# PixHawk_Fire_v1_5.net
KiCad netlist of a schematic drawn in EAGLE
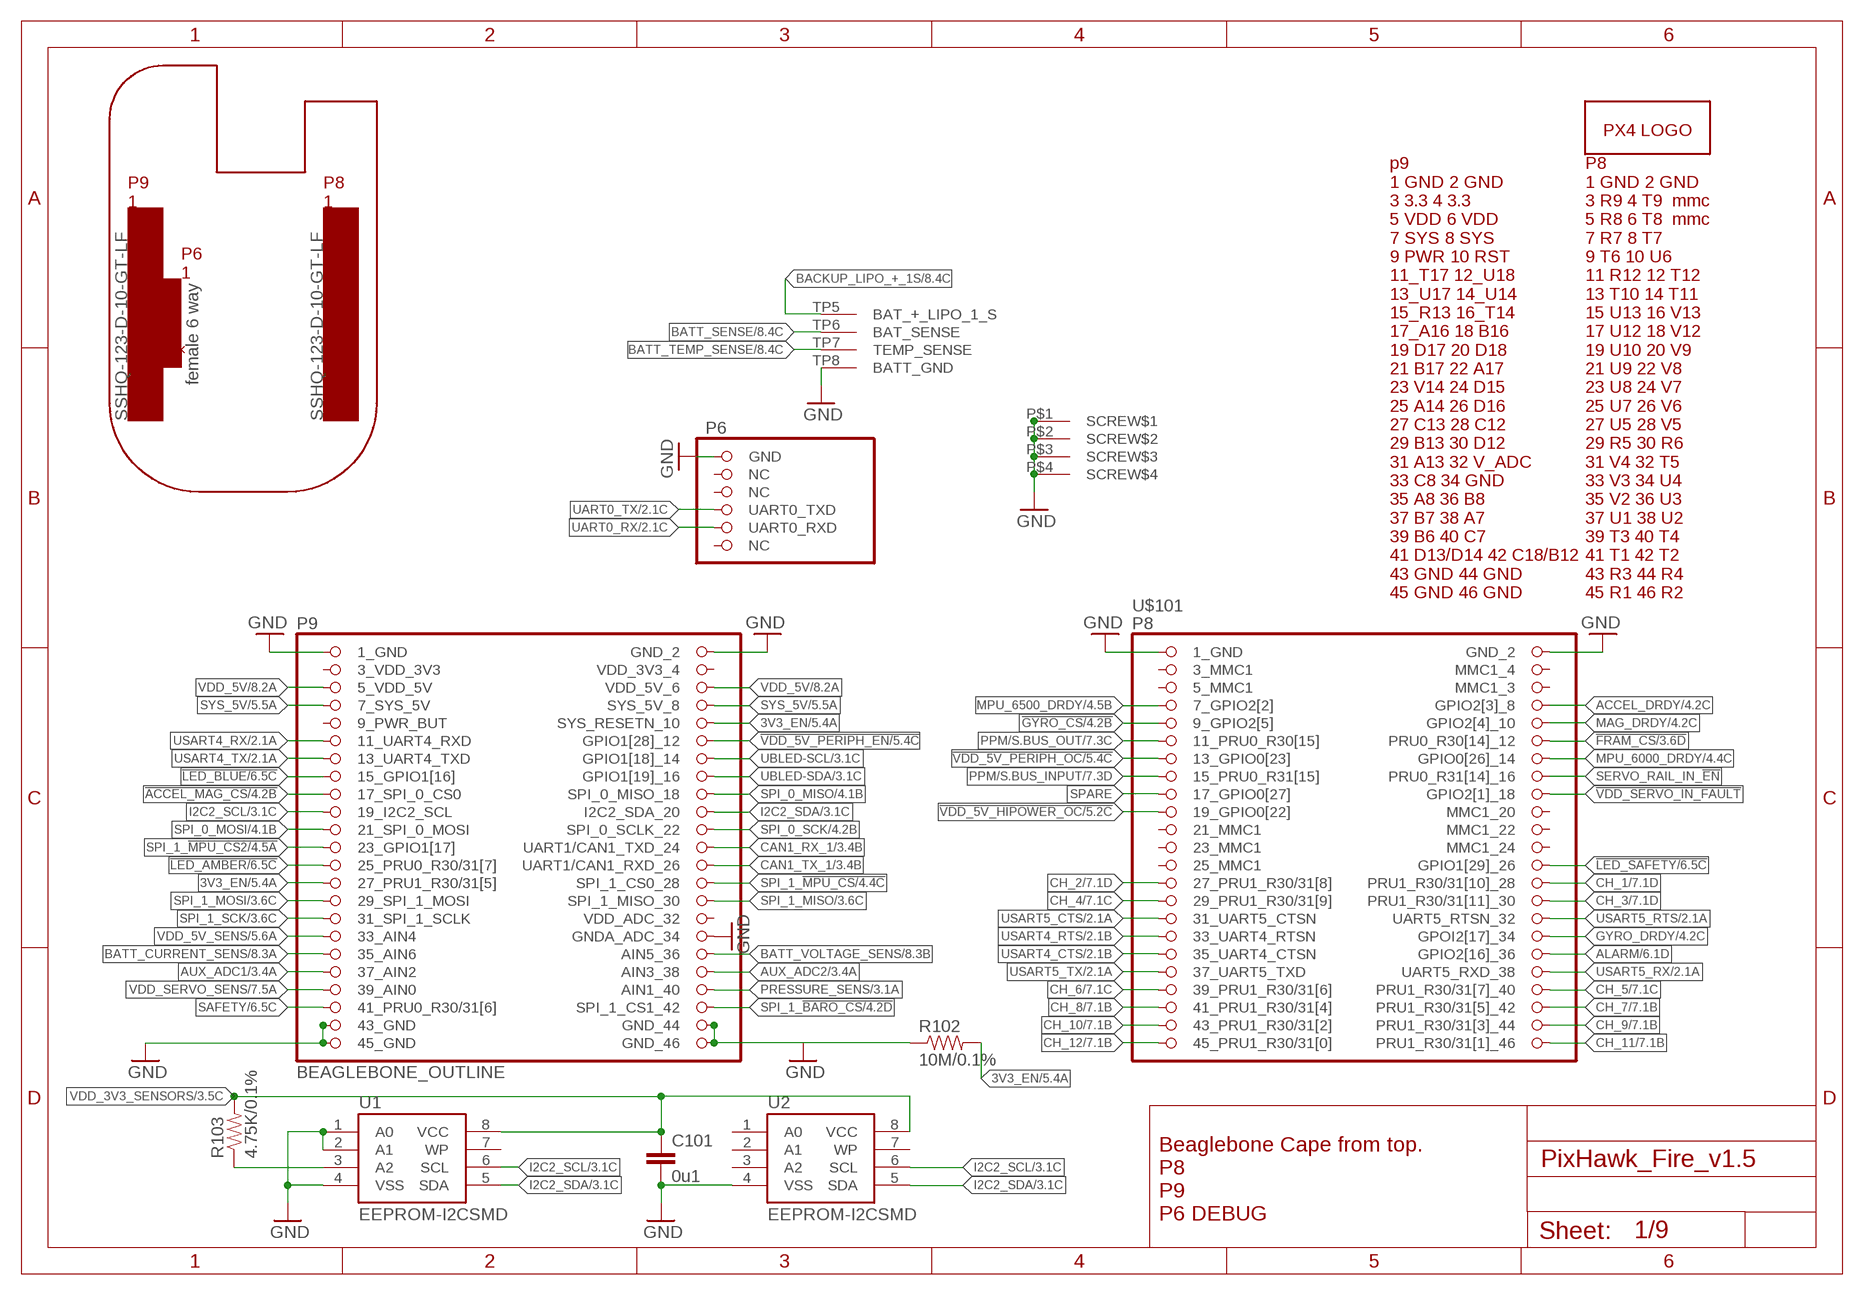
[diagram p0: schematic, sheet 1]
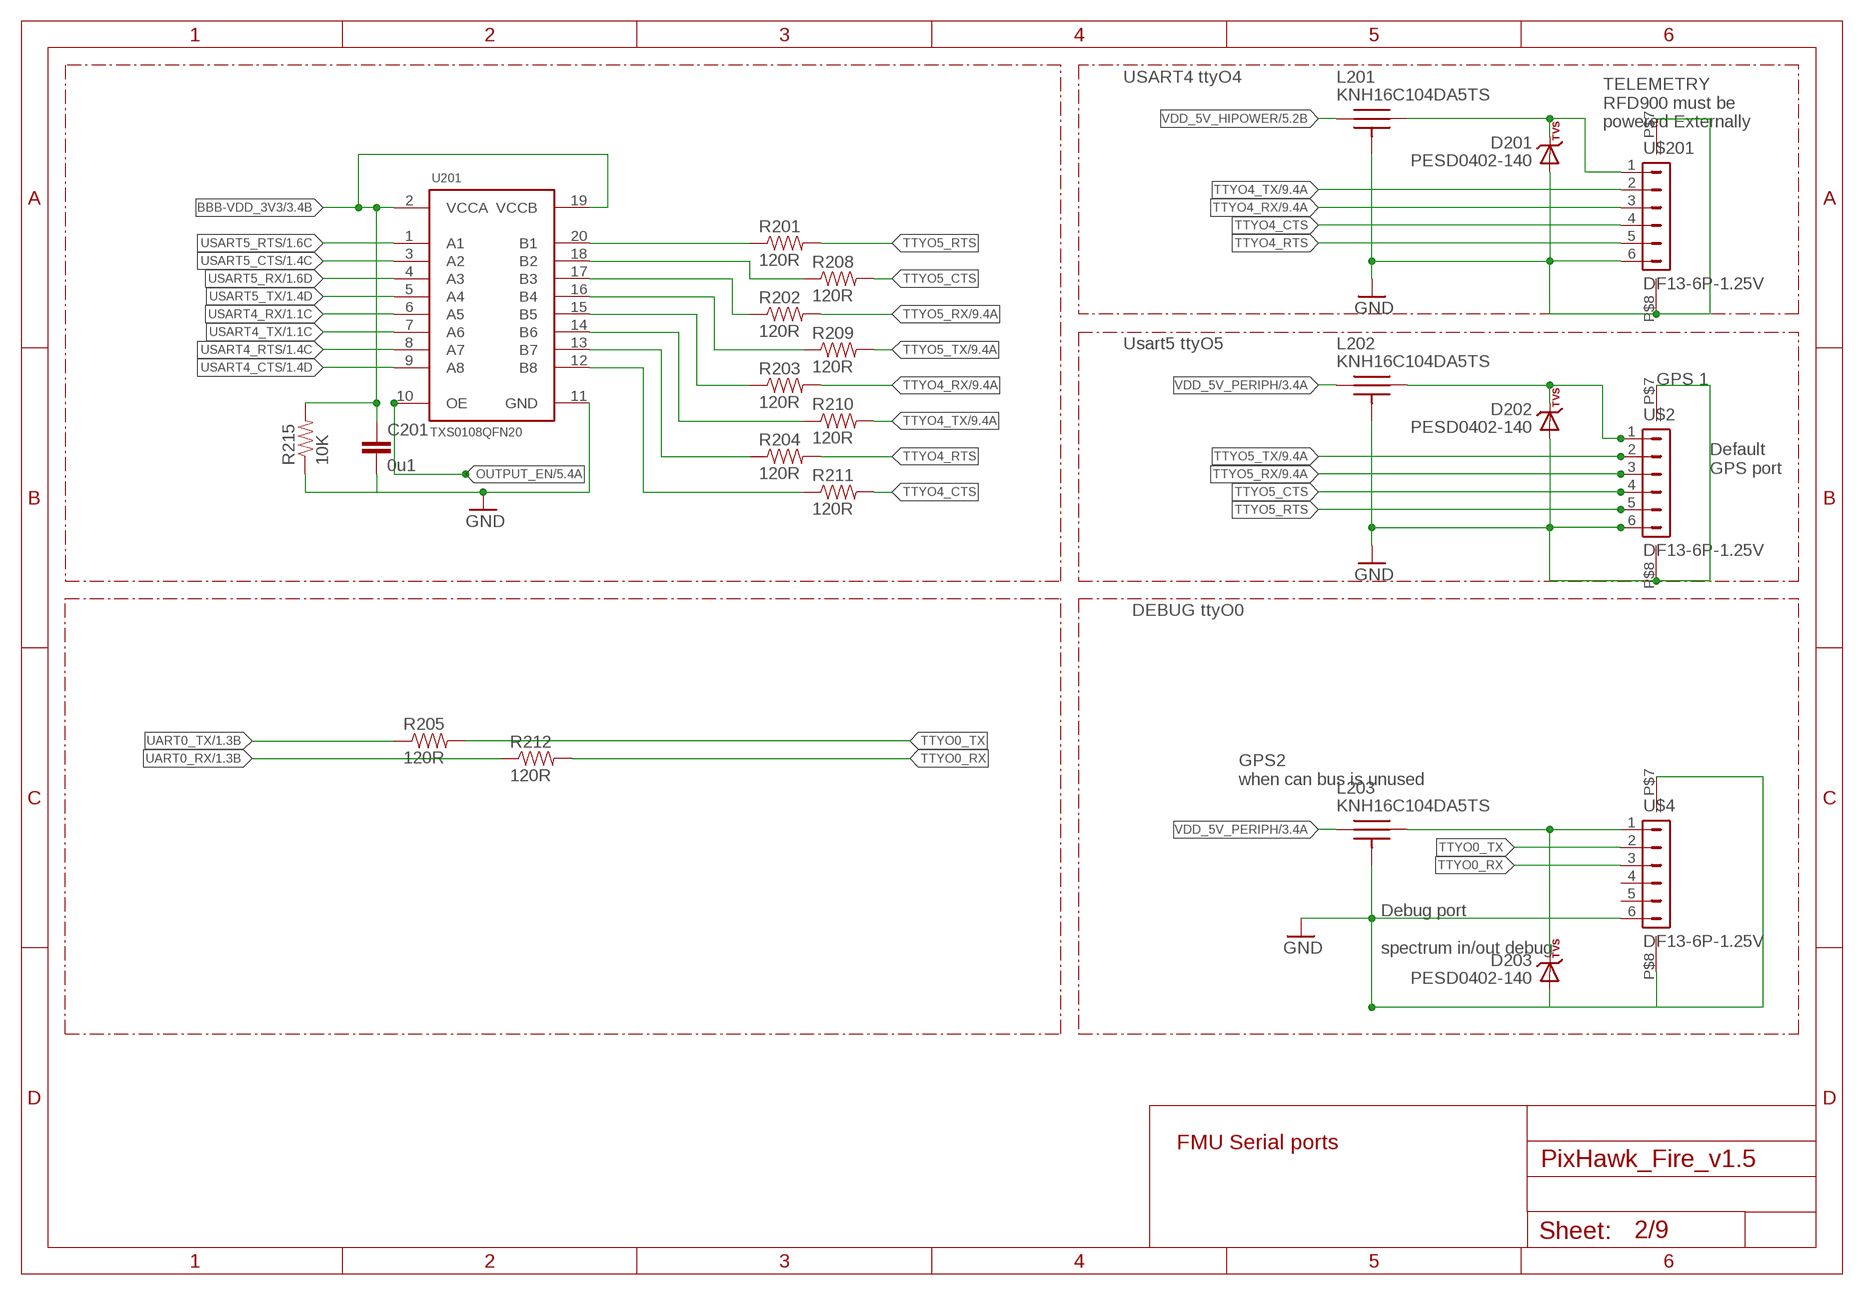
[diagram p1: schematic, sheet 2]
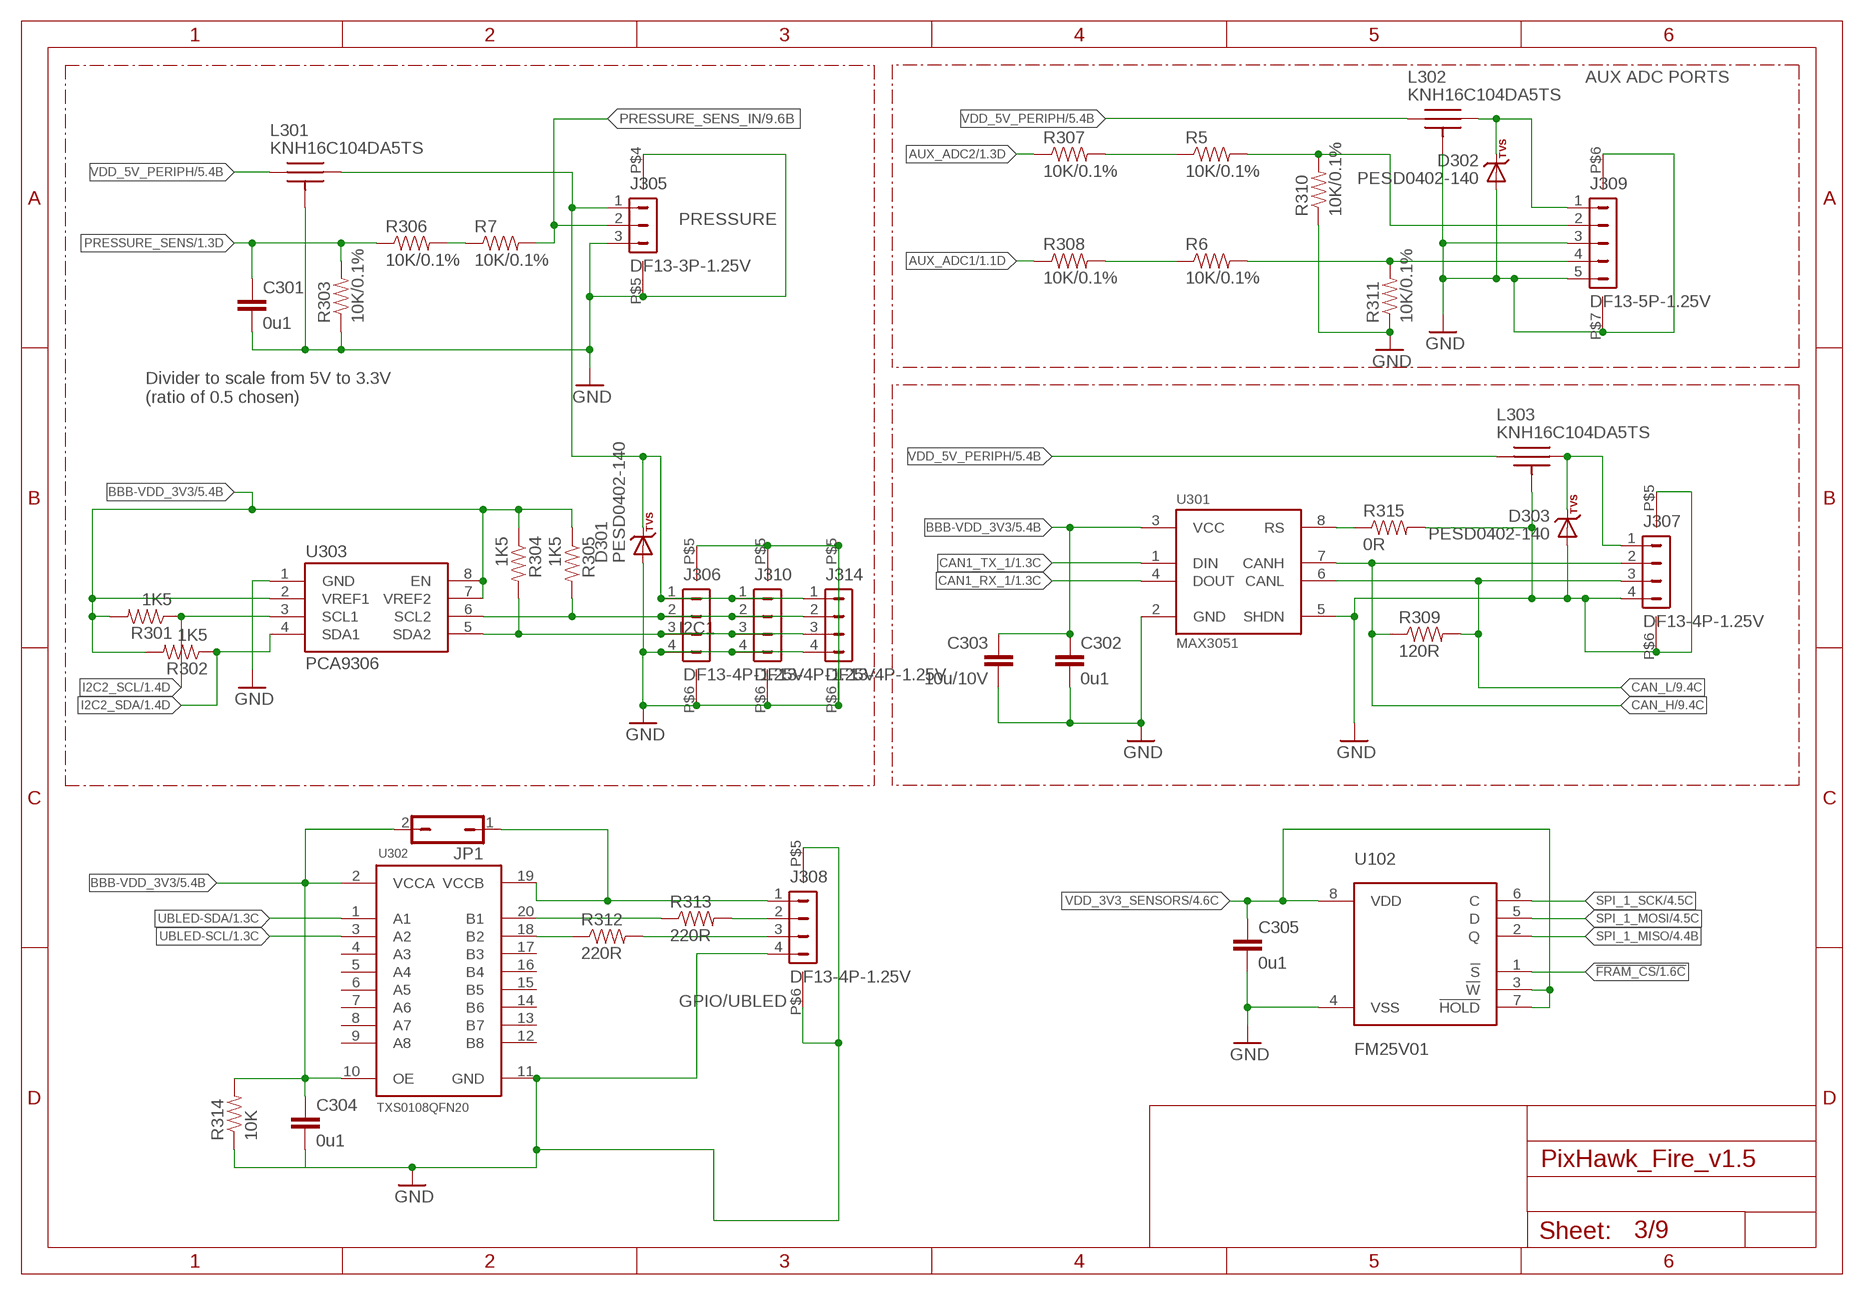
[diagram p2: schematic, sheet 3]
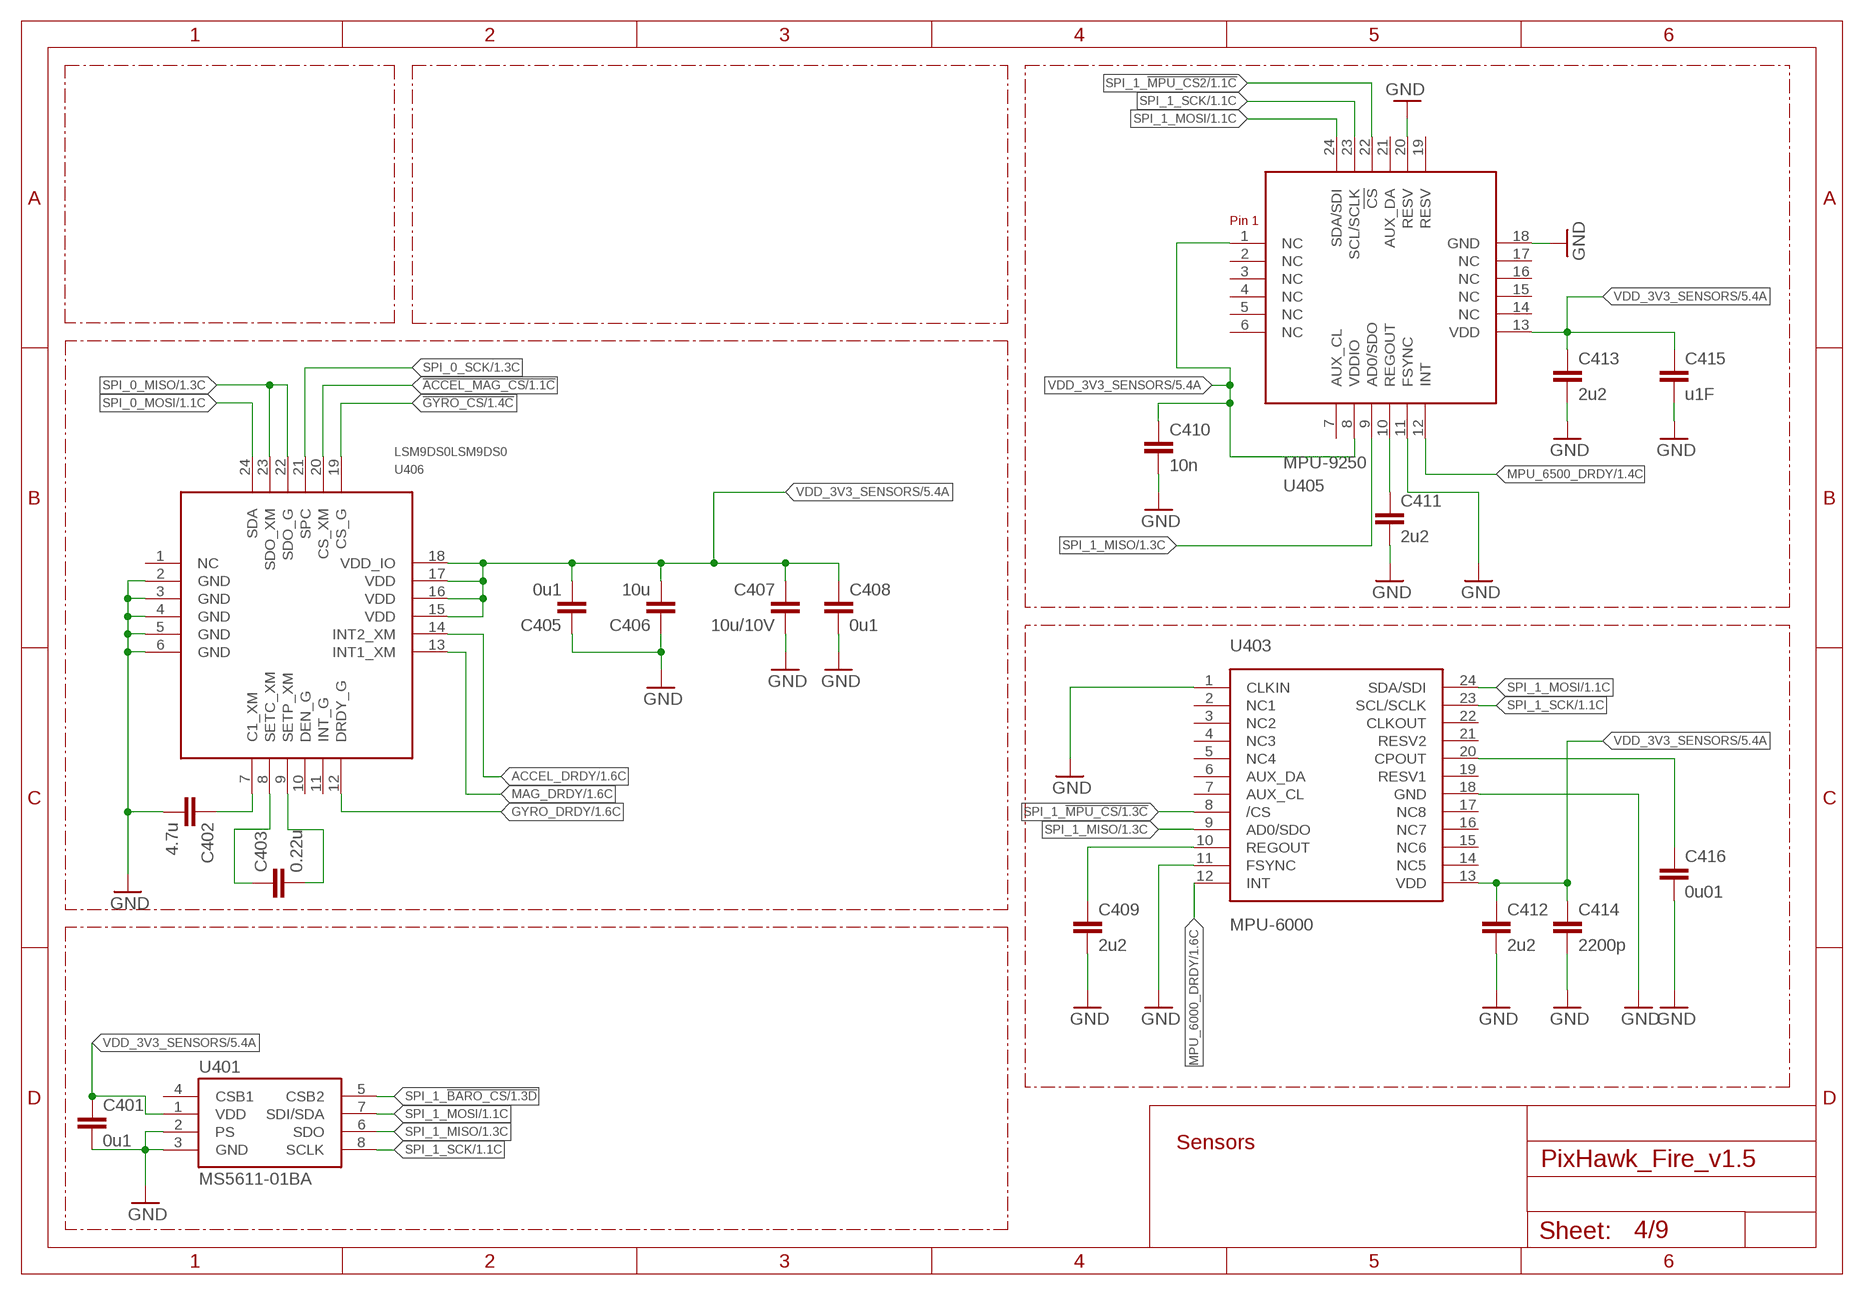
[diagram p3: schematic, sheet 4]
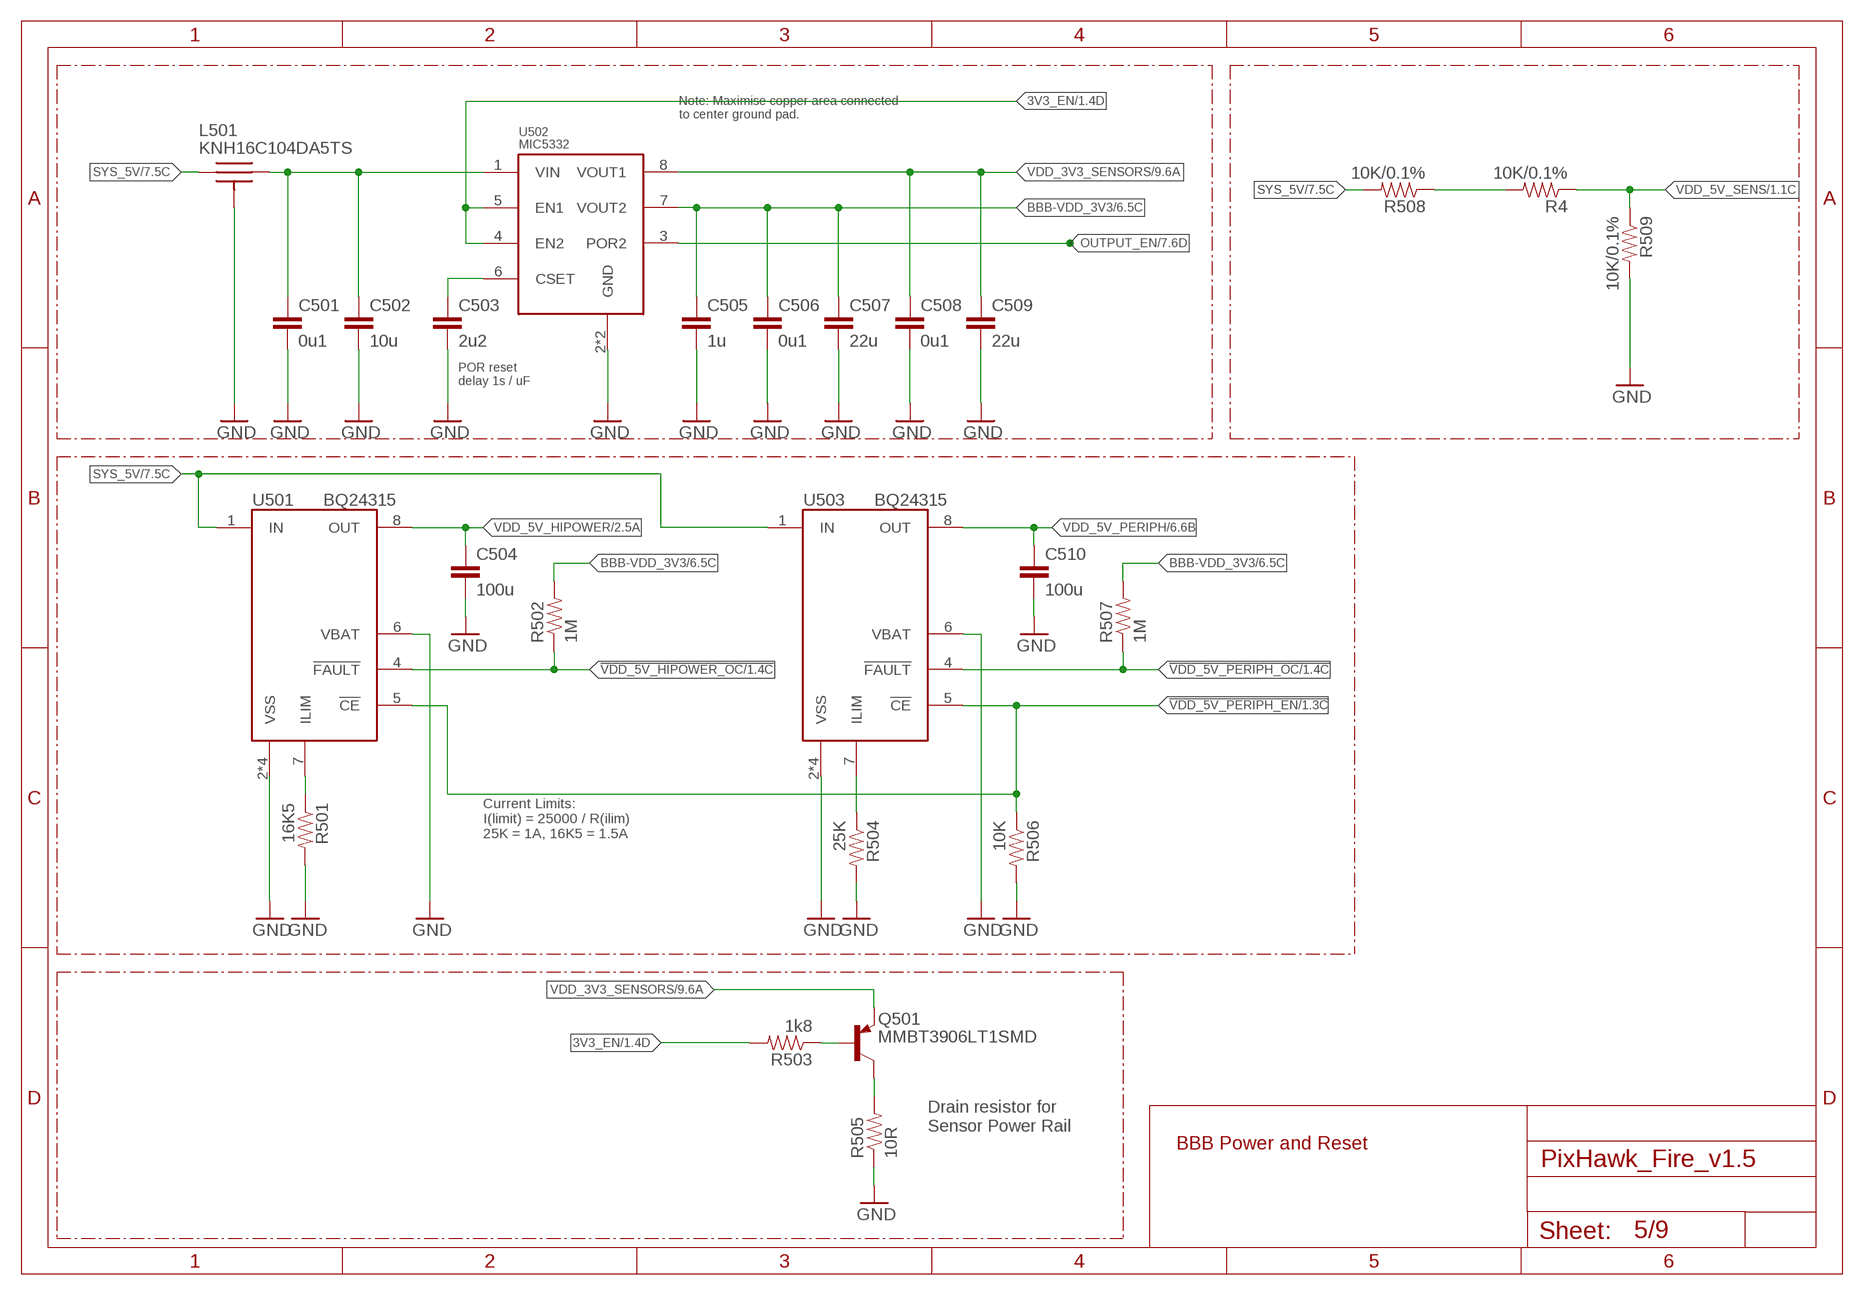
[diagram p4: schematic, sheet 5]
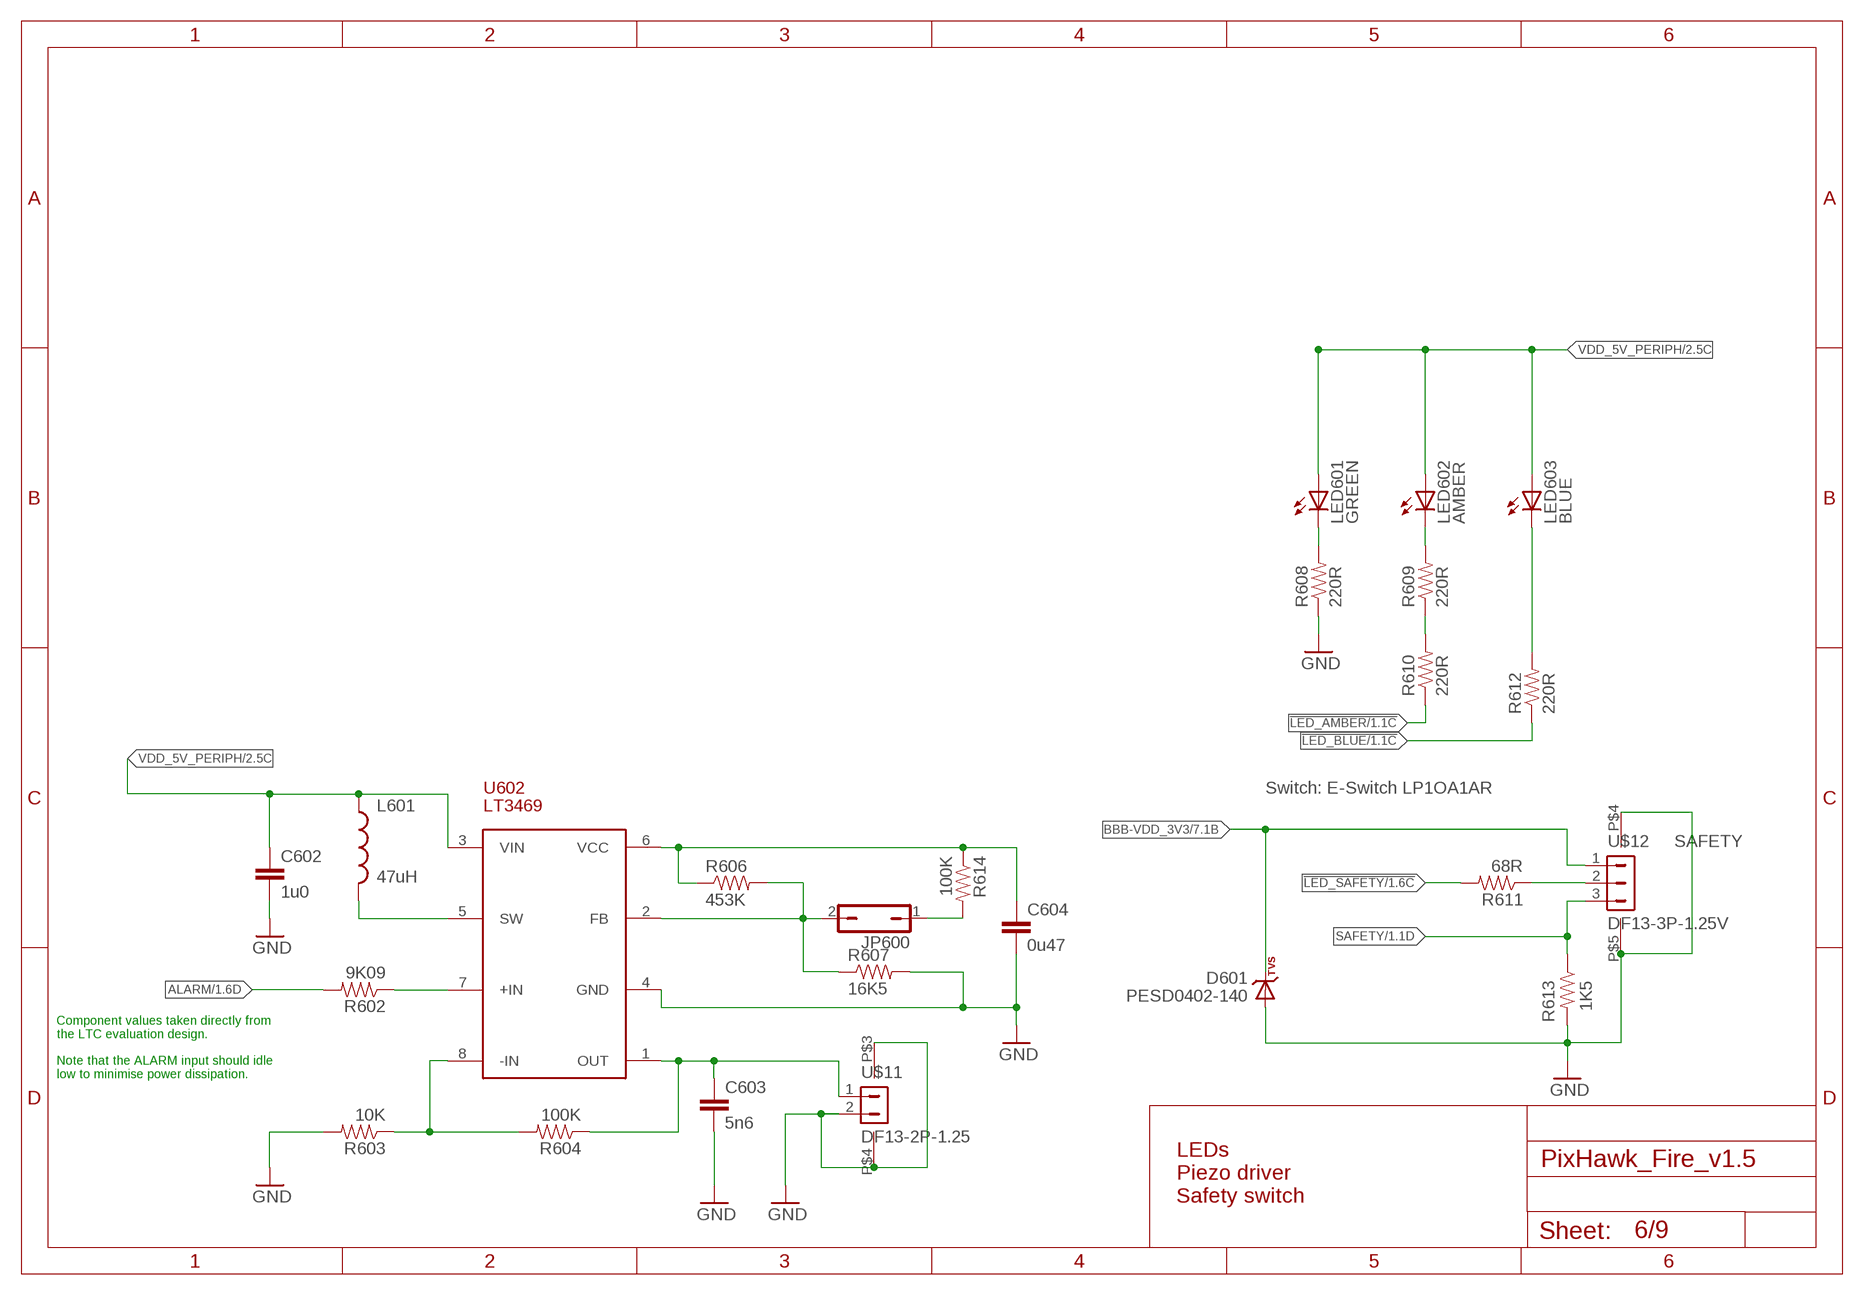
[diagram p5: schematic, sheet 6]
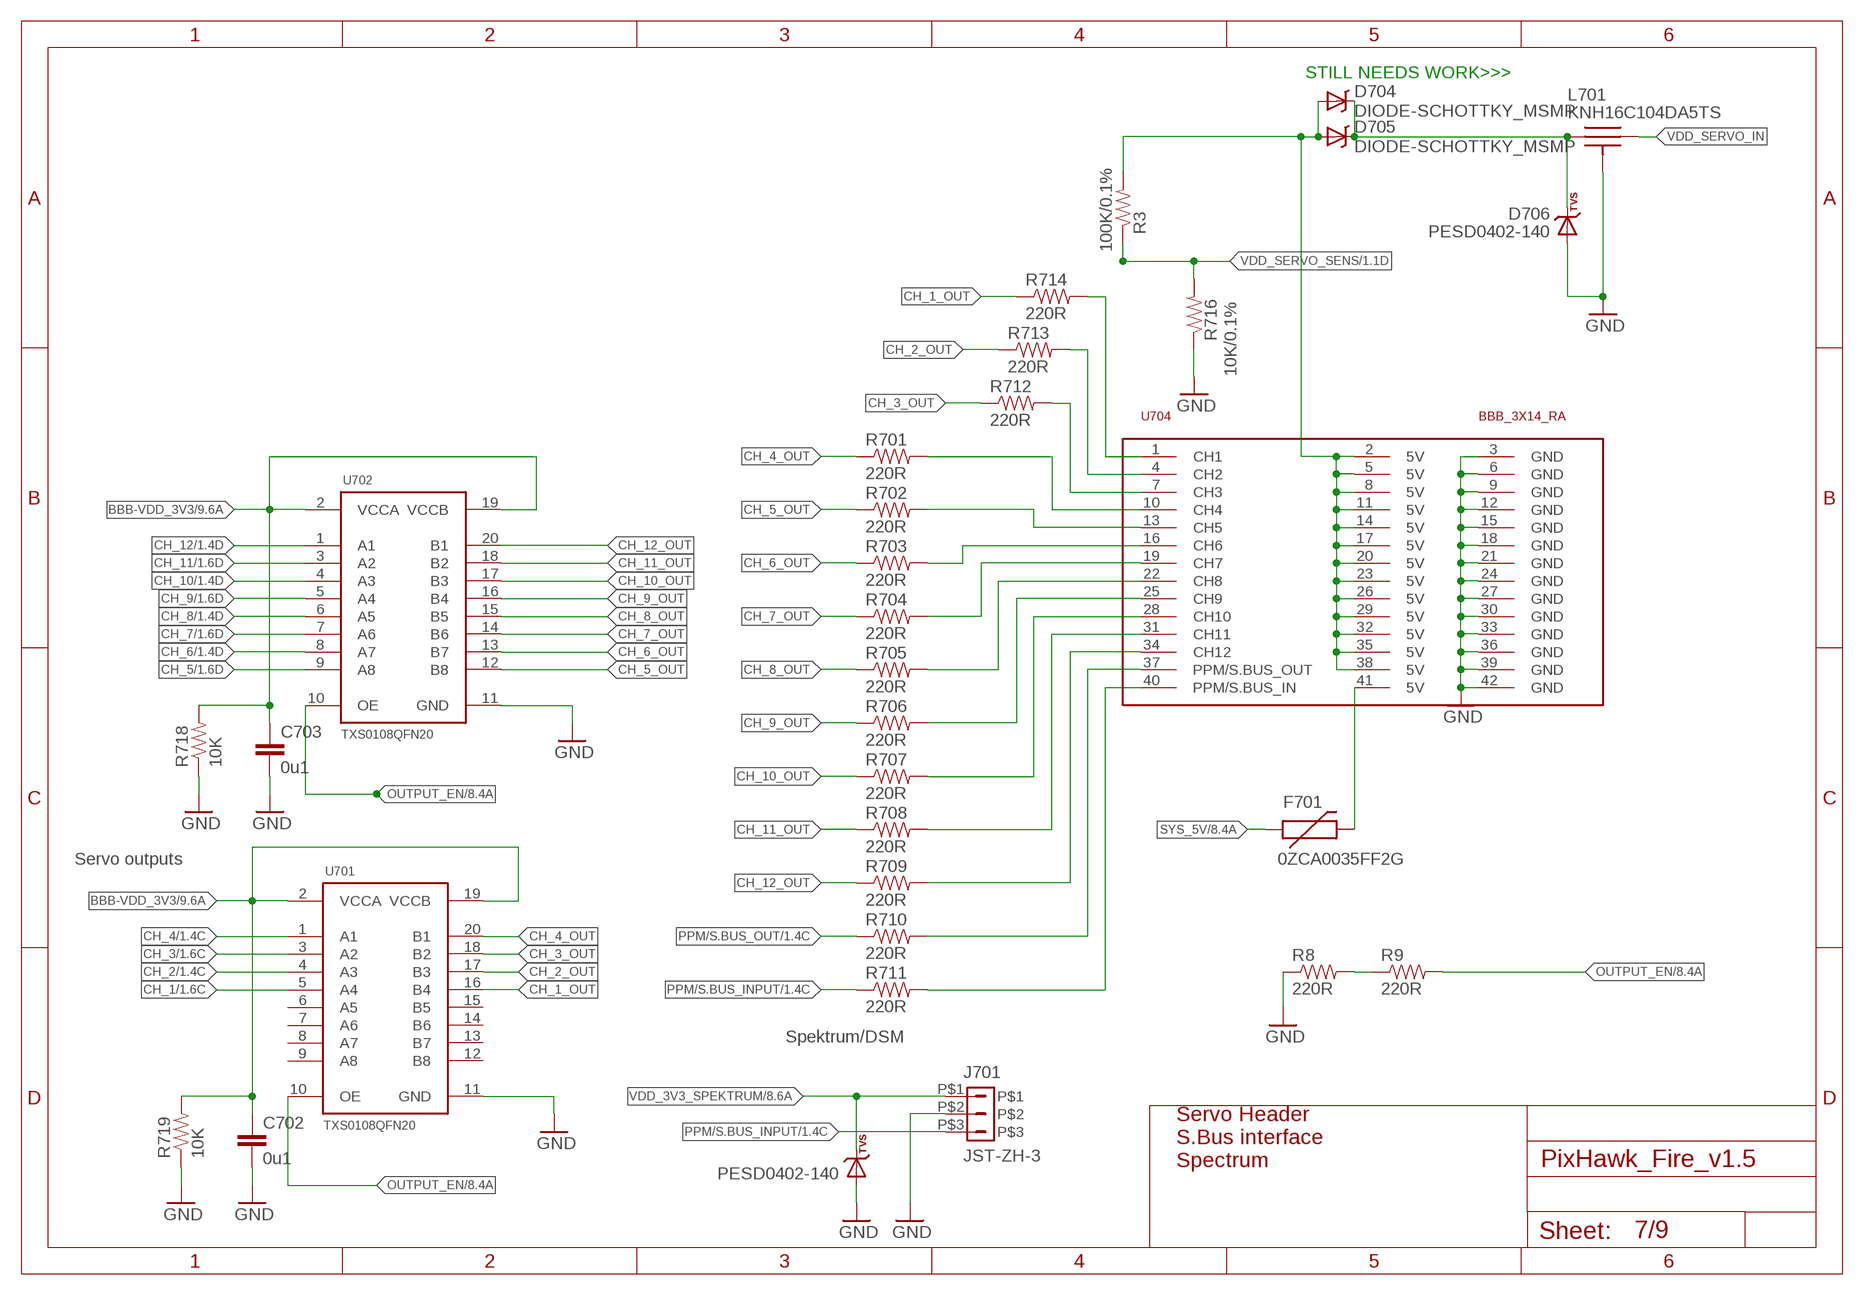
[diagram p6: schematic, sheet 7]
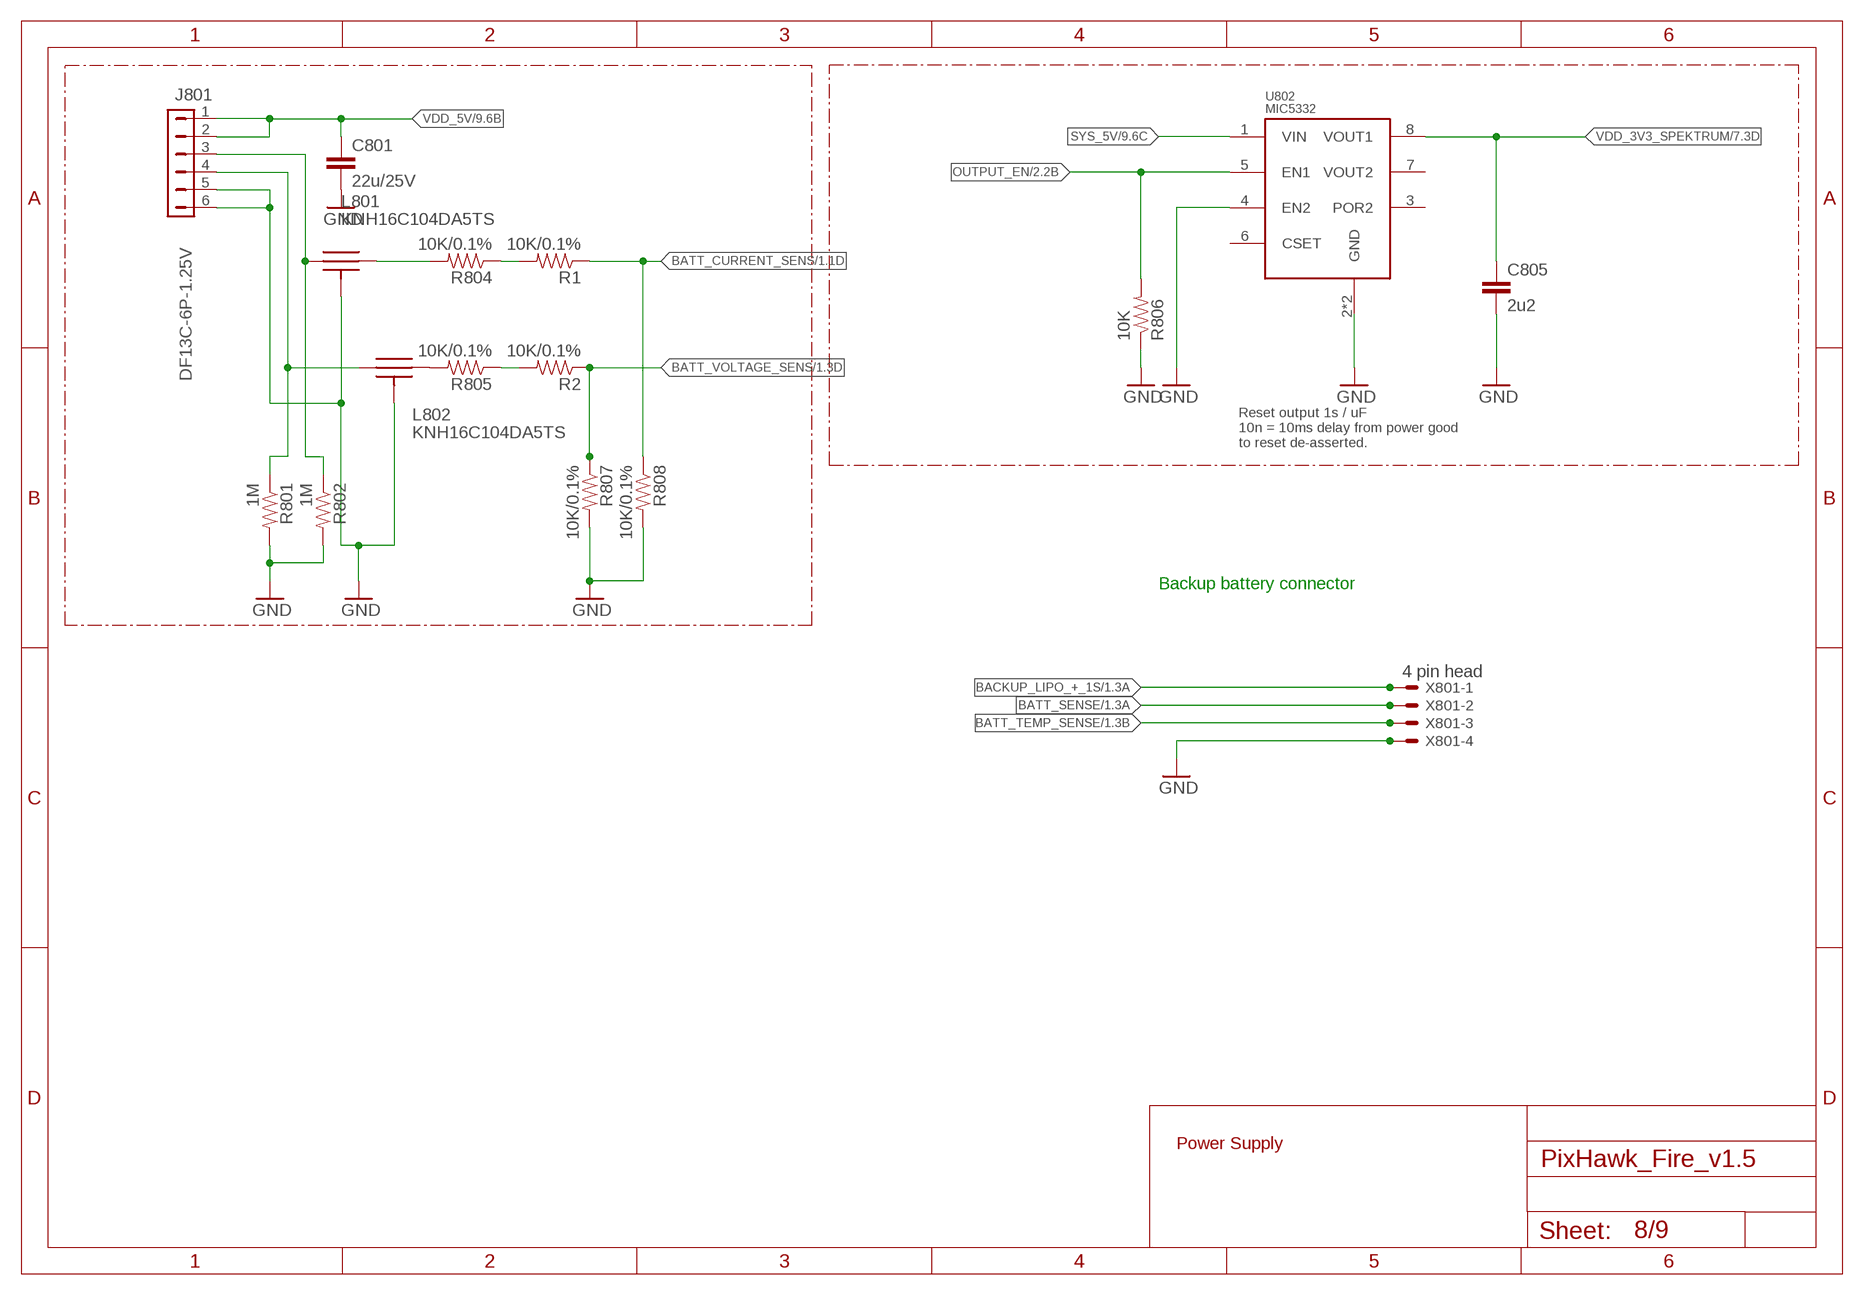
[diagram p7: schematic, sheet 8]
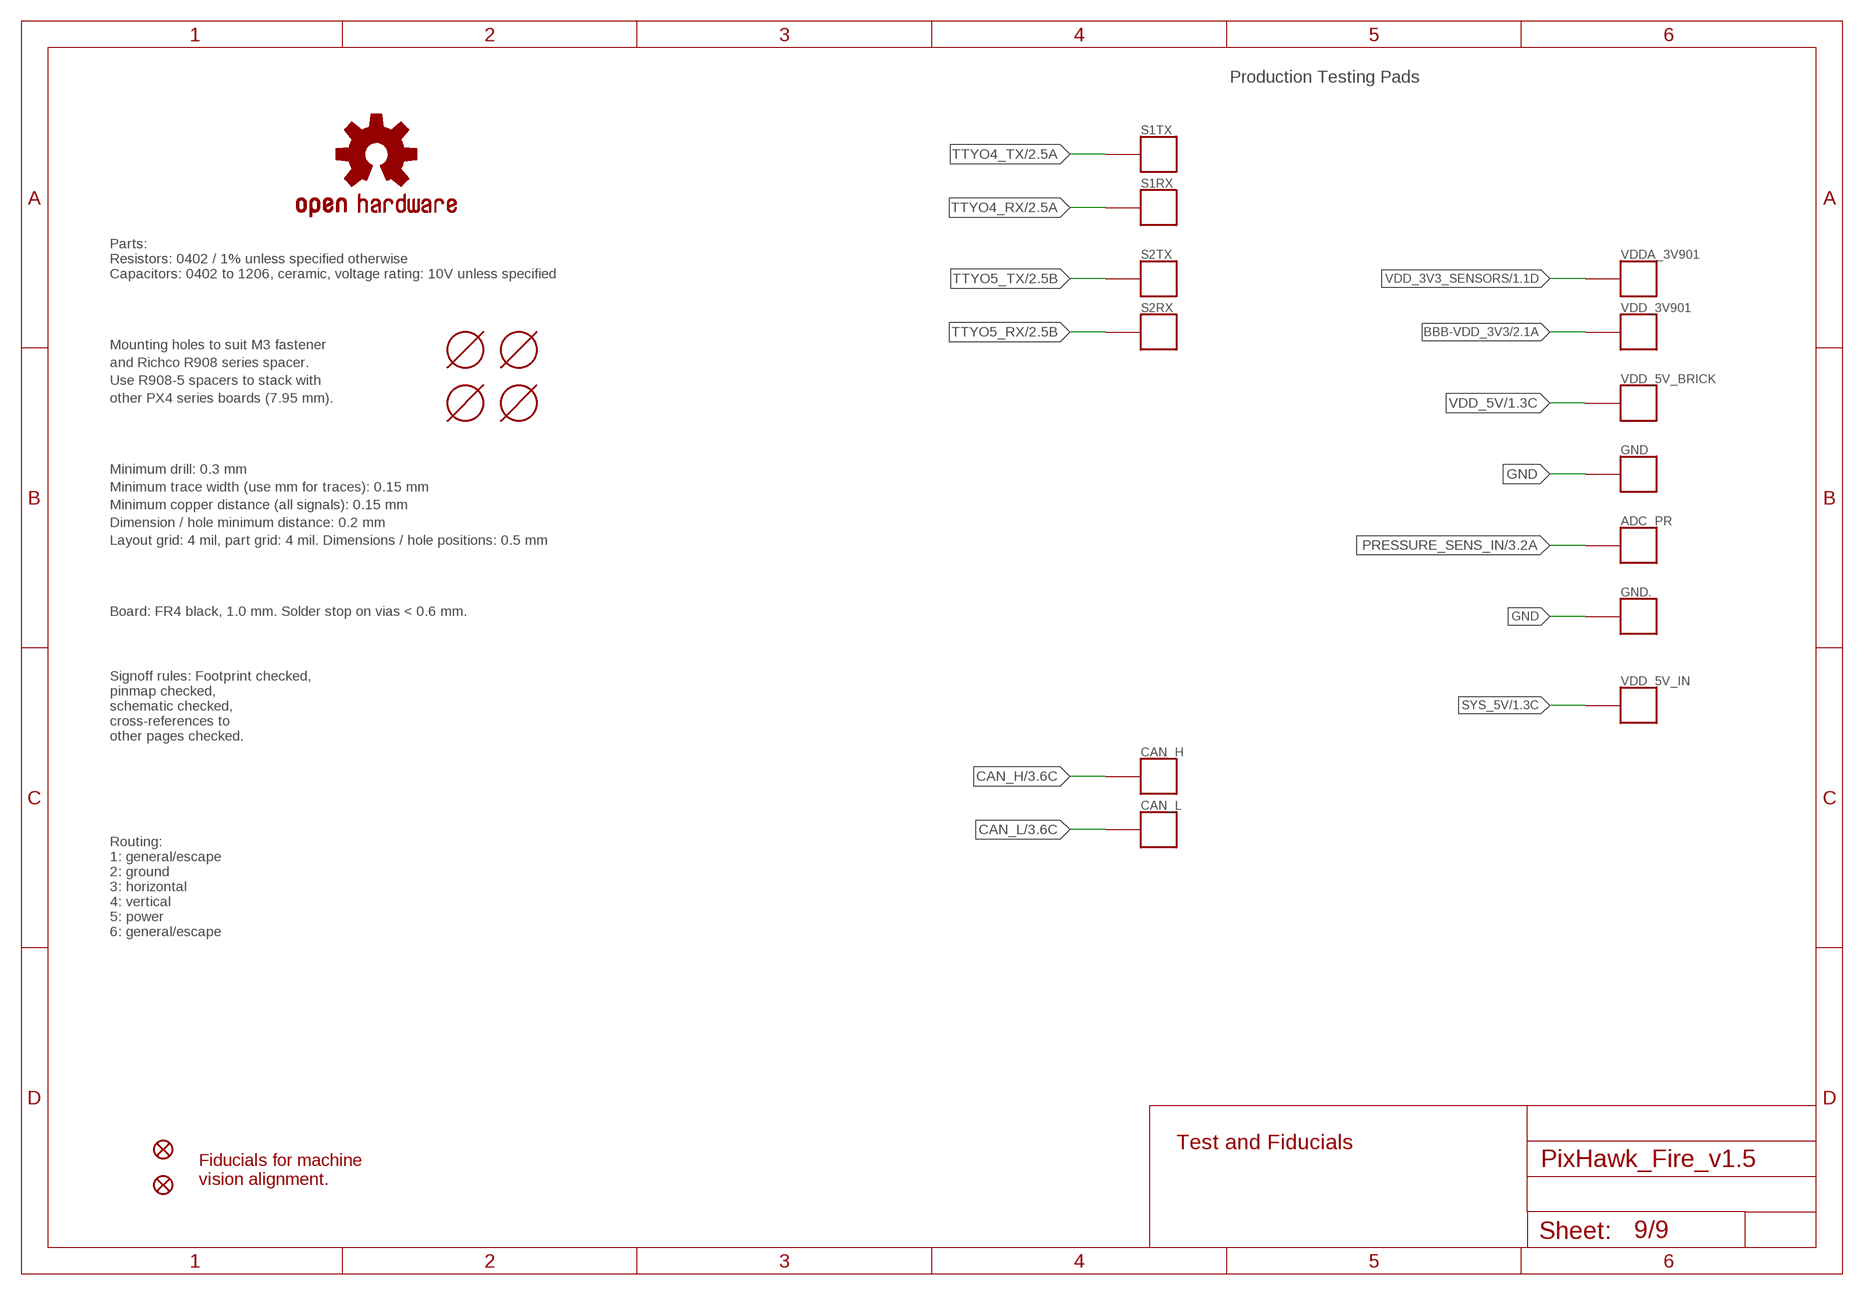
[diagram p8: schematic, sheet 9]

(export (version "E")
  (design (tool "Eeschema 10.0.6"))
  (components
    (comp (ref "ADC_PR")
      (value "PAD.04")
      (footprint "eagle-import:PAD.04X.04")
      (libsource (lib "eagle-import") (part "PAD.04"))
    )
    (comp (ref "CAN_H")
      (value "PAD.04")
      (footprint "eagle-import:PAD.04X.04")
      (libsource (lib "eagle-import") (part "PAD.04"))
    )
    (comp (ref "CAN_L")
      (value "PAD.04")
      (footprint "eagle-import:PAD.04X.04")
      (libsource (lib "eagle-import") (part "PAD.04"))
    )
    (comp (ref "GND")
      (value "PAD.04")
      (footprint "eagle-import:PAD.04X.04")
      (libsource (lib "eagle-import") (part "PAD.04"))
    )
    (comp (ref "GND.")
      (value "PAD.04")
      (footprint "eagle-import:PAD.04X.04")
      (libsource (lib "eagle-import") (part "PAD.04"))
    )
    (comp (ref "JP901")
      (value "FIDUCIAL1.5X3")
      (footprint "eagle-import:FIDUCIAL-1.5X3")
      (libsource (lib "eagle-import") (part "FIDUCIAL1.5X3"))
    )
    (comp (ref "JP902")
      (value "FIDUCIAL1.5X3")
      (footprint "eagle-import:FIDUCIAL-1.5X3")
      (libsource (lib "eagle-import") (part "FIDUCIAL1.5X3"))
    )
    (comp (ref "M3_MOUNT901")
      (value "MOUNT-HOLE3.1MM")
      (footprint "eagle-import:MOUNT-HOLE3.1")
      (libsource (lib "eagle-import") (part "MOUNT-HOLE3.1MM"))
    )
    (comp (ref "M3_MOUNT902")
      (value "MOUNT-HOLE3.1MM")
      (footprint "eagle-import:MOUNT-HOLE3.1")
      (libsource (lib "eagle-import") (part "MOUNT-HOLE3.1MM"))
    )
    (comp (ref "M3_MOUNT903")
      (value "MOUNT-HOLE3.1MM")
      (footprint "eagle-import:MOUNT-HOLE3.1")
      (libsource (lib "eagle-import") (part "MOUNT-HOLE3.1MM"))
    )
    (comp (ref "M3_MOUNT904")
      (value "MOUNT-HOLE3.1MM")
      (footprint "eagle-import:MOUNT-HOLE3.1")
      (libsource (lib "eagle-import") (part "MOUNT-HOLE3.1MM"))
    )
    (comp (ref "OSHW_LOGO")
      (value "OSHW-LOGOS")
      (footprint "eagle-import:OSHW-LOGO-S")
      (libsource (lib "eagle-import") (part "OSHW-LOGOS"))
    )
    (comp (ref "S1RX")
      (value "PAD.04")
      (footprint "eagle-import:PAD.04X.04")
      (libsource (lib "eagle-import") (part "PAD.04"))
    )
    (comp (ref "S1TX")
      (value "PAD.04")
      (footprint "eagle-import:PAD.04X.04")
      (libsource (lib "eagle-import") (part "PAD.04"))
    )
    (comp (ref "S2RX")
      (value "PAD.04")
      (footprint "eagle-import:PAD.04X.04")
      (libsource (lib "eagle-import") (part "PAD.04"))
    )
    (comp (ref "S2TX")
      (value "PAD.04")
      (footprint "eagle-import:PAD.04X.04")
      (libsource (lib "eagle-import") (part "PAD.04"))
    )
    (comp (ref "VDDA_3V901")
      (value "PAD.04")
      (footprint "eagle-import:PAD.04X.04")
      (libsource (lib "eagle-import") (part "PAD.04"))
    )
    (comp (ref "VDD_3V901")
      (value "PAD.04")
      (footprint "eagle-import:PAD.04X.04")
      (libsource (lib "eagle-import") (part "PAD.04"))
    )
    (comp (ref "VDD_5V_BRICK")
      (value "PAD.04")
      (footprint "eagle-import:PAD.04X.04")
      (libsource (lib "eagle-import") (part "PAD.04"))
    )
    (comp (ref "VDD_5V_IN")
      (value "PAD.04")
      (footprint "eagle-import:PAD.04X.04")
      (libsource (lib "eagle-import") (part "PAD.04"))
    )
    (comp (ref "C101")
      (value "0u1")
      (footprint "eagle-import:0402-CAP")
      (fields (field (name "PARTNO") "CC0402ZRY5V7BB104"))
      (libsource (lib "eagle-import") (part "CAP0402"))
    )
    (comp (ref "R102")
      (value "10M/0.1%")
      (footprint "eagle-import:0402-RES")
      (fields (field (name "PARTNO") "RC0402FR-0710ML"))
      (libsource (lib "eagle-import") (part "RESISTOR0402-RES"))
    )
    (comp (ref "R103")
      (value "4.75K/0.1%")
      (footprint "eagle-import:0402-RES")
      (fields (field (name "PARTNO") "RC0402FR-074K75L"))
      (libsource (lib "eagle-import") (part "RESISTOR0402-RES"))
    )
    (comp (ref "U$1")
      (value "PX4-LOGO")
      (footprint "eagle-import:PIXHAWK-FIRE-LOGO-30")
      (libsource (lib "eagle-import") (part "PX4-LOGO"))
    )
    (comp (ref "U$101")
      (value "BEAGLEBONE_OUTLINE")
      (footprint "eagle-import:BEAGLEBONE_SHIELD")
      (libsource (lib "eagle-import") (part "BEAGLEBONE_OUTLINE"))
    )
    (comp (ref "U1")
      (value "EEPROM-I2CSMD")
      (footprint "eagle-import:SO08")
      (fields (field (name "PARTNO") "AT24CS32-SSHM"))
      (libsource (lib "eagle-import") (part "EEPROM-I2CSMD"))
    )
    (comp (ref "U2")
      (value "EEPROM-I2CSMD")
      (footprint "eagle-import:SO08")
      (fields (field (name "PARTNO") "ATSHA204-SH-DA-TTR-ND"))
      (libsource (lib "eagle-import") (part "EEPROM-I2CSMD"))
    )
    (comp (ref "C501")
      (value "0u1")
      (footprint "eagle-import:0402-CAP")
      (fields (field (name "PARTNO") "CC0402ZRY5V7BB104"))
      (libsource (lib "eagle-import") (part "CAP0402"))
    )
    (comp (ref "C502")
      (value "10u")
      (footprint "eagle-import:0805-CAP")
      (fields (field (name "PARTNO") "C1608X7S0J106M080AC"))
      (libsource (lib "eagle-import") (part "CAP0805"))
    )
    (comp (ref "C503")
      (value "2u2")
      (footprint "eagle-import:0603-CAP")
      (fields (field (name "PARTNO") "C1608X6S1C225K080AC"))
      (libsource (lib "eagle-import") (part "CAP0603"))
    )
    (comp (ref "C504")
      (value "100u")
      (footprint "eagle-import:1206-CAP")
      (fields (field (name "PARTNO") "C3216X5R1A107M160AC"))
      (libsource (lib "eagle-import") (part "CAP1206"))
    )
    (comp (ref "C505")
      (value "1u")
      (footprint "eagle-import:0603-CAP")
      (fields (field (name "PARTNO") "CC0603ZRY5V7BB105"))
      (libsource (lib "eagle-import") (part "CAP0603"))
    )
    (comp (ref "C506")
      (value "0u1")
      (footprint "eagle-import:0402-CAP")
      (fields (field (name "PARTNO") "CC0402ZRY5V7BB104"))
      (libsource (lib "eagle-import") (part "CAP0402"))
    )
    (comp (ref "C507")
      (value "22u")
      (footprint "eagle-import:0805-CAP")
      (fields (field (name "PARTNO") "CC0805MKX5R5BB226"))
      (libsource (lib "eagle-import") (part "CAP0805"))
    )
    (comp (ref "C508")
      (value "0u1")
      (footprint "eagle-import:0402-CAP")
      (fields (field (name "PARTNO") "CC0402ZRY5V7BB104"))
      (libsource (lib "eagle-import") (part "CAP0402"))
    )
    (comp (ref "C509")
      (value "22u")
      (footprint "eagle-import:0805-CAP")
      (fields (field (name "PARTNO") "CC0805MKX5R5BB226"))
      (libsource (lib "eagle-import") (part "CAP0805"))
    )
    (comp (ref "C510")
      (value "100u")
      (footprint "eagle-import:1206-CAP")
      (fields (field (name "PARTNO") "C3216X5R1A107M160AC"))
      (libsource (lib "eagle-import") (part "CAP1206"))
    )
    (comp (ref "L501")
      (value "KNH16C104DA5TS")
      (footprint "eagle-import:KYOCERA-KNH16-DA")
      (libsource (lib "eagle-import") (part "KNH16C104DA5TS"))
    )
    (comp (ref "Q501")
      (value "MMBT3906LT1SMD")
      (footprint "eagle-import:SOT23-BEC")
      (fields (field (name "PARTNO") "MMBT3906LT1G"))
      (libsource (lib "eagle-import") (part "MMBT3906SMDLT1"))
    )
    (comp (ref "R4")
      (value "10K/0.1%")
      (footprint "eagle-import:0402-RES")
      (fields (field (name "PARTNO") "ERA-2AEB103X"))
      (libsource (lib "eagle-import") (part "RESISTOR0402-RES"))
    )
    (comp (ref "R501")
      (value "16K5")
      (footprint "eagle-import:0402-RES")
      (fields (field (name "PARTNO") "RMCF0402FT16K5"))
      (libsource (lib "eagle-import") (part "RESISTOR0402-RES"))
    )
    (comp (ref "R502")
      (value "1M")
      (footprint "eagle-import:0402-RES")
      (fields (field (name "PARTNO") "MCR01MRTF1004"))
      (libsource (lib "eagle-import") (part "RESISTOR0402-RES"))
    )
    (comp (ref "R503")
      (value "1k8")
      (footprint "eagle-import:0402-RES")
      (fields (field (name "PARTNO") "RC0402FR-071K8L"))
      (libsource (lib "eagle-import") (part "RESISTOR0402-RES"))
    )
    (comp (ref "R504")
      (value "25K")
      (footprint "eagle-import:0402-RES")
      (fields (field (name "PARTNO") "RMCF0402FT25K5"))
      (libsource (lib "eagle-import") (part "RESISTOR0402-RES"))
    )
    (comp (ref "R505")
      (value "10R")
      (footprint "eagle-import:0603-RES")
      (fields (field (name "PARTNO") "RC0402FR-0710RL"))
      (libsource (lib "eagle-import") (part "RESISTOR0603-RES"))
    )
    (comp (ref "R506")
      (value "10K")
      (footprint "eagle-import:0402-RES")
      (fields (field (name "PARTNO") "ERA-2AEB103X"))
      (libsource (lib "eagle-import") (part "RESISTOR0402-RES"))
    )
    (comp (ref "R507")
      (value "1M")
      (footprint "eagle-import:0402-RES")
      (fields (field (name "PARTNO") "MCR01MRTF1004"))
      (libsource (lib "eagle-import") (part "RESISTOR0402-RES"))
    )
    (comp (ref "R508")
      (value "10K/0.1%")
      (footprint "eagle-import:0402-RES")
      (fields (field (name "PARTNO") "ERA-2AEB103X"))
      (libsource (lib "eagle-import") (part "RESISTOR0402-RES"))
    )
    (comp (ref "R509")
      (value "10K/0.1%")
      (footprint "eagle-import:0402-RES")
      (fields (field (name "PARTNO") "ERA-2AEB103X"))
      (libsource (lib "eagle-import") (part "RESISTOR0402-RES"))
    )
    (comp (ref "U501")
      (value "BQ24315")
      (footprint "eagle-import:QFN8-DSG")
      (fields (field (name "PARTNO") "BQ24315DSGR"))
      (libsource (lib "eagle-import") (part "BQ24315"))
    )
    (comp (ref "U502")
      (value "MIC5332")
      (footprint "eagle-import:MLF-8-EPAD")
      (fields (field (name "PARTNO") "MIC5332-SSYMT"))
      (libsource (lib "eagle-import") (part "MIC5332"))
    )
    (comp (ref "U503")
      (value "BQ24315")
      (footprint "eagle-import:QFN8-DSG")
      (fields (field (name "PARTNO") "BQ24315DSGR"))
      (libsource (lib "eagle-import") (part "BQ24315"))
    )
    (comp (ref "C801")
      (value "22u/25V")
      (footprint "eagle-import:0805-CAP")
      (fields (field (name "PARTNO") "CL21A226MAQNNNE"))
      (libsource (lib "eagle-import") (part "CAP0805"))
    )
    (comp (ref "C805")
      (value "2u2")
      (footprint "eagle-import:0402-CAP")
      (fields (field (name "PARTNO") "CC0603ZRY5V6BB225"))
      (libsource (lib "eagle-import") (part "CAP0402"))
    )
    (comp (ref "J801")
      (value "DF13C-6P-1.25V")
      (footprint "eagle-import:DF13C-6P-1.25V")
      (fields (field (name "PARTNO") "DF13C-6P-1.25V(20)"))
      (libsource (lib "eagle-import") (part "DF13-6P-1.25V"))
    )
    (comp (ref "L801")
      (value "KNH16C104DA5TS")
      (footprint "eagle-import:KYOCERA-KNH16-DA")
      (libsource (lib "eagle-import") (part "KNH16C104DA5TS"))
    )
    (comp (ref "L802")
      (value "KNH16C104DA5TS")
      (footprint "eagle-import:KYOCERA-KNH16-DA")
      (libsource (lib "eagle-import") (part "KNH16C104DA5TS"))
    )
    (comp (ref "R1")
      (value "10K/0.1%")
      (footprint "eagle-import:0402-RES")
      (fields (field (name "PARTNO") "ERA-2AEB103X"))
      (libsource (lib "eagle-import") (part "RESISTOR0402-RES"))
    )
    (comp (ref "R2")
      (value "10K/0.1%")
      (footprint "eagle-import:0402-RES")
      (fields (field (name "PARTNO") "ERA-2AEB103X"))
      (libsource (lib "eagle-import") (part "RESISTOR0402-RES"))
    )
    (comp (ref "R801")
      (value "1M")
      (footprint "eagle-import:0402-RES")
      (fields (field (name "PARTNO") "RC0402FR-071ML"))
      (libsource (lib "eagle-import") (part "RESISTOR0402-RES"))
    )
    (comp (ref "R802")
      (value "1M")
      (footprint "eagle-import:0402-RES")
      (fields (field (name "PARTNO") "RC0402FR-071ML"))
      (libsource (lib "eagle-import") (part "RESISTOR0402-RES"))
    )
    (comp (ref "R804")
      (value "10K/0.1%")
      (footprint "eagle-import:0402-RES")
      (fields (field (name "PARTNO") "ERA-2AEB103X"))
      (libsource (lib "eagle-import") (part "RESISTOR0402-RES"))
    )
    (comp (ref "R805")
      (value "10K/0.1%")
      (footprint "eagle-import:0402-RES")
      (fields (field (name "PARTNO") "ERA-2AEB103X"))
      (libsource (lib "eagle-import") (part "RESISTOR0402-RES"))
    )
    (comp (ref "R806")
      (value "10K")
      (footprint "eagle-import:0402-RES")
      (fields (field (name "PARTNO") "ERA-2AEB103X"))
      (libsource (lib "eagle-import") (part "RESISTOR0402-RES"))
    )
    (comp (ref "R807")
      (value "10K/0.1%")
      (footprint "eagle-import:0402-RES")
      (fields (field (name "PARTNO") "ERA-2AEB103X"))
      (libsource (lib "eagle-import") (part "RESISTOR0402-RES"))
    )
    (comp (ref "R808")
      (value "10K/0.1%")
      (footprint "eagle-import:0402-RES")
      (fields (field (name "PARTNO") "ERA-2AEB103X"))
      (libsource (lib "eagle-import") (part "RESISTOR0402-RES"))
    )
    (comp (ref "U802")
      (value "MIC5332")
      (footprint "eagle-import:MLF-8-EPAD")
      (fields (field (name "PARTNO") "MIC5332-SSYMT"))
      (libsource (lib "eagle-import") (part "MIC5332"))
    )
    (comp (ref "X801")
      (value "4 pin head")
      (footprint "eagle-import:53047-04")
      (fields (field (name "PARTNO") "53047-04"))
      (libsource (lib "eagle-import") (part "53?-04047"))
    )
    (comp (ref "C301")
      (value "0u1")
      (footprint "eagle-import:0402-CAP")
      (fields (field (name "PARTNO") "CC0402ZRY5V7BB104"))
      (libsource (lib "eagle-import") (part "CAP0402"))
    )
    (comp (ref "C302")
      (value "0u1")
      (footprint "eagle-import:0402-CAP")
      (fields (field (name "PARTNO") "CC0402ZRY5V7BB104"))
      (libsource (lib "eagle-import") (part "CAP0402"))
    )
    (comp (ref "C303")
      (value "10u/10V")
      (footprint "eagle-import:0805-CAP")
      (fields (field (name "PARTNO") "CC0805ZKY5V6BB106"))
      (libsource (lib "eagle-import") (part "CAP0805"))
    )
    (comp (ref "C304")
      (value "0u1")
      (footprint "eagle-import:0402-CAP")
      (fields (field (name "PARTNO") "CC0402ZRY5V7BB104"))
      (libsource (lib "eagle-import") (part "CAP0402"))
    )
    (comp (ref "C305")
      (value "0u1")
      (footprint "eagle-import:0402-CAP")
      (fields (field (name "PARTNO") "CC0402ZRY5V7BB104"))
      (libsource (lib "eagle-import") (part "CAP0402"))
    )
    (comp (ref "D301")
      (value "PESD0402-140")
      (footprint "eagle-import:0402-TVS")
      (libsource (lib "eagle-import") (part "DIODE-TVS"))
    )
    (comp (ref "D302")
      (value "PESD0402-140")
      (footprint "eagle-import:0402-TVS")
      (libsource (lib "eagle-import") (part "DIODE-TVS"))
    )
    (comp (ref "D303")
      (value "PESD0402-140")
      (footprint "eagle-import:0402-TVS")
      (libsource (lib "eagle-import") (part "DIODE-TVS"))
    )
    (comp (ref "J305")
      (value "DF13-3P-1.25V")
      (footprint "eagle-import:DF13C-3P-1.25V")
      (fields (field (name "PARTNO") "DF13C-3P-1.25V(20)"))
      (libsource (lib "eagle-import") (part "DF13-3P-1.25V"))
    )
    (comp (ref "J306")
      (value "DF13-4P-1.25V")
      (footprint "eagle-import:DF13C-4P-1.25V")
      (fields (field (name "PARTNO") "DF13C-4P-1.25V(20)"))
      (libsource (lib "eagle-import") (part "DF13-4P-1.25V"))
    )
    (comp (ref "J307")
      (value "DF13-4P-1.25V")
      (footprint "eagle-import:DF13C-4P-1.25V")
      (fields (field (name "PARTNO") "DF13C-4P-1.25V(20)"))
      (libsource (lib "eagle-import") (part "DF13-4P-1.25V"))
    )
    (comp (ref "J308")
      (value "DF13-4P-1.25V")
      (footprint "eagle-import:DF13C-4P-1.25V")
      (fields (field (name "PARTNO") "DF13C-4P-1.25V(20)"))
      (libsource (lib "eagle-import") (part "DF13-4P-1.25V"))
    )
    (comp (ref "J309")
      (value "DF13-5P-1.25V")
      (footprint "eagle-import:DF13C-5P-1.25V")
      (fields (field (name "PARTNO") "DF13C-5P-1.25V(20)"))
      (libsource (lib "eagle-import") (part "DF13-5P-1.25V"))
    )
    (comp (ref "J310")
      (value "DF13-4P-1.25V")
      (footprint "eagle-import:DF13C-4P-1.25V")
      (fields (field (name "PARTNO") "DF13C-4P-1.25V(20)"))
      (libsource (lib "eagle-import") (part "DF13-4P-1.25V"))
    )
    (comp (ref "J314")
      (value "DF13-4P-1.25V")
      (footprint "eagle-import:DF13C-4P-1.25V")
      (fields (field (name "PARTNO") "DF13C-4P-1.25V(20)"))
      (libsource (lib "eagle-import") (part "DF13-4P-1.25V"))
    )
    (comp (ref "JP1")
      (value "JP1Q")
      (footprint "eagle-import:JP1")
      (fields (field (name "PARTNO") "1-87215-0"))
      (libsource (lib "eagle-import") (part "JP1Q"))
    )
    (comp (ref "L301")
      (value "KNH16C104DA5TS")
      (footprint "eagle-import:KYOCERA-KNH16-DA")
      (libsource (lib "eagle-import") (part "KNH16C104DA5TS"))
    )
    (comp (ref "L302")
      (value "KNH16C104DA5TS")
      (footprint "eagle-import:KYOCERA-KNH16-DA")
      (libsource (lib "eagle-import") (part "KNH16C104DA5TS"))
    )
    (comp (ref "L303")
      (value "KNH16C104DA5TS")
      (footprint "eagle-import:KYOCERA-KNH16-DA")
      (libsource (lib "eagle-import") (part "KNH16C104DA5TS"))
    )
    (comp (ref "R5")
      (value "10K/0.1%")
      (footprint "eagle-import:0402-RES")
      (fields (field (name "PARTNO") "ERA-2AEB103X"))
      (libsource (lib "eagle-import") (part "RESISTOR0402-RES"))
    )
    (comp (ref "R6")
      (value "10K/0.1%")
      (footprint "eagle-import:0402-RES")
      (fields (field (name "PARTNO") "ERA-2AEB103X"))
      (libsource (lib "eagle-import") (part "RESISTOR0402-RES"))
    )
    (comp (ref "R7")
      (value "10K/0.1%")
      (footprint "eagle-import:0402-RES")
      (fields (field (name "PARTNO") "ERA-2AEB103X"))
      (libsource (lib "eagle-import") (part "RESISTOR0402-RES"))
    )
    (comp (ref "R301")
      (value "1K5")
      (footprint "eagle-import:0402-RES")
      (fields (field (name "PARTNO") "RC0402FR-071K5L"))
      (libsource (lib "eagle-import") (part "RESISTOR0402-RES"))
    )
    (comp (ref "R302")
      (value "1K5")
      (footprint "eagle-import:0402-RES")
      (fields (field (name "PARTNO") "RC0402FR-071K5L"))
      (libsource (lib "eagle-import") (part "RESISTOR0402-RES"))
    )
    (comp (ref "R303")
      (value "10K/0.1%")
      (footprint "eagle-import:0402-RES")
      (fields (field (name "PARTNO") "ERA-2AEB103X"))
      (libsource (lib "eagle-import") (part "RESISTOR0402-RES"))
    )
    (comp (ref "R304")
      (value "1K5")
      (footprint "eagle-import:0402-RES")
      (fields (field (name "PARTNO") "RC0402FR-071K5L"))
      (libsource (lib "eagle-import") (part "RESISTOR0402-RES"))
    )
    (comp (ref "R305")
      (value "1K5")
      (footprint "eagle-import:0402-RES")
      (fields (field (name "PARTNO") "RC0402FR-071K5L"))
      (libsource (lib "eagle-import") (part "RESISTOR0402-RES"))
    )
    (comp (ref "R306")
      (value "10K/0.1%")
      (footprint "eagle-import:0402-RES")
      (fields (field (name "PARTNO") "ERA-2AEB103X"))
      (libsource (lib "eagle-import") (part "RESISTOR0402-RES"))
    )
    (comp (ref "R307")
      (value "10K/0.1%")
      (footprint "eagle-import:0402-RES")
      (fields (field (name "PARTNO") "ERA-2AEB103X"))
      (libsource (lib "eagle-import") (part "RESISTOR0402-RES"))
    )
    (comp (ref "R308")
      (value "10K/0.1%")
      (footprint "eagle-import:0402-RES")
      (fields (field (name "PARTNO") "ERA-2AEB103X"))
      (libsource (lib "eagle-import") (part "RESISTOR0402-RES"))
    )
    (comp (ref "R309")
      (value "120R")
      (footprint "eagle-import:0402-RES")
      (fields (field (name "PARTNO") "RC0402FR-07120RL"))
      (libsource (lib "eagle-import") (part "RESISTOR0402-RES"))
    )
    (comp (ref "R310")
      (value "10K/0.1%")
      (footprint "eagle-import:0402-RES")
      (fields (field (name "PARTNO") "ERA-2AEB103X"))
      (libsource (lib "eagle-import") (part "RESISTOR0402-RES"))
    )
    (comp (ref "R311")
      (value "10K/0.1%")
      (footprint "eagle-import:0402-RES")
      (fields (field (name "PARTNO") "ERA-2AEB103X"))
      (libsource (lib "eagle-import") (part "RESISTOR0402-RES"))
    )
    (comp (ref "R312")
      (value "220R")
      (footprint "eagle-import:0402-RES")
      (fields (field (name "PARTNO") "RC0402FR-07220RL"))
      (libsource (lib "eagle-import") (part "RESISTOR0402-RES"))
    )
    (comp (ref "R313")
      (value "220R")
      (footprint "eagle-import:0402-RES")
      (fields (field (name "PARTNO") "RC0402FR-07220RL"))
      (libsource (lib "eagle-import") (part "RESISTOR0402-RES"))
    )
    (comp (ref "R314")
      (value "10K")
      (footprint "eagle-import:0402-RES")
      (fields (field (name "PARTNO") "ERA-2AEB103X"))
      (libsource (lib "eagle-import") (part "RESISTOR0402-RES"))
    )
    (comp (ref "R315")
      (value "0R")
      (footprint "eagle-import:0402-RES")
      (fields (field (name "PARTNO") "RC0402FR-070RL"))
      (libsource (lib "eagle-import") (part "RESISTOR0402-RES"))
    )
    (comp (ref "U102")
      (value "FM25V01")
      (footprint "eagle-import:SO08")
      (fields (field (name "PARTNO") "FM25V01-G"))
      (libsource (lib "eagle-import") (part "FM25V01"))
    )
    (comp (ref "U301")
      (value "MAX3051")
      (footprint "eagle-import:SOT23-8")
      (fields (field (name "PARTNO") "MAX3051EKA"))
      (libsource (lib "eagle-import") (part "MAX3051MAX3051EKA"))
    )
    (comp (ref "U302")
      (value "TXS0108QFN20")
      (footprint "eagle-import:QFN20-RGY")
      (fields (field (name "PARTNO") "TXS0108ERGYR"))
      (libsource (lib "eagle-import") (part "TXS0108QFN20"))
    )
    (comp (ref "U303")
      (value "PCA9306")
      (footprint "eagle-import:PCA9306")
      (fields (field (name "PARTNO") "PCA9306DQER"))
      (libsource (lib "eagle-import") (part "PCA9306"))
    )
    (comp (ref "C401")
      (value "0u1")
      (footprint "eagle-import:0402-CAP")
      (fields (field (name "PARTNO") "CC0402ZRY5V7BB104"))
      (libsource (lib "eagle-import") (part "CAP0402"))
    )
    (comp (ref "C402")
      (value "4.7u")
      (footprint "eagle-import:0603-CAP")
      (fields (field (name "PARTNO") "C1608X7S1A475K080AC"))
      (libsource (lib "eagle-import") (part "CAP0603"))
    )
    (comp (ref "C403")
      (value "0.22u")
      (footprint "eagle-import:0603-CAP")
      (fields (field (name "PARTNO") "CL10B224JP8NNNC"))
      (libsource (lib "eagle-import") (part "CAP0603"))
    )
    (comp (ref "C405")
      (value "0u1")
      (footprint "eagle-import:0603-CAP")
      (fields (field (name "PARTNO") "CL10B104JO8NNNC"))
      (libsource (lib "eagle-import") (part "CAP0603"))
    )
    (comp (ref "C406")
      (value "10u")
      (footprint "eagle-import:0603-CAP")
      (fields (field (name "PARTNO") "C1608X7S0J106M080AC"))
      (libsource (lib "eagle-import") (part "CAP0603"))
    )
    (comp (ref "C407")
      (value "10u/10V")
      (footprint "eagle-import:0805-CAP")
      (fields (field (name "PARTNO") "CC0805ZKY5V6BB106"))
      (libsource (lib "eagle-import") (part "CAP0805"))
    )
    (comp (ref "C408")
      (value "0u1")
      (footprint "eagle-import:0402-CAP")
      (fields (field (name "PARTNO") "CC0402ZRY5V7BB104"))
      (libsource (lib "eagle-import") (part "CAP0402"))
    )
    (comp (ref "C409")
      (value "2u2")
      (footprint "eagle-import:0603-CAP")
      (fields (field (name "PARTNO") "C1608X6S1C225K080AC"))
      (libsource (lib "eagle-import") (part "CAP0603"))
    )
    (comp (ref "C410")
      (value "10n")
      (footprint "eagle-import:0603-CAP")
      (fields (field (name "PARTNO") "C0603C103J5RAC7411"))
      (libsource (lib "eagle-import") (part "CAP0603"))
    )
    (comp (ref "C411")
      (value "2u2")
      (footprint "eagle-import:0603-CAP")
      (fields (field (name "PARTNO") "C1608X6S1C225K080AC"))
      (libsource (lib "eagle-import") (part "CAP0603"))
    )
    (comp (ref "C412")
      (value "2u2")
      (footprint "eagle-import:0603-CAP")
      (fields (field (name "PARTNO") "CGA3E1X7R0J225K080AC"))
      (libsource (lib "eagle-import") (part "CAP0603"))
    )
    (comp (ref "C413")
      (value "2u2")
      (footprint "eagle-import:0603-CAP")
      (libsource (lib "eagle-import") (part "CAP0603"))
    )
    (comp (ref "C414")
      (value "2200p")
      (footprint "eagle-import:0402-CAP")
      (fields (field (name "PARTNO") "C0603C222J5RACTU"))
      (libsource (lib "eagle-import") (part "CAP0402"))
    )
    (comp (ref "C415")
      (value "u1F")
      (footprint "eagle-import:0402-CAP")
      (fields (field (name "PARTNO") "CC0402ZRY5V7BB104"))
      (libsource (lib "eagle-import") (part "CAP0402"))
    )
    (comp (ref "C416")
      (value "0u01")
      (footprint "eagle-import:0603-CAP")
      (fields (field (name "PARTNO") "06033C103JAT2A"))
      (libsource (lib "eagle-import") (part "CAP0603"))
    )
    (comp (ref "U401")
      (value "MS5611-01BA")
      (footprint "eagle-import:MS5611-01BA")
      (libsource (lib "eagle-import") (part "MS5611-01BA"))
    )
    (comp (ref "U403")
      (value "MPU-6000")
      (footprint "eagle-import:QFN-24")
      (libsource (lib "eagle-import") (part "MPU-6000"))
    )
    (comp (ref "U405")
      (value "MPU-9250")
      (footprint "eagle-import:MPU-6500")
      (libsource (lib "eagle-import") (part "MPU-6500"))
    )
    (comp (ref "U406")
      (value "LSM9DS0LSM9DS0")
      (footprint "eagle-import:LSM9DS0")
      (fields (field (name "PARTNO") "LSM9DS0TR"))
      (libsource (lib "eagle-import") (part "LSM9DS0LSM9DS0"))
    )
    (comp (ref "C602")
      (value "1u0")
      (footprint "eagle-import:0603-CAP")
      (fields (field (name "PARTNO") "CC0603ZRY5V7BB105"))
      (libsource (lib "eagle-import") (part "CAP0603"))
    )
    (comp (ref "C603")
      (value "5n6")
      (footprint "eagle-import:0402-CAP")
      (fields (field (name "PARTNO") "CC0402KRX7R7BB562"))
      (libsource (lib "eagle-import") (part "CAP0402"))
    )
    (comp (ref "C604")
      (value "0u47")
      (footprint "eagle-import:0402-CAP")
      (fields (field (name "PARTNO") "C1005X5R1C474K050BC"))
      (libsource (lib "eagle-import") (part "CAP0402"))
    )
    (comp (ref "D601")
      (value "PESD0402-140")
      (footprint "eagle-import:0402-TVS")
      (libsource (lib "eagle-import") (part "DIODE-TVS"))
    )
    (comp (ref "JP600")
      (value "JP1Q")
      (footprint "eagle-import:JP1")
      (fields (field (name "PARTNO") "1-87215-0"))
      (libsource (lib "eagle-import") (part "JP1Q"))
    )
    (comp (ref "L601")
      (value "47uH")
      (footprint "eagle-import:0805-IND")
      (fields (field (name "PARTNO") "MLZ2012M470W"))
      (libsource (lib "eagle-import") (part "INDUCTOR0805"))
    )
    (comp (ref "LED601")
      (value "GREEN")
      (footprint "eagle-import:0603-LED")
      (fields (field (name "PARTNO") "APTD1608CGCK"))
      (libsource (lib "eagle-import") (part "LED0603"))
    )
    (comp (ref "LED602")
      (value "AMBER")
      (footprint "eagle-import:0603-LED")
      (fields (field (name "PARTNO") "APTD1608SECK"))
      (libsource (lib "eagle-import") (part "LED0603"))
    )
    (comp (ref "LED603")
      (value "BLUE")
      (footprint "eagle-import:0603-LED")
      (fields (field (name "PARTNO") "APTD1608QBC/D"))
      (libsource (lib "eagle-import") (part "LED0603"))
    )
    (comp (ref "R602")
      (value "9K09")
      (footprint "eagle-import:0402-RES")
      (fields (field (name "PARTNO") "RMCF0402FT9K09"))
      (libsource (lib "eagle-import") (part "RESISTOR0402-RES"))
    )
    (comp (ref "R603")
      (value "10K")
      (footprint "eagle-import:0402-RES")
      (fields (field (name "PARTNO") "ERA-2AEB103X"))
      (libsource (lib "eagle-import") (part "RESISTOR0402-RES"))
    )
    (comp (ref "R604")
      (value "100K")
      (footprint "eagle-import:0402-RES")
      (fields (field (name "PARTNO") "RC0402FR-07100KL"))
      (libsource (lib "eagle-import") (part "RESISTOR0402-RES"))
    )
    (comp (ref "R606")
      (value "453K")
      (footprint "eagle-import:0402-RES")
      (fields (field (name "PARTNO") "RMCF0402FT453K"))
      (libsource (lib "eagle-import") (part "RESISTOR0402-RES"))
    )
    (comp (ref "R607")
      (value "16K5")
      (footprint "eagle-import:0402-RES")
      (fields (field (name "PARTNO") "RMCF0402FT16K5"))
      (libsource (lib "eagle-import") (part "RESISTOR0402-RES"))
    )
    (comp (ref "R608")
      (value "220R")
      (footprint "eagle-import:0402-RES")
      (fields (field (name "PARTNO") "RC0402FR-07220RL"))
      (libsource (lib "eagle-import") (part "RESISTOR0402-RES"))
    )
    (comp (ref "R609")
      (value "220R")
      (footprint "eagle-import:0402-RES")
      (fields (field (name "PARTNO") "RC0402FR-07220RL"))
      (libsource (lib "eagle-import") (part "RESISTOR0402-RES"))
    )
    (comp (ref "R610")
      (value "220R")
      (footprint "eagle-import:0402-RES")
      (fields (field (name "PARTNO") "RC0402FR-07220RL"))
      (libsource (lib "eagle-import") (part "RESISTOR0402-RES"))
    )
    (comp (ref "R611")
      (value "68R")
      (footprint "eagle-import:0402-RES")
      (fields (field (name "PARTNO") "RC0402FR-0768RL"))
      (libsource (lib "eagle-import") (part "RESISTOR0402-RES"))
    )
    (comp (ref "R612")
      (value "220R")
      (footprint "eagle-import:0402-RES")
      (fields (field (name "PARTNO") "RC0402FR-07220RL"))
      (libsource (lib "eagle-import") (part "RESISTOR0402-RES"))
    )
    (comp (ref "R613")
      (value "1K5")
      (footprint "eagle-import:0402-RES")
      (fields (field (name "PARTNO") "RC0402FR-071K5L"))
      (libsource (lib "eagle-import") (part "RESISTOR0402-RES"))
    )
    (comp (ref "R614")
      (value "100K")
      (footprint "eagle-import:0402-RES")
      (fields (field (name "PARTNO") "RC0402FR-07100KL"))
      (libsource (lib "eagle-import") (part "RESISTOR0402-RES"))
    )
    (comp (ref "U$11")
      (value "DF13-2P-1.25")
      (footprint "eagle-import:DF13C-2P-1.25V")
      (fields (field (name "PARTNO") "DF13C-2P-1.25V(20)"))
      (libsource (lib "eagle-import") (part "DF13-2P-1.25"))
    )
    (comp (ref "U$12")
      (value "DF13-3P-1.25V")
      (footprint "eagle-import:DF13C-3P-1.25V")
      (fields (field (name "PARTNO") "DF13C-3P-1.25V(20)"))
      (libsource (lib "eagle-import") (part "DF13-3P-1.25V"))
    )
    (comp (ref "U602")
      (value "LT3469")
      (footprint "eagle-import:SOT23-8")
      (fields (field (name "PARTNO") "LT3469ETS8"))
      (libsource (lib "eagle-import") (part "LT3469"))
    )
    (comp (ref "C702")
      (value "0u1")
      (footprint "eagle-import:0402-CAP")
      (fields (field (name "PARTNO") "CC0402ZRY5V7BB104"))
      (libsource (lib "eagle-import") (part "CAP0402"))
    )
    (comp (ref "C703")
      (value "0u1")
      (footprint "eagle-import:0402-CAP")
      (fields (field (name "PARTNO") "CC0402ZRY5V7BB104"))
      (libsource (lib "eagle-import") (part "CAP0402"))
    )
    (comp (ref "D703")
      (value "PESD0402-140")
      (footprint "eagle-import:0402-TVS")
      (libsource (lib "eagle-import") (part "DIODE-TVS"))
    )
    (comp (ref "D704")
      (value "DIODE-SCHOTTKY_MSMP")
      (footprint "eagle-import:MICROSMP")
      (fields (field (name "PARTNO") "SS14"))
      (libsource (lib "eagle-import") (part "DIODE-SCHOTTKY_MSMP"))
    )
    (comp (ref "D705")
      (value "DIODE-SCHOTTKY_MSMP")
      (footprint "eagle-import:MICROSMP")
      (fields (field (name "PARTNO") "SS14"))
      (libsource (lib "eagle-import") (part "DIODE-SCHOTTKY_MSMP"))
    )
    (comp (ref "D706")
      (value "PESD0402-140")
      (footprint "eagle-import:0402-TVS")
      (libsource (lib "eagle-import") (part "DIODE-TVS"))
    )
    (comp (ref "F701")
      (value "0ZCA0035FF2G")
      (footprint "eagle-import:PTC-1206")
      (libsource (lib "eagle-import") (part "PTCSMD"))
    )
    (comp (ref "J701")
      (value "JST-ZH-3")
      (footprint "eagle-import:JST-ZH-SMT-VERTICAL")
      (fields (field (name "PARTNO") "B3B-ZR-SM4-TF (LF)(SN)(P)"))
      (libsource (lib "eagle-import") (part "JST-ZH-3"))
    )
    (comp (ref "L701")
      (value "KNH16C104DA5TS")
      (footprint "eagle-import:KYOCERA-KNH16-DA")
      (libsource (lib "eagle-import") (part "KNH16C104DA5TS"))
    )
    (comp (ref "R3")
      (value "100K/0.1%")
      (footprint "eagle-import:0402-RES")
      (fields (field (name "PARTNO") "ERA-2AEB104X"))
      (libsource (lib "eagle-import") (part "RESISTOR0402-RES"))
    )
    (comp (ref "R8")
      (value "220R")
      (footprint "eagle-import:0402-RES")
      (fields (field (name "PARTNO") "RC0402FR-07220RL"))
      (libsource (lib "eagle-import") (part "RESISTOR0402-RES"))
    )
    (comp (ref "R9")
      (value "220R")
      (footprint "eagle-import:0402-RES")
      (fields (field (name "PARTNO") "RC0402FR-07220RL"))
      (libsource (lib "eagle-import") (part "RESISTOR0402-RES"))
    )
    (comp (ref "R701")
      (value "220R")
      (footprint "eagle-import:0402-RES")
      (fields (field (name "PARTNO") "RC0402FR-07120RL"))
      (libsource (lib "eagle-import") (part "RESISTOR0402-RES"))
    )
    (comp (ref "R702")
      (value "220R")
      (footprint "eagle-import:0402-RES")
      (fields (field (name "PARTNO") "RC0402FR-07120RL"))
      (libsource (lib "eagle-import") (part "RESISTOR0402-RES"))
    )
    (comp (ref "R703")
      (value "220R")
      (footprint "eagle-import:0402-RES")
      (fields (field (name "PARTNO") "RC0402FR-07120RL"))
      (libsource (lib "eagle-import") (part "RESISTOR0402-RES"))
    )
    (comp (ref "R704")
      (value "220R")
      (footprint "eagle-import:0402-RES")
      (fields (field (name "PARTNO") "RC0402FR-07120RL"))
      (libsource (lib "eagle-import") (part "RESISTOR0402-RES"))
    )
    (comp (ref "R705")
      (value "220R")
      (footprint "eagle-import:0402-RES")
      (fields (field (name "PARTNO") "RC0402FR-07120RL"))
      (libsource (lib "eagle-import") (part "RESISTOR0402-RES"))
    )
    (comp (ref "R706")
      (value "220R")
      (footprint "eagle-import:0402-RES")
      (fields (field (name "PARTNO") "RC0402FR-07120RL"))
      (libsource (lib "eagle-import") (part "RESISTOR0402-RES"))
    )
    (comp (ref "R707")
      (value "220R")
      (footprint "eagle-import:0402-RES")
      (fields (field (name "PARTNO") "RC0402FR-07120RL"))
      (libsource (lib "eagle-import") (part "RESISTOR0402-RES"))
    )
    (comp (ref "R708")
      (value "220R")
      (footprint "eagle-import:0402-RES")
      (fields (field (name "PARTNO") "RC0402FR-07120RL"))
      (libsource (lib "eagle-import") (part "RESISTOR0402-RES"))
    )
    (comp (ref "R709")
      (value "220R")
      (footprint "eagle-import:0402-RES")
      (fields (field (name "PARTNO") "RC0402FR-07120RL"))
      (libsource (lib "eagle-import") (part "RESISTOR0402-RES"))
    )
    (comp (ref "R710")
      (value "220R")
      (footprint "eagle-import:0402-RES")
      (fields (field (name "PARTNO") "RC0402FR-07120RL"))
      (libsource (lib "eagle-import") (part "RESISTOR0402-RES"))
    )
    (comp (ref "R711")
      (value "220R")
      (footprint "eagle-import:0402-RES")
      (fields (field (name "PARTNO") "RC0402FR-07120RL"))
      (libsource (lib "eagle-import") (part "RESISTOR0402-RES"))
    )
    (comp (ref "R712")
      (value "220R")
      (footprint "eagle-import:0402-RES")
      (fields (field (name "PARTNO") "RC0402FR-07120RL"))
      (libsource (lib "eagle-import") (part "RESISTOR0402-RES"))
    )
    (comp (ref "R713")
      (value "220R")
      (footprint "eagle-import:0402-RES")
      (fields (field (name "PARTNO") "RC0402FR-07120RL"))
      (libsource (lib "eagle-import") (part "RESISTOR0402-RES"))
    )
    (comp (ref "R714")
      (value "220R")
      (footprint "eagle-import:0402-RES")
      (fields (field (name "PARTNO") "RC0402FR-07120RL"))
      (libsource (lib "eagle-import") (part "RESISTOR0402-RES"))
    )
    (comp (ref "R716")
      (value "10K/0.1%")
      (footprint "eagle-import:0402-RES")
      (fields (field (name "PARTNO") "ERA-2AEB103X"))
      (libsource (lib "eagle-import") (part "RESISTOR0402-RES"))
    )
    (comp (ref "R718")
      (value "10K")
      (footprint "eagle-import:0402-RES")
      (fields (field (name "PARTNO") "ERA-2AEB103X"))
      (libsource (lib "eagle-import") (part "RESISTOR0402-RES"))
    )
    (comp (ref "R719")
      (value "10K")
      (footprint "eagle-import:0402-RES")
      (fields (field (name "PARTNO") "ERA-2AEB103X"))
      (libsource (lib "eagle-import") (part "RESISTOR0402-RES"))
    )
    (comp (ref "U701")
      (value "TXS0108QFN20")
      (footprint "eagle-import:QFN20-RGY")
      (fields (field (name "PARTNO") "TXS0108ERGYR"))
      (libsource (lib "eagle-import") (part "TXS0108QFN20"))
    )
    (comp (ref "U702")
      (value "TXS0108QFN20")
      (footprint "eagle-import:QFN20-RGY")
      (fields (field (name "PARTNO") "TXS0108ERGYR"))
      (libsource (lib "eagle-import") (part "TXS0108QFN20"))
    )
    (comp (ref "U704")
      (value "BBB_3X14_RA")
      (footprint "eagle-import:3X14RA")
      (fields (field (name "PARTNO") "07579"))
      (libsource (lib "eagle-import") (part "BBB_3X14_RA"))
    )
    (comp (ref "C201")
      (value "0u1")
      (footprint "eagle-import:0402-CAP")
      (fields (field (name "PARTNO") "CC0402ZRY5V7BB104"))
      (libsource (lib "eagle-import") (part "CAP0402"))
    )
    (comp (ref "D201")
      (value "PESD0402-140")
      (footprint "eagle-import:0402-TVS")
      (libsource (lib "eagle-import") (part "DIODE-TVS"))
    )
    (comp (ref "D202")
      (value "PESD0402-140")
      (footprint "eagle-import:0402-TVS")
      (libsource (lib "eagle-import") (part "DIODE-TVS"))
    )
    (comp (ref "D203")
      (value "PESD0402-140")
      (footprint "eagle-import:0402-TVS")
      (libsource (lib "eagle-import") (part "DIODE-TVS"))
    )
    (comp (ref "L201")
      (value "KNH16C104DA5TS")
      (footprint "eagle-import:KYOCERA-KNH16-DA")
      (libsource (lib "eagle-import") (part "KNH16C104DA5TS"))
    )
    (comp (ref "L202")
      (value "KNH16C104DA5TS")
      (footprint "eagle-import:KYOCERA-KNH16-DA")
      (libsource (lib "eagle-import") (part "KNH16C104DA5TS"))
    )
    (comp (ref "L203")
      (value "KNH16C104DA5TS")
      (footprint "eagle-import:KYOCERA-KNH16-DA")
      (libsource (lib "eagle-import") (part "KNH16C104DA5TS"))
    )
    (comp (ref "R201")
      (value "120R")
      (footprint "eagle-import:0402-RES")
      (fields (field (name "PARTNO") "RC0402FR-07120RL"))
      (libsource (lib "eagle-import") (part "RESISTOR0402-RES"))
    )
    (comp (ref "R202")
      (value "120R")
      (footprint "eagle-import:0402-RES")
      (fields (field (name "PARTNO") "RC0402FR-07120RL"))
      (libsource (lib "eagle-import") (part "RESISTOR0402-RES"))
    )
    (comp (ref "R203")
      (value "120R")
      (footprint "eagle-import:0402-RES")
      (fields (field (name "PARTNO") "RC0402FR-07120RL"))
      (libsource (lib "eagle-import") (part "RESISTOR0402-RES"))
    )
    (comp (ref "R204")
      (value "120R")
      (footprint "eagle-import:0402-RES")
      (fields (field (name "PARTNO") "RC0402FR-07120RL"))
      (libsource (lib "eagle-import") (part "RESISTOR0402-RES"))
    )
    (comp (ref "R205")
      (value "120R")
      (footprint "eagle-import:0402-RES")
      (fields (field (name "PARTNO") "RC0402FR-07120RL"))
      (libsource (lib "eagle-import") (part "RESISTOR0402-RES"))
    )
    (comp (ref "R208")
      (value "120R")
      (footprint "eagle-import:0402-RES")
      (fields (field (name "PARTNO") "RC0402FR-07120RL"))
      (libsource (lib "eagle-import") (part "RESISTOR0402-RES"))
    )
    (comp (ref "R209")
      (value "120R")
      (footprint "eagle-import:0402-RES")
      (fields (field (name "PARTNO") "RC0402FR-07120RL"))
      (libsource (lib "eagle-import") (part "RESISTOR0402-RES"))
    )
    (comp (ref "R210")
      (value "120R")
      (footprint "eagle-import:0402-RES")
      (fields (field (name "PARTNO") "RC0402FR-07120RL"))
      (libsource (lib "eagle-import") (part "RESISTOR0402-RES"))
    )
    (comp (ref "R211")
      (value "120R")
      (footprint "eagle-import:0402-RES")
      (fields (field (name "PARTNO") "RC0402FR-07120RL"))
      (libsource (lib "eagle-import") (part "RESISTOR0402-RES"))
    )
    (comp (ref "R212")
      (value "120R")
      (footprint "eagle-import:0402-RES")
      (fields (field (name "PARTNO") "RC0402FR-07120RL"))
      (libsource (lib "eagle-import") (part "RESISTOR0402-RES"))
    )
    (comp (ref "R215")
      (value "10K")
      (footprint "eagle-import:0402-RES")
      (fields (field (name "PARTNO") "ERA-2AEB103X"))
      (libsource (lib "eagle-import") (part "RESISTOR0402-RES"))
    )
    (comp (ref "U$2")
      (value "DF13-6P-1.25V")
      (footprint "eagle-import:DF13C-6P-1.25V")
      (fields (field (name "PARTNO") "DF13C-6P-1.25V(20)"))
      (libsource (lib "eagle-import") (part "pxf_DF13-6P-1.25V"))
    )
    (comp (ref "U$4")
      (value "DF13-6P-1.25V")
      (footprint "eagle-import:DF13C-6P-1.25V")
      (fields (field (name "PARTNO") "DF13C-6P-1.25V(20)"))
      (libsource (lib "eagle-import") (part "pxf_DF13-6P-1.25V"))
    )
    (comp (ref "U$201")
      (value "DF13-6P-1.25V")
      (footprint "eagle-import:DF13C-6P-1.25V")
      (fields (field (name "PARTNO") "DF13C-6P-1.25V(20)"))
      (libsource (lib "eagle-import") (part "pxf_DF13-6P-1.25V"))
    )
    (comp (ref "U201")
      (value "TXS0108QFN20")
      (footprint "eagle-import:QFN20-RGY")
      (fields (field (name "PARTNO") "TXS0108ERGYR"))
      (libsource (lib "eagle-import") (part "TXS0108QFN20"))
    )
  )
  (nets
    (net (code "1") (name "3V3_EN") (class "Default")
      (node (ref "R102") (pin "P$2") (pinfunction "2_P$2") (pintype "passive"))
      (node (ref "R503") (pin "P$2") (pinfunction "2_P$2") (pintype "passive"))
      (node (ref "U$101") (pin "56") (pinfunction "SYS_RESETN_10_56") (pintype "passive"))
      (node (ref "U$101") (pin "73") (pinfunction "27_PRU1_R30/31[5]_73") (pintype "passive"))
      (node (ref "U502") (pin "4") (pinfunction "EN2_4") (pintype "bidirectional"))
      (node (ref "U502") (pin "5") (pinfunction "EN1_5") (pintype "bidirectional"))
    )
    (net (code "2") (name "3_VDD_3V3") (class "Default")
      (node (ref "U$101") (pin "49") (pinfunction "3_VDD_3V3_49") (pintype "power_in"))
    )
    (net (code "3") (name "ACCEL_DRDY") (class "Default")
      (node (ref "U$101") (pin "8") (pinfunction "GPIO2[3]_8_8") (pintype "passive"))
      (node (ref "U406") (pin "14") (pinfunction "INT2_XM_14") (pintype "bidirectional"))
    )
    (net (code "4") (name "ALARM") (class "Default")
      (node (ref "R602") (pin "P$2") (pinfunction "2_P$2") (pintype "passive"))
      (node (ref "U$101") (pin "36") (pinfunction "GPIO2[16]_36_36") (pintype "passive"))
    )
    (net (code "5") (name "AUX_ADC1") (class "Default")
      (node (ref "R308") (pin "P$1") (pinfunction "1_P$1") (pintype "passive"))
      (node (ref "U$101") (pin "83") (pinfunction "37_AIN2_83") (pintype "passive"))
    )
    (net (code "6") (name "AUX_ADC2") (class "Default")
      (node (ref "R307") (pin "P$1") (pinfunction "1_P$1") (pintype "passive"))
      (node (ref "U$101") (pin "84") (pinfunction "AIN3_38_84") (pintype "passive"))
    )
    (net (code "7") (name "BACKUP_LIPO_+_1S") (class "Default")
      (node (ref "U$101") (pin "TP5") (pinfunction "BAT_+_LIPO_1_S_TP5") (pintype "bidirectional"))
      (node (ref "X801") (pin "1") (pinfunction "S_1") (pintype "passive"))
    )
    (net (code "8") (name "BATT_CURRENT_SENS") (class "Default")
      (node (ref "R1") (pin "P$1") (pinfunction "1_P$1") (pintype "passive"))
      (node (ref "R808") (pin "P$1") (pinfunction "1_P$1") (pintype "passive"))
      (node (ref "U$101") (pin "81") (pinfunction "35_AIN6_81") (pintype "passive"))
    )
    (net (code "9") (name "BATT_SENSE") (class "Default")
      (node (ref "U$101") (pin "TP6") (pinfunction "BAT_SENSE_TP6") (pintype "bidirectional"))
      (node (ref "X801") (pin "2") (pinfunction "S_2") (pintype "passive"))
    )
    (net (code "10") (name "BATT_TEMP_SENSE") (class "Default")
      (node (ref "U$101") (pin "TP7") (pinfunction "TEMP_SENSE_TP7") (pintype "bidirectional"))
      (node (ref "X801") (pin "3") (pinfunction "S_3") (pintype "passive"))
    )
    (net (code "11") (name "BATT_VOLTAGE_SENS") (class "Default")
      (node (ref "R2") (pin "P$1") (pinfunction "1_P$1") (pintype "passive"))
      (node (ref "R807") (pin "P$1") (pinfunction "1_P$1") (pintype "passive"))
      (node (ref "U$101") (pin "82") (pinfunction "AIN5_36_82") (pintype "passive"))
    )
    (net (code "12") (name "BBB-VDD_3V3") (class "Default")
      (node (ref "C201") (pin "P$1") (pinfunction "1_P$1") (pintype "passive"))
      (node (ref "C302") (pin "P$1") (pinfunction "1_P$1") (pintype "passive"))
      (node (ref "C303") (pin "P$1") (pinfunction "1_P$1") (pintype "passive"))
      (node (ref "C304") (pin "P$1") (pinfunction "1_P$1") (pintype "passive"))
      (node (ref "C505") (pin "P$1") (pinfunction "1_P$1") (pintype "passive"))
      (node (ref "C506") (pin "P$1") (pinfunction "1_P$1") (pintype "passive"))
      (node (ref "C507") (pin "P$1") (pinfunction "1_P$1") (pintype "passive"))
      (node (ref "C702") (pin "P$1") (pinfunction "1_P$1") (pintype "passive"))
      (node (ref "C703") (pin "P$1") (pinfunction "1_P$1") (pintype "passive"))
      (node (ref "D601") (pin "C") (pinfunction "C_C") (pintype "passive"))
      (node (ref "JP1") (pin "2") (pinfunction "2_2") (pintype "passive"))
      (node (ref "R215") (pin "P$2") (pinfunction "2_P$2") (pintype "passive"))
      (node (ref "R301") (pin "P$2") (pinfunction "2_P$2") (pintype "passive"))
      (node (ref "R302") (pin "P$2") (pinfunction "2_P$2") (pintype "passive"))
      (node (ref "R304") (pin "P$1") (pinfunction "1_P$1") (pintype "passive"))
      (node (ref "R305") (pin "P$1") (pinfunction "1_P$1") (pintype "passive"))
      (node (ref "R314") (pin "P$2") (pinfunction "2_P$2") (pintype "passive"))
      (node (ref "R502") (pin "P$2") (pinfunction "2_P$2") (pintype "passive"))
      (node (ref "R507") (pin "P$2") (pinfunction "2_P$2") (pintype "passive"))
      (node (ref "R718") (pin "P$2") (pinfunction "2_P$2") (pintype "passive"))
      (node (ref "R719") (pin "P$2") (pinfunction "2_P$2") (pintype "passive"))
      (node (ref "U$12") (pin "1") (pinfunction "1_1") (pintype "passive"))
      (node (ref "U201") (pin "19") (pinfunction "VCCB_19") (pintype "input"))
      (node (ref "U201") (pin "2") (pinfunction "VCCA_2") (pintype "input"))
      (node (ref "U301") (pin "3") (pinfunction "VCC_3") (pintype "input"))
      (node (ref "U302") (pin "10") (pinfunction "OE_10") (pintype "input"))
      (node (ref "U302") (pin "2") (pinfunction "VCCA_2") (pintype "input"))
      (node (ref "U303") (pin "2") (pinfunction "VREF1_2") (pintype "bidirectional"))
      (node (ref "U303") (pin "7") (pinfunction "VREF2_7") (pintype "bidirectional"))
      (node (ref "U303") (pin "8") (pinfunction "EN_8") (pintype "bidirectional"))
      (node (ref "U502") (pin "7") (pinfunction "VOUT2_7") (pintype "bidirectional"))
      (node (ref "U701") (pin "19") (pinfunction "VCCB_19") (pintype "input"))
      (node (ref "U701") (pin "2") (pinfunction "VCCA_2") (pintype "input"))
      (node (ref "U702") (pin "19") (pinfunction "VCCB_19") (pintype "input"))
      (node (ref "U702") (pin "2") (pinfunction "VCCA_2") (pintype "input"))
      (node (ref "VDD_3V901") (pin "P$1") (pinfunction "P$1_P$1") (pintype "passive"))
    )
    (net (code "13") (name "CAN1_RX_1") (class "Default")
      (node (ref "U$101") (pin "70") (pinfunction "UART1/CAN1_TXD_24_70") (pintype "passive"))
      (node (ref "U301") (pin "4") (pinfunction "DOUT_4") (pintype "output"))
    )
    (net (code "14") (name "CAN1_TX_1") (class "Default")
      (node (ref "U$101") (pin "72") (pinfunction "UART1/CAN1_RXD_26_72") (pintype "passive"))
      (node (ref "U301") (pin "1") (pinfunction "DIN_1") (pintype "input"))
    )
    (net (code "15") (name "CAN_H") (class "Default")
      (node (ref "CAN_H") (pin "P$1") (pinfunction "P$1_P$1") (pintype "passive"))
      (node (ref "J307") (pin "2") (pinfunction "2_2") (pintype "passive"))
      (node (ref "R309") (pin "P$1") (pinfunction "1_P$1") (pintype "passive"))
      (node (ref "U301") (pin "7") (pinfunction "CANH_7") (pintype "bidirectional"))
    )
    (net (code "16") (name "CAN_L") (class "Default")
      (node (ref "CAN_L") (pin "P$1") (pinfunction "P$1_P$1") (pintype "passive"))
      (node (ref "J307") (pin "3") (pinfunction "3_3") (pintype "passive"))
      (node (ref "R309") (pin "P$2") (pinfunction "2_P$2") (pintype "passive"))
      (node (ref "U301") (pin "6") (pinfunction "CANL_6") (pintype "bidirectional"))
    )
    (net (code "17") (name "CH_1") (class "Default")
      (node (ref "U$101") (pin "28") (pinfunction "PRU1_R30/31[10]_28_28") (pintype "passive"))
      (node (ref "U701") (pin "5") (pinfunction "A4_5") (pintype "bidirectional"))
    )
    (net (code "18") (name "CH_1_OUT") (class "Default")
      (node (ref "R714") (pin "P$1") (pinfunction "1_P$1") (pintype "passive"))
      (node (ref "U701") (pin "16") (pinfunction "B4_16") (pintype "bidirectional"))
    )
    (net (code "19") (name "CH_2") (class "Default")
      (node (ref "U$101") (pin "27") (pinfunction "27_PRU1_R30/31[8]_27") (pintype "passive"))
      (node (ref "U701") (pin "4") (pinfunction "A3_4") (pintype "bidirectional"))
    )
    (net (code "20") (name "CH_2_OUT") (class "Default")
      (node (ref "R713") (pin "P$1") (pinfunction "1_P$1") (pintype "passive"))
      (node (ref "U701") (pin "17") (pinfunction "B3_17") (pintype "bidirectional"))
    )
    (net (code "21") (name "CH_3") (class "Default")
      (node (ref "U$101") (pin "30") (pinfunction "PRU1_R30/31[11]_30_30") (pintype "passive"))
      (node (ref "U701") (pin "3") (pinfunction "A2_3") (pintype "bidirectional"))
    )
    (net (code "22") (name "CH_3_OUT") (class "Default")
      (node (ref "R712") (pin "P$1") (pinfunction "1_P$1") (pintype "passive"))
      (node (ref "U701") (pin "18") (pinfunction "B2_18") (pintype "bidirectional"))
    )
    (net (code "23") (name "CH_4") (class "Default")
      (node (ref "U$101") (pin "29") (pinfunction "29_PRU1_R30/31[9]_29") (pintype "passive"))
      (node (ref "U701") (pin "1") (pinfunction "A1_1") (pintype "bidirectional"))
    )
    (net (code "24") (name "CH_4_OUT") (class "Default")
      (node (ref "R701") (pin "P$1") (pinfunction "1_P$1") (pintype "passive"))
      (node (ref "U701") (pin "20") (pinfunction "B1_20") (pintype "bidirectional"))
    )
    (net (code "25") (name "CH_5") (class "Default")
      (node (ref "U$101") (pin "40") (pinfunction "PRU1_R30/31[7]_40_40") (pintype "passive"))
      (node (ref "U702") (pin "9") (pinfunction "A8_9") (pintype "bidirectional"))
    )
    (net (code "26") (name "CH_5_OUT") (class "Default")
      (node (ref "R702") (pin "P$1") (pinfunction "1_P$1") (pintype "passive"))
      (node (ref "U702") (pin "12") (pinfunction "B8_12") (pintype "bidirectional"))
    )
    (net (code "27") (name "CH_6") (class "Default")
      (node (ref "U$101") (pin "39") (pinfunction "39_PRU1_R30/31[6]_39") (pintype "passive"))
      (node (ref "U702") (pin "8") (pinfunction "A7_8") (pintype "bidirectional"))
    )
    (net (code "28") (name "CH_6_OUT") (class "Default")
      (node (ref "R703") (pin "P$1") (pinfunction "1_P$1") (pintype "passive"))
      (node (ref "U702") (pin "13") (pinfunction "B7_13") (pintype "bidirectional"))
    )
    (net (code "29") (name "CH_7") (class "Default")
      (node (ref "U$101") (pin "42") (pinfunction "PRU1_R30/31[5]_42_42") (pintype "passive"))
      (node (ref "U702") (pin "7") (pinfunction "A6_7") (pintype "bidirectional"))
    )
    (net (code "30") (name "CH_7_OUT") (class "Default")
      (node (ref "R704") (pin "P$1") (pinfunction "1_P$1") (pintype "passive"))
      (node (ref "U702") (pin "14") (pinfunction "B6_14") (pintype "bidirectional"))
    )
    (net (code "31") (name "CH_8") (class "Default")
      (node (ref "U$101") (pin "41") (pinfunction "41_PRU1_R30/31[4]_41") (pintype "passive"))
      (node (ref "U702") (pin "6") (pinfunction "A5_6") (pintype "bidirectional"))
    )
    (net (code "32") (name "CH_8_OUT") (class "Default")
      (node (ref "R705") (pin "P$1") (pinfunction "1_P$1") (pintype "passive"))
      (node (ref "U702") (pin "15") (pinfunction "B5_15") (pintype "bidirectional"))
    )
    (net (code "33") (name "CH_9") (class "Default")
      (node (ref "U$101") (pin "44") (pinfunction "PRU1_R30/31[3]_44_44") (pintype "passive"))
      (node (ref "U702") (pin "5") (pinfunction "A4_5") (pintype "bidirectional"))
    )
    (net (code "34") (name "CH_9_OUT") (class "Default")
      (node (ref "R706") (pin "P$1") (pinfunction "1_P$1") (pintype "passive"))
      (node (ref "U702") (pin "16") (pinfunction "B4_16") (pintype "bidirectional"))
    )
    (net (code "35") (name "CH_10") (class "Default")
      (node (ref "U$101") (pin "43") (pinfunction "43_PRU1_R30/31[2]_43") (pintype "passive"))
      (node (ref "U702") (pin "4") (pinfunction "A3_4") (pintype "bidirectional"))
    )
    (net (code "36") (name "CH_10_OUT") (class "Default")
      (node (ref "R707") (pin "P$1") (pinfunction "1_P$1") (pintype "passive"))
      (node (ref "U702") (pin "17") (pinfunction "B3_17") (pintype "bidirectional"))
    )
    (net (code "37") (name "CH_11") (class "Default")
      (node (ref "U$101") (pin "46") (pinfunction "PRU1_R30/31[1]_46_46") (pintype "passive"))
      (node (ref "U702") (pin "3") (pinfunction "A2_3") (pintype "bidirectional"))
    )
    (net (code "38") (name "CH_11_OUT") (class "Default")
      (node (ref "R708") (pin "P$1") (pinfunction "1_P$1") (pintype "passive"))
      (node (ref "U702") (pin "18") (pinfunction "B2_18") (pintype "bidirectional"))
    )
    (net (code "39") (name "CH_12") (class "Default")
      (node (ref "U$101") (pin "45") (pinfunction "45_PRU1_R30/31[0]_45") (pintype "passive"))
      (node (ref "U702") (pin "1") (pinfunction "A1_1") (pintype "bidirectional"))
    )
    (net (code "40") (name "CH_12_OUT") (class "Default")
      (node (ref "R709") (pin "P$1") (pinfunction "1_P$1") (pintype "passive"))
      (node (ref "U702") (pin "20") (pinfunction "B1_20") (pintype "bidirectional"))
    )
    (net (code "41") (name "GND") (class "Default")
      (node (ref "C101") (pin "P$2") (pinfunction "2_P$2") (pintype "passive"))
      (node (ref "C201") (pin "P$2") (pinfunction "2_P$2") (pintype "passive"))
      (node (ref "C301") (pin "P$2") (pinfunction "2_P$2") (pintype "passive"))
      (node (ref "C302") (pin "P$2") (pinfunction "2_P$2") (pintype "passive"))
      (node (ref "C303") (pin "P$2") (pinfunction "2_P$2") (pintype "passive"))
      (node (ref "C304") (pin "P$2") (pinfunction "2_P$2") (pintype "passive"))
      (node (ref "C305") (pin "P$2") (pinfunction "2_P$2") (pintype "passive"))
      (node (ref "C401") (pin "P$2") (pinfunction "2_P$2") (pintype "passive"))
      (node (ref "C402") (pin "P$2") (pinfunction "2_P$2") (pintype "passive"))
      (node (ref "C405") (pin "P$1") (pinfunction "1_P$1") (pintype "passive"))
      (node (ref "C406") (pin "P$1") (pinfunction "1_P$1") (pintype "passive"))
      (node (ref "C407") (pin "P$2") (pinfunction "2_P$2") (pintype "passive"))
      (node (ref "C408") (pin "P$2") (pinfunction "2_P$2") (pintype "passive"))
      (node (ref "C409") (pin "P$2") (pinfunction "2_P$2") (pintype "passive"))
      (node (ref "C410") (pin "P$2") (pinfunction "2_P$2") (pintype "passive"))
      (node (ref "C411") (pin "P$2") (pinfunction "2_P$2") (pintype "passive"))
      (node (ref "C412") (pin "P$2") (pinfunction "2_P$2") (pintype "passive"))
      (node (ref "C413") (pin "P$2") (pinfunction "2_P$2") (pintype "passive"))
      (node (ref "C414") (pin "P$2") (pinfunction "2_P$2") (pintype "passive"))
      (node (ref "C415") (pin "P$2") (pinfunction "2_P$2") (pintype "passive"))
      (node (ref "C416") (pin "P$2") (pinfunction "2_P$2") (pintype "passive"))
      (node (ref "C501") (pin "P$2") (pinfunction "2_P$2") (pintype "passive"))
      (node (ref "C502") (pin "P$2") (pinfunction "2_P$2") (pintype "passive"))
      (node (ref "C503") (pin "P$2") (pinfunction "2_P$2") (pintype "passive"))
      (node (ref "C504") (pin "P$2") (pinfunction "2_P$2") (pintype "passive"))
      (node (ref "C505") (pin "P$2") (pinfunction "2_P$2") (pintype "passive"))
      (node (ref "C506") (pin "P$2") (pinfunction "2_P$2") (pintype "passive"))
      (node (ref "C507") (pin "P$2") (pinfunction "2_P$2") (pintype "passive"))
      (node (ref "C508") (pin "P$2") (pinfunction "2_P$2") (pintype "passive"))
      (node (ref "C509") (pin "P$2") (pinfunction "2_P$2") (pintype "passive"))
      (node (ref "C510") (pin "P$2") (pinfunction "2_P$2") (pintype "passive"))
      (node (ref "C602") (pin "P$2") (pinfunction "2_P$2") (pintype "passive"))
      (node (ref "C603") (pin "P$2") (pinfunction "2_P$2") (pintype "passive"))
      (node (ref "C604") (pin "P$2") (pinfunction "2_P$2") (pintype "passive"))
      (node (ref "C702") (pin "P$2") (pinfunction "2_P$2") (pintype "passive"))
      (node (ref "C703") (pin "P$2") (pinfunction "2_P$2") (pintype "passive"))
      (node (ref "C801") (pin "P$2") (pinfunction "2_P$2") (pintype "passive"))
      (node (ref "C805") (pin "P$2") (pinfunction "2_P$2") (pintype "passive"))
      (node (ref "D201") (pin "A") (pinfunction "A_A") (pintype "passive"))
      (node (ref "D202") (pin "A") (pinfunction "A_A") (pintype "passive"))
      (node (ref "D203") (pin "A") (pinfunction "A_A") (pintype "passive"))
      (node (ref "D301") (pin "A") (pinfunction "A_A") (pintype "passive"))
      (node (ref "D302") (pin "A") (pinfunction "A_A") (pintype "passive"))
      (node (ref "D303") (pin "A") (pinfunction "A_A") (pintype "passive"))
      (node (ref "D601") (pin "A") (pinfunction "A_A") (pintype "passive"))
      (node (ref "D703") (pin "A") (pinfunction "A_A") (pintype "passive"))
      (node (ref "D706") (pin "A") (pinfunction "A_A") (pintype "passive"))
      (node (ref "GND") (pin "P$1") (pinfunction "P$1_P$1") (pintype "passive"))
      (node (ref "GND.") (pin "P$1") (pinfunction "P$1_P$1") (pintype "passive"))
      (node (ref "J305") (pin "3") (pinfunction "3_3") (pintype "passive"))
      (node (ref "J305") (pin "P$4") (pinfunction "P$1_P$4") (pintype "bidirectional"))
      (node (ref "J305") (pin "P$5") (pinfunction "P$2_P$5") (pintype "bidirectional"))
      (node (ref "J306") (pin "4") (pinfunction "4_4") (pintype "passive"))
      (node (ref "J306") (pin "P$5") (pinfunction "P$1_P$5") (pintype "bidirectional"))
      (node (ref "J306") (pin "P$6") (pinfunction "P$2_P$6") (pintype "bidirectional"))
      (node (ref "J307") (pin "4") (pinfunction "4_4") (pintype "passive"))
      (node (ref "J307") (pin "P$5") (pinfunction "P$1_P$5") (pintype "bidirectional"))
      (node (ref "J307") (pin "P$6") (pinfunction "P$2_P$6") (pintype "bidirectional"))
      (node (ref "J308") (pin "4") (pinfunction "4_4") (pintype "passive"))
      (node (ref "J308") (pin "P$5") (pinfunction "P$1_P$5") (pintype "bidirectional"))
      (node (ref "J308") (pin "P$6") (pinfunction "P$2_P$6") (pintype "bidirectional"))
      (node (ref "J309") (pin "3") (pinfunction "3_3") (pintype "passive"))
      (node (ref "J309") (pin "5") (pinfunction "5_5") (pintype "passive"))
      (node (ref "J309") (pin "P$6") (pinfunction "P$1_P$6") (pintype "bidirectional"))
      (node (ref "J309") (pin "P$7") (pinfunction "P$2_P$7") (pintype "bidirectional"))
      (node (ref "J310") (pin "4") (pinfunction "4_4") (pintype "passive"))
      (node (ref "J310") (pin "P$5") (pinfunction "P$1_P$5") (pintype "bidirectional"))
      (node (ref "J310") (pin "P$6") (pinfunction "P$2_P$6") (pintype "bidirectional"))
      (node (ref "J314") (pin "4") (pinfunction "4_4") (pintype "passive"))
      (node (ref "J314") (pin "P$5") (pinfunction "P$1_P$5") (pintype "bidirectional"))
      (node (ref "J314") (pin "P$6") (pinfunction "P$2_P$6") (pintype "bidirectional"))
      (node (ref "J701") (pin "P$2") (pinfunction "P$2_P$2") (pintype "bidirectional"))
      (node (ref "J801") (pin "5") (pinfunction "5_5") (pintype "passive"))
      (node (ref "J801") (pin "6") (pinfunction "6_6") (pintype "passive"))
      (node (ref "L201") (pin "P$3") (pinfunction "P$3_P$3") (pintype "bidirectional"))
      (node (ref "L201") (pin "P$4") (pinfunction "P$3_P$4") (pintype "bidirectional"))
      (node (ref "L201") (pin "P$5") (pinfunction "P$3_P$5") (pintype "bidirectional"))
      (node (ref "L202") (pin "P$3") (pinfunction "P$3_P$3") (pintype "bidirectional"))
      (node (ref "L202") (pin "P$4") (pinfunction "P$3_P$4") (pintype "bidirectional"))
      (node (ref "L202") (pin "P$5") (pinfunction "P$3_P$5") (pintype "bidirectional"))
      (node (ref "L203") (pin "P$3") (pinfunction "P$3_P$3") (pintype "bidirectional"))
      (node (ref "L203") (pin "P$4") (pinfunction "P$3_P$4") (pintype "bidirectional"))
      (node (ref "L203") (pin "P$5") (pinfunction "P$3_P$5") (pintype "bidirectional"))
      (node (ref "L301") (pin "P$3") (pinfunction "P$3_P$3") (pintype "bidirectional"))
      (node (ref "L301") (pin "P$4") (pinfunction "P$3_P$4") (pintype "bidirectional"))
      (node (ref "L301") (pin "P$5") (pinfunction "P$3_P$5") (pintype "bidirectional"))
      (node (ref "L302") (pin "P$3") (pinfunction "P$3_P$3") (pintype "bidirectional"))
      (node (ref "L302") (pin "P$4") (pinfunction "P$3_P$4") (pintype "bidirectional"))
      (node (ref "L302") (pin "P$5") (pinfunction "P$3_P$5") (pintype "bidirectional"))
      (node (ref "L303") (pin "P$3") (pinfunction "P$3_P$3") (pintype "bidirectional"))
      (node (ref "L303") (pin "P$4") (pinfunction "P$3_P$4") (pintype "bidirectional"))
      (node (ref "L303") (pin "P$5") (pinfunction "P$3_P$5") (pintype "bidirectional"))
      (node (ref "L501") (pin "P$3") (pinfunction "P$3_P$3") (pintype "bidirectional"))
      (node (ref "L501") (pin "P$4") (pinfunction "P$3_P$4") (pintype "bidirectional"))
      (node (ref "L501") (pin "P$5") (pinfunction "P$3_P$5") (pintype "bidirectional"))
      (node (ref "L701") (pin "P$3") (pinfunction "P$3_P$3") (pintype "bidirectional"))
      (node (ref "L701") (pin "P$4") (pinfunction "P$3_P$4") (pintype "bidirectional"))
      (node (ref "L701") (pin "P$5") (pinfunction "P$3_P$5") (pintype "bidirectional"))
      (node (ref "L801") (pin "P$3") (pinfunction "P$3_P$3") (pintype "bidirectional"))
      (node (ref "L801") (pin "P$4") (pinfunction "P$3_P$4") (pintype "bidirectional"))
      (node (ref "L801") (pin "P$5") (pinfunction "P$3_P$5") (pintype "bidirectional"))
      (node (ref "L802") (pin "P$3") (pinfunction "P$3_P$3") (pintype "bidirectional"))
      (node (ref "L802") (pin "P$4") (pinfunction "P$3_P$4") (pintype "bidirectional"))
      (node (ref "L802") (pin "P$5") (pinfunction "P$3_P$5") (pintype "bidirectional"))
      (node (ref "R102") (pin "P$1") (pinfunction "1_P$1") (pintype "passive"))
      (node (ref "R215") (pin "P$1") (pinfunction "1_P$1") (pintype "passive"))
      (node (ref "R303") (pin "P$1") (pinfunction "1_P$1") (pintype "passive"))
      (node (ref "R310") (pin "P$1") (pinfunction "1_P$1") (pintype "passive"))
      (node (ref "R311") (pin "P$1") (pinfunction "1_P$1") (pintype "passive"))
      (node (ref "R314") (pin "P$1") (pinfunction "1_P$1") (pintype "passive"))
      (node (ref "R315") (pin "P$2") (pinfunction "2_P$2") (pintype "passive"))
      (node (ref "R501") (pin "P$2") (pinfunction "2_P$2") (pintype "passive"))
      (node (ref "R504") (pin "P$2") (pinfunction "2_P$2") (pintype "passive"))
      (node (ref "R505") (pin "1") (pinfunction "1_1") (pintype "passive"))
      (node (ref "R506") (pin "P$2") (pinfunction "2_P$2") (pintype "passive"))
      (node (ref "R509") (pin "P$2") (pinfunction "2_P$2") (pintype "passive"))
      (node (ref "R603") (pin "P$2") (pinfunction "2_P$2") (pintype "passive"))
      (node (ref "R607") (pin "P$2") (pinfunction "2_P$2") (pintype "passive"))
      (node (ref "R608") (pin "P$1") (pinfunction "1_P$1") (pintype "passive"))
      (node (ref "R613") (pin "P$2") (pinfunction "2_P$2") (pintype "passive"))
      (node (ref "R716") (pin "P$1") (pinfunction "1_P$1") (pintype "passive"))
      (node (ref "R718") (pin "P$1") (pinfunction "1_P$1") (pintype "passive"))
      (node (ref "R719") (pin "P$1") (pinfunction "1_P$1") (pintype "passive"))
      (node (ref "R8") (pin "P$1") (pinfunction "1_P$1") (pintype "passive"))
      (node (ref "R801") (pin "P$2") (pinfunction "2_P$2") (pintype "passive"))
      (node (ref "R802") (pin "P$2") (pinfunction "2_P$2") (pintype "passive"))
      (node (ref "R806") (pin "P$1") (pinfunction "1_P$1") (pintype "passive"))
      (node (ref "R807") (pin "P$2") (pinfunction "2_P$2") (pintype "passive"))
      (node (ref "R808") (pin "P$2") (pinfunction "2_P$2") (pintype "passive"))
      (node (ref "U$101") (pin "1") (pinfunction "1_GND_1") (pintype "power_in"))
      (node (ref "U$101") (pin "2") (pinfunction "GND_2_2") (pintype "power_in"))
      (node (ref "U$101") (pin "47") (pinfunction "1_GND_47") (pintype "power_in"))
      (node (ref "U$101") (pin "48") (pinfunction "GND_2_48") (pintype "power_in"))
      (node (ref "U$101") (pin "80") (pinfunction "GNDA_ADC_34_80") (pintype "passive"))
      (node (ref "U$101") (pin "89") (pinfunction "43_GND_89") (pintype "power_in"))
      (node (ref "U$101") (pin "90") (pinfunction "GND_44_90") (pintype "power_in"))
      (node (ref "U$101") (pin "91") (pinfunction "45_GND_91") (pintype "power_in"))
      (node (ref "U$101") (pin "92") (pinfunction "GND_46_92") (pintype "power_in"))
      (node (ref "U$101") (pin "93") (pinfunction "GND_93") (pintype "bidirectional"))
      (node (ref "U$101") (pin "P$1") (pinfunction "SCREW$1_P$1") (pintype "bidirectional"))
      (node (ref "U$101") (pin "P$2") (pinfunction "SCREW$2_P$2") (pintype "bidirectional"))
      (node (ref "U$101") (pin "P$3") (pinfunction "SCREW$3_P$3") (pintype "bidirectional"))
      (node (ref "U$101") (pin "P$4") (pinfunction "SCREW$4_P$4") (pintype "bidirectional"))
      (node (ref "U$101") (pin "TP8") (pinfunction "BATT_GND_TP8") (pintype "bidirectional"))
      (node (ref "U$11") (pin "2") (pinfunction "2_2") (pintype "passive"))
      (node (ref "U$11") (pin "P$3") (pinfunction "P$1_P$3") (pintype "bidirectional"))
      (node (ref "U$11") (pin "P$4") (pinfunction "P$2_P$4") (pintype "bidirectional"))
      (node (ref "U$12") (pin "P$4") (pinfunction "P$1_P$4") (pintype "bidirectional"))
      (node (ref "U$12") (pin "P$5") (pinfunction "P$2_P$5") (pintype "bidirectional"))
      (node (ref "U$2") (pin "6") (pinfunction "6_6") (pintype "passive"))
      (node (ref "U$2") (pin "P$7") (pinfunction "P$1_P$7") (pintype "bidirectional"))
      (node (ref "U$2") (pin "P$8") (pinfunction "P$2_P$8") (pintype "bidirectional"))
      (node (ref "U$201") (pin "6") (pinfunction "6_6") (pintype "passive"))
      (node (ref "U$201") (pin "P$7") (pinfunction "P$1_P$7") (pintype "bidirectional"))
      (node (ref "U$201") (pin "P$8") (pinfunction "P$2_P$8") (pintype "bidirectional"))
      (node (ref "U$4") (pin "6") (pinfunction "6_6") (pintype "passive"))
      (node (ref "U$4") (pin "P$7") (pinfunction "P$1_P$7") (pintype "bidirectional"))
      (node (ref "U$4") (pin "P$8") (pinfunction "P$2_P$8") (pintype "bidirectional"))
      (node (ref "U1") (pin "1") (pinfunction "A0_1") (pintype "bidirectional"))
      (node (ref "U1") (pin "2") (pinfunction "A1_2") (pintype "bidirectional"))
      (node (ref "U1") (pin "4") (pinfunction "VSS_4") (pintype "power_in"))
      (node (ref "U102") (pin "4") (pinfunction "VSS_4") (pintype "bidirectional"))
      (node (ref "U2") (pin "4") (pinfunction "VSS_4") (pintype "power_in"))
      (node (ref "U201") (pin "11") (pinfunction "GND_11") (pintype "power_in"))
      (node (ref "U301") (pin "2") (pinfunction "GND_2") (pintype "power_in"))
      (node (ref "U301") (pin "5") (pinfunction "SHDN_5") (pintype "input"))
      (node (ref "U302") (pin "11") (pinfunction "GND_11") (pintype "power_in"))
      (node (ref "U303") (pin "1") (pinfunction "GND_1") (pintype "bidirectional"))
      (node (ref "U401") (pin "2") (pinfunction "PS_2") (pintype "bidirectional"))
      (node (ref "U401") (pin "3") (pinfunction "GND_3") (pintype "bidirectional"))
      (node (ref "U403") (pin "1") (pinfunction "CLKIN_1") (pintype "bidirectional"))
      (node (ref "U403") (pin "11") (pinfunction "FSYNC_11") (pintype "bidirectional"))
      (node (ref "U403") (pin "18") (pinfunction "GND_18") (pintype "bidirectional"))
      (node (ref "U405") (pin "11") (pinfunction "FSYNC_11") (pintype "bidirectional"))
      (node (ref "U405") (pin "18") (pinfunction "GND_18") (pintype "bidirectional"))
      (node (ref "U405") (pin "20") (pinfunction "RESV_20") (pintype "bidirectional"))
      (node (ref "U406") (pin "2") (pinfunction "GND_2") (pintype "bidirectional"))
      (node (ref "U406") (pin "3") (pinfunction "GND_3") (pintype "bidirectional"))
      (node (ref "U406") (pin "4") (pinfunction "GND_4") (pintype "bidirectional"))
      (node (ref "U406") (pin "5") (pinfunction "GND_5") (pintype "bidirectional"))
      (node (ref "U406") (pin "6") (pinfunction "GND_6") (pintype "bidirectional"))
      (node (ref "U501") (pin "2") (pinfunction "VSS_2") (pintype "bidirectional"))
      (node (ref "U501") (pin "6") (pinfunction "VBAT_6") (pintype "bidirectional"))
      (node (ref "U501") (pin "GND") (pinfunction "VSS_GND") (pintype "bidirectional"))
      (node (ref "U501") (pin "P$2") (pinfunction "VSS_P$2") (pintype "bidirectional"))
      (node (ref "U501") (pin "P$3") (pinfunction "VSS_P$3") (pintype "bidirectional"))
      (node (ref "U502") (pin "2") (pinfunction "GND_2") (pintype "bidirectional"))
      (node (ref "U502") (pin "GND") (pinfunction "GND_GND") (pintype "bidirectional"))
      (node (ref "U503") (pin "2") (pinfunction "VSS_2") (pintype "bidirectional"))
      (node (ref "U503") (pin "6") (pinfunction "VBAT_6") (pintype "bidirectional"))
      (node (ref "U503") (pin "GND") (pinfunction "VSS_GND") (pintype "bidirectional"))
      (node (ref "U503") (pin "P$2") (pinfunction "VSS_P$2") (pintype "bidirectional"))
      (node (ref "U503") (pin "P$3") (pinfunction "VSS_P$3") (pintype "bidirectional"))
      (node (ref "U602") (pin "4") (pinfunction "GND_4") (pintype "power_in"))
      (node (ref "U701") (pin "11") (pinfunction "GND_11") (pintype "power_in"))
      (node (ref "U702") (pin "11") (pinfunction "GND_11") (pintype "power_in"))
      (node (ref "U704") (pin "12") (pinfunction "GND_12") (pintype "bidirectional"))
      (node (ref "U704") (pin "15") (pinfunction "GND_15") (pintype "bidirectional"))
      (node (ref "U704") (pin "18") (pinfunction "GND_18") (pintype "bidirectional"))
      (node (ref "U704") (pin "21") (pinfunction "GND_21") (pintype "bidirectional"))
      (node (ref "U704") (pin "24") (pinfunction "GND_24") (pintype "bidirectional"))
      (node (ref "U704") (pin "27") (pinfunction "GND_27") (pintype "bidirectional"))
      (node (ref "U704") (pin "3") (pinfunction "GND_3") (pintype "bidirectional"))
      (node (ref "U704") (pin "30") (pinfunction "GND_30") (pintype "bidirectional"))
      (node (ref "U704") (pin "33") (pinfunction "GND_33") (pintype "bidirectional"))
      (node (ref "U704") (pin "36") (pinfunction "GND_36") (pintype "bidirectional"))
      (node (ref "U704") (pin "39") (pinfunction "GND_39") (pintype "bidirectional"))
      (node (ref "U704") (pin "42") (pinfunction "GND_42") (pintype "bidirectional"))
      (node (ref "U704") (pin "6") (pinfunction "GND_6") (pintype "bidirectional"))
      (node (ref "U704") (pin "9") (pinfunction "GND_9") (pintype "bidirectional"))
      (node (ref "U802") (pin "2") (pinfunction "GND_2") (pintype "bidirectional"))
      (node (ref "U802") (pin "4") (pinfunction "EN2_4") (pintype "bidirectional"))
      (node (ref "U802") (pin "GND") (pinfunction "GND_GND") (pintype "bidirectional"))
      (node (ref "X801") (pin "4") (pinfunction "S_4") (pintype "passive"))
    )
    (net (code "42") (name "GYRO_DRDY") (class "Default")
      (node (ref "U$101") (pin "34") (pinfunction "GPOI2[17]_34_34") (pintype "passive"))
      (node (ref "U406") (pin "12") (pinfunction "DRDY_G_12") (pintype "bidirectional"))
    )
    (net (code "43") (name "I2C2_SCL") (class "Default")
      (node (ref "R301") (pin "P$1") (pinfunction "1_P$1") (pintype "passive"))
      (node (ref "U$101") (pin "65") (pinfunction "19_I2C2_SCL_65") (pintype "passive"))
      (node (ref "U1") (pin "6") (pinfunction "SCL_6") (pintype "bidirectional"))
      (node (ref "U2") (pin "6") (pinfunction "SCL_6") (pintype "bidirectional"))
      (node (ref "U303") (pin "3") (pinfunction "SCL1_3") (pintype "bidirectional"))
    )
    (net (code "44") (name "I2C2_SDA") (class "Default")
      (node (ref "R302") (pin "P$1") (pinfunction "1_P$1") (pintype "passive"))
      (node (ref "U$101") (pin "66") (pinfunction "I2C2_SDA_20_66") (pintype "passive"))
      (node (ref "U1") (pin "5") (pinfunction "SDA_5") (pintype "bidirectional"))
      (node (ref "U2") (pin "5") (pinfunction "SDA_5") (pintype "bidirectional"))
      (node (ref "U303") (pin "4") (pinfunction "SDA1_4") (pintype "bidirectional"))
    )
    (net (code "45") (name "MAG_DRDY") (class "Default")
      (node (ref "U$101") (pin "10") (pinfunction "GPIO2[4]_10_10") (pintype "passive"))
      (node (ref "U406") (pin "13") (pinfunction "INT1_XM_13") (pintype "bidirectional"))
    )
    (net (code "46") (name "MPU_6000_DRDY") (class "Default")
      (node (ref "U$101") (pin "14") (pinfunction "GPIO0[26]_14_14") (pintype "passive"))
      (node (ref "U403") (pin "12") (pinfunction "INT_12") (pintype "bidirectional"))
    )
    (net (code "47") (name "MPU_6500_DRDY") (class "Default")
      (node (ref "U$101") (pin "7") (pinfunction "7_GPIO2[2]_7") (pintype "passive"))
      (node (ref "U405") (pin "12") (pinfunction "INT_12") (pintype "bidirectional"))
    )
    (net (code "48") (name "Net-(C402-1)") (class "Default")
      (node (ref "C402") (pin "P$1") (pinfunction "1_P$1") (pintype "passive"))
      (node (ref "U406") (pin "7") (pinfunction "C1_XM_7") (pintype "bidirectional"))
    )
    (net (code "49") (name "Net-(C403-1)") (class "Default")
      (node (ref "C403") (pin "P$1") (pinfunction "1_P$1") (pintype "passive"))
      (node (ref "U406") (pin "8") (pinfunction "SETC_XM_8") (pintype "bidirectional"))
    )
    (net (code "50") (name "Net-(C403-2)") (class "Default")
      (node (ref "C403") (pin "P$2") (pinfunction "2_P$2") (pintype "passive"))
      (node (ref "U406") (pin "9") (pinfunction "SETP_XM_9") (pintype "bidirectional"))
    )
    (net (code "51") (name "Net-(C409-1)") (class "Default")
      (node (ref "C409") (pin "P$1") (pinfunction "1_P$1") (pintype "passive"))
      (node (ref "U403") (pin "10") (pinfunction "REGOUT_10") (pintype "bidirectional"))
    )
    (net (code "52") (name "Net-(C411-1)") (class "Default")
      (node (ref "C411") (pin "P$1") (pinfunction "1_P$1") (pintype "passive"))
      (node (ref "U405") (pin "10") (pinfunction "REGOUT_10") (pintype "bidirectional"))
    )
    (net (code "53") (name "Net-(C416-1)") (class "Default")
      (node (ref "C416") (pin "P$1") (pinfunction "1_P$1") (pintype "passive"))
      (node (ref "U403") (pin "20") (pinfunction "CPOUT_20") (pintype "bidirectional"))
    )
    (net (code "54") (name "Net-(C501-1)") (class "Default")
      (node (ref "C501") (pin "P$1") (pinfunction "1_P$1") (pintype "passive"))
      (node (ref "C502") (pin "P$1") (pinfunction "1_P$1") (pintype "passive"))
      (node (ref "L501") (pin "P$2") (pinfunction "P$2_P$2") (pintype "bidirectional"))
      (node (ref "U502") (pin "1") (pinfunction "VIN_1") (pintype "bidirectional"))
    )
    (net (code "55") (name "Net-(C503-1)") (class "Default")
      (node (ref "C503") (pin "P$1") (pinfunction "1_P$1") (pintype "passive"))
      (node (ref "U502") (pin "6") (pinfunction "CSET_6") (pintype "bidirectional"))
    )
    (net (code "56") (name "Net-(C603-1)") (class "Default")
      (node (ref "C603") (pin "P$1") (pinfunction "1_P$1") (pintype "passive"))
      (node (ref "R604") (pin "P$1") (pinfunction "1_P$1") (pintype "passive"))
      (node (ref "U$11") (pin "1") (pinfunction "1_1") (pintype "passive"))
      (node (ref "U602") (pin "1") (pinfunction "OUT_1") (pintype "output"))
    )
    (net (code "57") (name "Net-(C604-1)") (class "Default")
      (node (ref "C604") (pin "P$1") (pinfunction "1_P$1") (pintype "passive"))
      (node (ref "R606") (pin "P$1") (pinfunction "1_P$1") (pintype "passive"))
      (node (ref "R614") (pin "P$1") (pinfunction "1_P$1") (pintype "passive"))
      (node (ref "U602") (pin "6") (pinfunction "VCC_6") (pintype "bidirectional"))
    )
    (net (code "58") (name "Net-(D201-PadC)") (class "Default")
      (node (ref "D201") (pin "C") (pinfunction "C_C") (pintype "passive"))
      (node (ref "L201") (pin "P$2") (pinfunction "P$2_P$2") (pintype "bidirectional"))
      (node (ref "U$201") (pin "1") (pinfunction "1_1") (pintype "passive"))
    )
    (net (code "59") (name "Net-(D202-PadC)") (class "Default")
      (node (ref "D202") (pin "C") (pinfunction "C_C") (pintype "passive"))
      (node (ref "L202") (pin "P$2") (pinfunction "P$2_P$2") (pintype "bidirectional"))
      (node (ref "U$2") (pin "1") (pinfunction "1_1") (pintype "passive"))
    )
    (net (code "60") (name "Net-(D203-PadC)") (class "Default")
      (node (ref "D203") (pin "C") (pinfunction "C_C") (pintype "passive"))
      (node (ref "L203") (pin "P$2") (pinfunction "P$2_P$2") (pintype "bidirectional"))
      (node (ref "U$4") (pin "1") (pinfunction "1_1") (pintype "passive"))
    )
    (net (code "61") (name "Net-(D301-PadC)") (class "Default")
      (node (ref "D301") (pin "C") (pinfunction "C_C") (pintype "passive"))
      (node (ref "J305") (pin "1") (pinfunction "1_1") (pintype "passive"))
      (node (ref "J306") (pin "1") (pinfunction "1_1") (pintype "passive"))
      (node (ref "J310") (pin "1") (pinfunction "1_1") (pintype "passive"))
      (node (ref "J314") (pin "1") (pinfunction "1_1") (pintype "passive"))
      (node (ref "L301") (pin "P$2") (pinfunction "P$2_P$2") (pintype "bidirectional"))
    )
    (net (code "62") (name "Net-(D302-PadC)") (class "Default")
      (node (ref "D302") (pin "C") (pinfunction "C_C") (pintype "passive"))
      (node (ref "J309") (pin "1") (pinfunction "1_1") (pintype "passive"))
      (node (ref "L302") (pin "P$2") (pinfunction "P$2_P$2") (pintype "bidirectional"))
    )
    (net (code "63") (name "Net-(D303-PadC)") (class "Default")
      (node (ref "D303") (pin "C") (pinfunction "C_C") (pintype "passive"))
      (node (ref "J307") (pin "1") (pinfunction "1_1") (pintype "passive"))
      (node (ref "L303") (pin "P$2") (pinfunction "P$2_P$2") (pintype "bidirectional"))
    )
    (net (code "64") (name "Net-(D704-A)") (class "Default")
      (node (ref "D704") (pin "ANODE") (pinfunction "A_ANODE") (pintype "passive"))
      (node (ref "D705") (pin "ANODE") (pinfunction "A_ANODE") (pintype "passive"))
      (node (ref "R3") (pin "P$2") (pinfunction "2_P$2") (pintype "passive"))
      (node (ref "U704") (pin "11") (pinfunction "5V_11") (pintype "bidirectional"))
      (node (ref "U704") (pin "14") (pinfunction "5V_14") (pintype "bidirectional"))
      (node (ref "U704") (pin "17") (pinfunction "5V_17") (pintype "bidirectional"))
      (node (ref "U704") (pin "2") (pinfunction "5V_2") (pintype "bidirectional"))
      (node (ref "U704") (pin "20") (pinfunction "5V_20") (pintype "bidirectional"))
      (node (ref "U704") (pin "23") (pinfunction "5V_23") (pintype "bidirectional"))
      (node (ref "U704") (pin "26") (pinfunction "5V_26") (pintype "bidirectional"))
      (node (ref "U704") (pin "29") (pinfunction "5V_29") (pintype "bidirectional"))
      (node (ref "U704") (pin "32") (pinfunction "5V_32") (pintype "bidirectional"))
      (node (ref "U704") (pin "35") (pinfunction "5V_35") (pintype "bidirectional"))
      (node (ref "U704") (pin "38") (pinfunction "5V_38") (pintype "bidirectional"))
      (node (ref "U704") (pin "5") (pinfunction "5V_5") (pintype "bidirectional"))
      (node (ref "U704") (pin "8") (pinfunction "5V_8") (pintype "bidirectional"))
    )
    (net (code "65") (name "Net-(D704-C)") (class "Default")
      (node (ref "D704") (pin "CATHODE") (pinfunction "C_CATHODE") (pintype "passive"))
      (node (ref "D705") (pin "CATHODE") (pinfunction "C_CATHODE") (pintype "passive"))
      (node (ref "D706") (pin "C") (pinfunction "C_C") (pintype "passive"))
      (node (ref "L701") (pin "P$1") (pinfunction "P$1_P$1") (pintype "bidirectional"))
    )
    (net (code "66") (name "Net-(F701-Pad2)") (class "Default")
      (node (ref "F701") (pin "2") (pinfunction "2_2") (pintype "bidirectional"))
      (node (ref "U704") (pin "41") (pinfunction "5V_41") (pintype "bidirectional"))
    )
    (net (code "67") (name "Net-(L601-2)") (class "Default")
      (node (ref "L601") (pin "P$2") (pinfunction "2_P$2") (pintype "passive"))
      (node (ref "U602") (pin "5") (pinfunction "SW_5") (pintype "passive"))
    )
    (net (code "68") (name "Net-(Q501-PadC)") (class "Default")
      (node (ref "Q501") (pin "C") (pinfunction "C_C") (pintype "passive"))
      (node (ref "R505") (pin "2") (pinfunction "2_2") (pintype "passive"))
    )
    (net (code "69") (name "Net-(R1-2)") (class "Default")
      (node (ref "R1") (pin "P$2") (pinfunction "2_P$2") (pintype "passive"))
      (node (ref "R804") (pin "P$1") (pinfunction "1_P$1") (pintype "passive"))
    )
    (net (code "70") (name "Net-(R2-2)") (class "Default")
      (node (ref "R2") (pin "P$2") (pinfunction "2_P$2") (pintype "passive"))
      (node (ref "R805") (pin "P$1") (pinfunction "1_P$1") (pintype "passive"))
    )
    (net (code "71") (name "Net-(R4-2)") (class "Default")
      (node (ref "R4") (pin "P$2") (pinfunction "2_P$2") (pintype "passive"))
      (node (ref "R508") (pin "P$1") (pinfunction "1_P$1") (pintype "passive"))
    )
    (net (code "72") (name "Net-(R8-2)") (class "Default")
      (node (ref "R8") (pin "P$2") (pinfunction "2_P$2") (pintype "passive"))
      (node (ref "R9") (pin "P$1") (pinfunction "1_P$1") (pintype "passive"))
    )
    (net (code "73") (name "Net-(R103-1)") (class "Default")
      (node (ref "R103") (pin "P$1") (pinfunction "1_P$1") (pintype "passive"))
      (node (ref "U1") (pin "3") (pinfunction "A2_3") (pintype "bidirectional"))
    )
    (net (code "74") (name "Net-(R201-1)") (class "Default")
      (node (ref "R201") (pin "P$1") (pinfunction "1_P$1") (pintype "passive"))
      (node (ref "U201") (pin "20") (pinfunction "B1_20") (pintype "bidirectional"))
    )
    (net (code "75") (name "Net-(R202-1)") (class "Default")
      (node (ref "R202") (pin "P$1") (pinfunction "1_P$1") (pintype "passive"))
      (node (ref "U201") (pin "17") (pinfunction "B3_17") (pintype "bidirectional"))
    )
    (net (code "76") (name "Net-(R203-1)") (class "Default")
      (node (ref "R203") (pin "P$1") (pinfunction "1_P$1") (pintype "passive"))
      (node (ref "U201") (pin "15") (pinfunction "B5_15") (pintype "bidirectional"))
    )
    (net (code "77") (name "Net-(R204-1)") (class "Default")
      (node (ref "R204") (pin "P$1") (pinfunction "1_P$1") (pintype "passive"))
      (node (ref "U201") (pin "13") (pinfunction "B7_13") (pintype "bidirectional"))
    )
    (net (code "78") (name "Net-(R208-1)") (class "Default")
      (node (ref "R208") (pin "P$1") (pinfunction "1_P$1") (pintype "passive"))
      (node (ref "U201") (pin "18") (pinfunction "B2_18") (pintype "bidirectional"))
    )
    (net (code "79") (name "Net-(R209-1)") (class "Default")
      (node (ref "R209") (pin "P$1") (pinfunction "1_P$1") (pintype "passive"))
      (node (ref "U201") (pin "16") (pinfunction "B4_16") (pintype "bidirectional"))
    )
    (net (code "80") (name "Net-(R210-1)") (class "Default")
      (node (ref "R210") (pin "P$1") (pinfunction "1_P$1") (pintype "passive"))
      (node (ref "U201") (pin "14") (pinfunction "B6_14") (pintype "bidirectional"))
    )
    (net (code "81") (name "Net-(R211-1)") (class "Default")
      (node (ref "R211") (pin "P$1") (pinfunction "1_P$1") (pintype "passive"))
      (node (ref "U201") (pin "12") (pinfunction "B8_12") (pintype "bidirectional"))
    )
    (net (code "82") (name "Net-(R304-2)") (class "Default")
      (node (ref "J306") (pin "3") (pinfunction "3_3") (pintype "passive"))
      (node (ref "J310") (pin "3") (pinfunction "3_3") (pintype "passive"))
      (node (ref "J314") (pin "3") (pinfunction "3_3") (pintype "passive"))
      (node (ref "R304") (pin "P$2") (pinfunction "2_P$2") (pintype "passive"))
      (node (ref "U303") (pin "5") (pinfunction "SDA2_5") (pintype "bidirectional"))
    )
    (net (code "83") (name "Net-(R305-2)") (class "Default")
      (node (ref "J306") (pin "2") (pinfunction "2_2") (pintype "passive"))
      (node (ref "J310") (pin "2") (pinfunction "2_2") (pintype "passive"))
      (node (ref "J314") (pin "2") (pinfunction "2_2") (pintype "passive"))
      (node (ref "R305") (pin "P$2") (pinfunction "2_P$2") (pintype "passive"))
      (node (ref "U303") (pin "6") (pinfunction "SCL2_6") (pintype "bidirectional"))
    )
    (net (code "84") (name "Net-(R306-2)") (class "Default")
      (node (ref "R306") (pin "P$2") (pinfunction "2_P$2") (pintype "passive"))
      (node (ref "R7") (pin "P$1") (pinfunction "1_P$1") (pintype "passive"))
    )
    (net (code "85") (name "Net-(R307-2)") (class "Default")
      (node (ref "R307") (pin "P$2") (pinfunction "2_P$2") (pintype "passive"))
      (node (ref "R5") (pin "P$1") (pinfunction "1_P$1") (pintype "passive"))
    )
    (net (code "86") (name "Net-(R308-2)") (class "Default")
      (node (ref "R308") (pin "P$2") (pinfunction "2_P$2") (pintype "passive"))
      (node (ref "R6") (pin "P$1") (pinfunction "1_P$1") (pintype "passive"))
    )
    (net (code "87") (name "Net-(R310-2)") (class "Default")
      (node (ref "J309") (pin "2") (pinfunction "2_2") (pintype "passive"))
      (node (ref "R310") (pin "P$2") (pinfunction "2_P$2") (pintype "passive"))
      (node (ref "R5") (pin "P$2") (pinfunction "2_P$2") (pintype "passive"))
    )
    (net (code "88") (name "Net-(R311-2)") (class "Default")
      (node (ref "J309") (pin "4") (pinfunction "4_4") (pintype "passive"))
      (node (ref "R311") (pin "P$2") (pinfunction "2_P$2") (pintype "passive"))
      (node (ref "R6") (pin "P$2") (pinfunction "2_P$2") (pintype "passive"))
    )
    (net (code "89") (name "Net-(R312-1)") (class "Default")
      (node (ref "R312") (pin "P$1") (pinfunction "1_P$1") (pintype "passive"))
      (node (ref "U302") (pin "18") (pinfunction "B2_18") (pintype "bidirectional"))
    )
    (net (code "90") (name "Net-(R312-2)") (class "Default")
      (node (ref "J308") (pin "3") (pinfunction "3_3") (pintype "passive"))
      (node (ref "R312") (pin "P$2") (pinfunction "2_P$2") (pintype "passive"))
    )
    (net (code "91") (name "Net-(R313-1)") (class "Default")
      (node (ref "R313") (pin "P$1") (pinfunction "1_P$1") (pintype "passive"))
      (node (ref "U302") (pin "20") (pinfunction "B1_20") (pintype "bidirectional"))
    )
    (net (code "92") (name "Net-(R313-2)") (class "Default")
      (node (ref "J308") (pin "2") (pinfunction "2_2") (pintype "passive"))
      (node (ref "R313") (pin "P$2") (pinfunction "2_P$2") (pintype "passive"))
    )
    (net (code "93") (name "Net-(R315-1)") (class "Default")
      (node (ref "R315") (pin "P$1") (pinfunction "1_P$1") (pintype "passive"))
      (node (ref "U301") (pin "8") (pinfunction "RS_8") (pintype "input"))
    )
    (net (code "94") (name "Net-(R501-1)") (class "Default")
      (node (ref "R501") (pin "P$1") (pinfunction "1_P$1") (pintype "passive"))
      (node (ref "U501") (pin "7") (pinfunction "ILIM_7") (pintype "bidirectional"))
    )
    (net (code "95") (name "Net-(R503-1)") (class "Default")
      (node (ref "Q501") (pin "B") (pinfunction "B_B") (pintype "passive"))
      (node (ref "R503") (pin "P$1") (pinfunction "1_P$1") (pintype "passive"))
    )
    (net (code "96") (name "Net-(R504-1)") (class "Default")
      (node (ref "R504") (pin "P$1") (pinfunction "1_P$1") (pintype "passive"))
      (node (ref "U503") (pin "7") (pinfunction "ILIM_7") (pintype "bidirectional"))
    )
    (net (code "97") (name "Net-(R602-1)") (class "Default")
      (node (ref "R602") (pin "P$1") (pinfunction "1_P$1") (pintype "passive"))
      (node (ref "U602") (pin "7") (pinfunction "+IN_7") (pintype "input"))
    )
    (net (code "98") (name "Net-(R603-1)") (class "Default")
      (node (ref "R603") (pin "P$1") (pinfunction "1_P$1") (pintype "passive"))
      (node (ref "R604") (pin "P$2") (pinfunction "2_P$2") (pintype "passive"))
      (node (ref "U602") (pin "8") (pinfunction "-IN_8") (pintype "input"))
    )
    (net (code "99") (name "Net-(R606-2)") (class "Default")
      (node (ref "JP600") (pin "2") (pinfunction "2_2") (pintype "passive"))
      (node (ref "R606") (pin "P$2") (pinfunction "2_P$2") (pintype "passive"))
      (node (ref "R607") (pin "P$1") (pinfunction "1_P$1") (pintype "passive"))
      (node (ref "U602") (pin "2") (pinfunction "FB_2") (pintype "bidirectional"))
    )
    (net (code "100") (name "Net-(R608-2)") (class "Default")
      (node (ref "LED601") (pin "C") (pinfunction "C_C") (pintype "passive"))
      (node (ref "R608") (pin "P$2") (pinfunction "2_P$2") (pintype "passive"))
    )
    (net (code "101") (name "Net-(R609-1)") (class "Default")
      (node (ref "R609") (pin "P$1") (pinfunction "1_P$1") (pintype "passive"))
      (node (ref "R610") (pin "P$2") (pinfunction "2_P$2") (pintype "passive"))
    )
    (net (code "102") (name "Net-(R609-2)") (class "Default")
      (node (ref "LED602") (pin "C") (pinfunction "C_C") (pintype "passive"))
      (node (ref "R609") (pin "P$2") (pinfunction "2_P$2") (pintype "passive"))
    )
    (net (code "103") (name "Net-(R611-1)") (class "Default")
      (node (ref "R611") (pin "P$1") (pinfunction "1_P$1") (pintype "passive"))
      (node (ref "U$12") (pin "2") (pinfunction "2_2") (pintype "passive"))
    )
    (net (code "104") (name "Net-(R612-2)") (class "Default")
      (node (ref "LED603") (pin "C") (pinfunction "C_C") (pintype "passive"))
      (node (ref "R612") (pin "P$2") (pinfunction "2_P$2") (pintype "passive"))
    )
    (net (code "105") (name "Net-(R614-2)") (class "Default")
      (node (ref "JP600") (pin "1") (pinfunction "1_1") (pintype "passive"))
      (node (ref "R614") (pin "P$2") (pinfunction "2_P$2") (pintype "passive"))
    )
    (net (code "106") (name "Net-(R701-2)") (class "Default")
      (node (ref "R701") (pin "P$2") (pinfunction "2_P$2") (pintype "passive"))
      (node (ref "U704") (pin "10") (pinfunction "CH4_10") (pintype "bidirectional"))
    )
    (net (code "107") (name "Net-(R702-2)") (class "Default")
      (node (ref "R702") (pin "P$2") (pinfunction "2_P$2") (pintype "passive"))
      (node (ref "U704") (pin "13") (pinfunction "CH5_13") (pintype "bidirectional"))
    )
    (net (code "108") (name "Net-(R703-2)") (class "Default")
      (node (ref "R703") (pin "P$2") (pinfunction "2_P$2") (pintype "passive"))
      (node (ref "U704") (pin "16") (pinfunction "CH6_16") (pintype "bidirectional"))
    )
    (net (code "109") (name "Net-(R704-2)") (class "Default")
      (node (ref "R704") (pin "P$2") (pinfunction "2_P$2") (pintype "passive"))
      (node (ref "U704") (pin "19") (pinfunction "CH7_19") (pintype "bidirectional"))
    )
    (net (code "110") (name "Net-(R705-2)") (class "Default")
      (node (ref "R705") (pin "P$2") (pinfunction "2_P$2") (pintype "passive"))
      (node (ref "U704") (pin "22") (pinfunction "CH8_22") (pintype "bidirectional"))
    )
    (net (code "111") (name "Net-(R706-2)") (class "Default")
      (node (ref "R706") (pin "P$2") (pinfunction "2_P$2") (pintype "passive"))
      (node (ref "U704") (pin "25") (pinfunction "CH9_25") (pintype "bidirectional"))
    )
    (net (code "112") (name "Net-(R707-2)") (class "Default")
      (node (ref "R707") (pin "P$2") (pinfunction "2_P$2") (pintype "passive"))
      (node (ref "U704") (pin "28") (pinfunction "CH10_28") (pintype "bidirectional"))
    )
    (net (code "113") (name "Net-(R708-2)") (class "Default")
      (node (ref "R708") (pin "P$2") (pinfunction "2_P$2") (pintype "passive"))
      (node (ref "U704") (pin "31") (pinfunction "CH11_31") (pintype "bidirectional"))
    )
    (net (code "114") (name "Net-(R709-2)") (class "Default")
      (node (ref "R709") (pin "P$2") (pinfunction "2_P$2") (pintype "passive"))
      (node (ref "U704") (pin "34") (pinfunction "CH12_34") (pintype "bidirectional"))
    )
    (net (code "115") (name "Net-(R710-2)") (class "Default")
      (node (ref "R710") (pin "P$2") (pinfunction "2_P$2") (pintype "passive"))
      (node (ref "U704") (pin "37") (pinfunction "PPM/S.BUS_OUT_37") (pintype "bidirectional"))
    )
    (net (code "116") (name "Net-(R711-2)") (class "Default")
      (node (ref "R711") (pin "P$2") (pinfunction "2_P$2") (pintype "passive"))
      (node (ref "U704") (pin "40") (pinfunction "PPM/S.BUS_IN_40") (pintype "bidirectional"))
    )
    (net (code "117") (name "Net-(R712-2)") (class "Default")
      (node (ref "R712") (pin "P$2") (pinfunction "2_P$2") (pintype "passive"))
      (node (ref "U704") (pin "7") (pinfunction "CH3_7") (pintype "bidirectional"))
    )
    (net (code "118") (name "Net-(R713-2)") (class "Default")
      (node (ref "R713") (pin "P$2") (pinfunction "2_P$2") (pintype "passive"))
      (node (ref "U704") (pin "4") (pinfunction "CH2_4") (pintype "bidirectional"))
    )
    (net (code "119") (name "Net-(R714-2)") (class "Default")
      (node (ref "R714") (pin "P$2") (pinfunction "2_P$2") (pintype "passive"))
      (node (ref "U704") (pin "1") (pinfunction "CH1_1") (pintype "bidirectional"))
    )
    (net (code "120") (name "Net-(R801-1)") (class "Default")
      (node (ref "J801") (pin "4") (pinfunction "4_4") (pintype "passive"))
      (node (ref "L802") (pin "P$1") (pinfunction "P$1_P$1") (pintype "bidirectional"))
      (node (ref "R801") (pin "P$1") (pinfunction "1_P$1") (pintype "passive"))
    )
    (net (code "121") (name "Net-(R802-1)") (class "Default")
      (node (ref "J801") (pin "3") (pinfunction "3_3") (pintype "passive"))
      (node (ref "L801") (pin "P$1") (pinfunction "P$1_P$1") (pintype "bidirectional"))
      (node (ref "R802") (pin "P$1") (pinfunction "1_P$1") (pintype "passive"))
    )
    (net (code "122") (name "Net-(R804-2)") (class "Default")
      (node (ref "L801") (pin "P$2") (pinfunction "P$2_P$2") (pintype "bidirectional"))
      (node (ref "R804") (pin "P$2") (pinfunction "2_P$2") (pintype "passive"))
    )
    (net (code "123") (name "Net-(R805-2)") (class "Default")
      (node (ref "L802") (pin "P$2") (pinfunction "P$2_P$2") (pintype "bidirectional"))
      (node (ref "R805") (pin "P$2") (pinfunction "2_P$2") (pintype "passive"))
    )
    (net (code "124") (name "Net-(U302-VCCB)") (class "Default")
      (node (ref "J308") (pin "1") (pinfunction "1_1") (pintype "passive"))
      (node (ref "JP1") (pin "1") (pinfunction "1_1") (pintype "passive"))
      (node (ref "U302") (pin "19") (pinfunction "VCCB_19") (pintype "input"))
    )
    (net (code "125") (name "OUTPUT_EN") (class "Default")
      (node (ref "R806") (pin "P$2") (pinfunction "2_P$2") (pintype "passive"))
      (node (ref "R9") (pin "P$2") (pinfunction "2_P$2") (pintype "passive"))
      (node (ref "U201") (pin "10") (pinfunction "OE_10") (pintype "input"))
      (node (ref "U502") (pin "3") (pinfunction "POR2_3") (pintype "bidirectional"))
      (node (ref "U701") (pin "10") (pinfunction "OE_10") (pintype "input"))
      (node (ref "U702") (pin "10") (pinfunction "OE_10") (pintype "input"))
      (node (ref "U802") (pin "5") (pinfunction "EN1_5") (pintype "bidirectional"))
    )
    (net (code "126") (name "PPM{slash}S.BUS_INPUT") (class "Default")
      (node (ref "J701") (pin "P$3") (pinfunction "P$3_P$3") (pintype "bidirectional"))
      (node (ref "R711") (pin "P$1") (pinfunction "1_P$1") (pintype "passive"))
      (node (ref "U$101") (pin "15") (pinfunction "15_PRU0_R31[15]_15") (pintype "passive"))
    )
    (net (code "127") (name "PPM{slash}S.BUS_OUT") (class "Default")
      (node (ref "R710") (pin "P$1") (pinfunction "1_P$1") (pintype "passive"))
      (node (ref "U$101") (pin "11") (pinfunction "11_PRU0_R30[15]_11") (pintype "passive"))
    )
    (net (code "128") (name "PRESSURE_SENS") (class "Default")
      (node (ref "C301") (pin "P$1") (pinfunction "1_P$1") (pintype "passive"))
      (node (ref "R303") (pin "P$2") (pinfunction "2_P$2") (pintype "passive"))
      (node (ref "R306") (pin "P$1") (pinfunction "1_P$1") (pintype "passive"))
      (node (ref "U$101") (pin "86") (pinfunction "AIN1_40_86") (pintype "passive"))
    )
    (net (code "129") (name "PRESSURE_SENS_IN") (class "Default")
      (node (ref "ADC_PR") (pin "P$1") (pinfunction "P$1_P$1") (pintype "passive"))
      (node (ref "J305") (pin "2") (pinfunction "2_2") (pintype "passive"))
      (node (ref "R7") (pin "P$2") (pinfunction "2_P$2") (pintype "passive"))
    )
    (net (code "130") (name "SAFETY") (class "Default")
      (node (ref "R613") (pin "P$1") (pinfunction "1_P$1") (pintype "passive"))
      (node (ref "U$101") (pin "87") (pinfunction "41_PRU0_R30/31[6]_87") (pintype "input"))
      (node (ref "U$12") (pin "3") (pinfunction "3_3") (pintype "passive"))
    )
    (net (code "131") (name "SERVO_RAIL_IN_~{EN}") (class "Default")
      (node (ref "U$101") (pin "16") (pinfunction "PRU0_R31[14]_16_16") (pintype "passive"))
    )
    (net (code "132") (name "SPARE") (class "Default")
      (node (ref "U$101") (pin "17") (pinfunction "17_GPIO0[27]_17") (pintype "passive"))
    )
    (net (code "133") (name "SPI_0_MISO") (class "Default")
      (node (ref "U$101") (pin "64") (pinfunction "SPI_0_MISO_18_64") (pintype "passive"))
      (node (ref "U406") (pin "22") (pinfunction "SDO_G_22") (pintype "bidirectional"))
      (node (ref "U406") (pin "23") (pinfunction "SDO_XM_23") (pintype "bidirectional"))
    )
    (net (code "134") (name "SPI_0_MOSI") (class "Default")
      (node (ref "U$101") (pin "67") (pinfunction "21_SPI_0_MOSI_67") (pintype "passive"))
      (node (ref "U406") (pin "24") (pinfunction "SDA_24") (pintype "bidirectional"))
    )
    (net (code "135") (name "SPI_0_SCK") (class "Default")
      (node (ref "U$101") (pin "68") (pinfunction "SPI_0_SCLK_22_68") (pintype "passive"))
      (node (ref "U406") (pin "21") (pinfunction "SPC_21") (pintype "bidirectional"))
    )
    (net (code "136") (name "SPI_1_MISO") (class "Default")
      (node (ref "U$101") (pin "76") (pinfunction "SPI_1_MISO_30_76") (pintype "passive"))
      (node (ref "U102") (pin "2") (pinfunction "Q_2") (pintype "bidirectional"))
      (node (ref "U401") (pin "6") (pinfunction "SDO_6") (pintype "bidirectional"))
      (node (ref "U403") (pin "9") (pinfunction "AD0/SDO_9") (pintype "bidirectional"))
      (node (ref "U405") (pin "9") (pinfunction "AD0/SDO_9") (pintype "bidirectional"))
    )
    (net (code "137") (name "SPI_1_MOSI") (class "Default")
      (node (ref "U$101") (pin "75") (pinfunction "29_SPI_1_MOSI_75") (pintype "passive"))
      (node (ref "U102") (pin "5") (pinfunction "D_5") (pintype "bidirectional"))
      (node (ref "U401") (pin "7") (pinfunction "SDI/SDA_7") (pintype "bidirectional"))
      (node (ref "U403") (pin "24") (pinfunction "SDA/SDI_24") (pintype "bidirectional"))
      (node (ref "U405") (pin "24") (pinfunction "SDA/SDI_24") (pintype "bidirectional"))
    )
    (net (code "138") (name "SPI_1_SCK") (class "Default")
      (node (ref "U$101") (pin "77") (pinfunction "31_SPI_1_SCLK_77") (pintype "passive"))
      (node (ref "U102") (pin "6") (pinfunction "C_6") (pintype "bidirectional"))
      (node (ref "U401") (pin "8") (pinfunction "SCLK_8") (pintype "bidirectional"))
      (node (ref "U403") (pin "23") (pinfunction "SCL/SCLK_23") (pintype "bidirectional"))
      (node (ref "U405") (pin "23") (pinfunction "SCL/SCLK_23") (pintype "bidirectional"))
    )
    (net (code "139") (name "SPI_1_~{BARO_CS}") (class "Default")
      (node (ref "U$101") (pin "88") (pinfunction "SPI_1_CS1_42_88") (pintype "passive"))
      (node (ref "U401") (pin "5") (pinfunction "CSB2_5") (pintype "bidirectional"))
    )
    (net (code "140") (name "SPI_1_~{MPU_CS2}") (class "Default")
      (node (ref "U$101") (pin "69") (pinfunction "23_GPIO1[17]_69") (pintype "passive"))
      (node (ref "U405") (pin "22") (pinfunction "~{CS}_22") (pintype "bidirectional"))
    )
    (net (code "141") (name "SPI_1_~{MPU_CS}") (class "Default")
      (node (ref "U$101") (pin "74") (pinfunction "SPI_1_CS0_28_74") (pintype "passive"))
      (node (ref "U403") (pin "8") (pinfunction "/CS_8") (pintype "bidirectional"))
    )
    (net (code "142") (name "SYS_5V") (class "Default")
      (node (ref "F701") (pin "1") (pinfunction "1_1") (pintype "bidirectional"))
      (node (ref "L501") (pin "P$1") (pinfunction "P$1_P$1") (pintype "bidirectional"))
      (node (ref "R508") (pin "P$2") (pinfunction "2_P$2") (pintype "passive"))
      (node (ref "U$101") (pin "53") (pinfunction "7_SYS_5V_53") (pintype "power_in"))
      (node (ref "U$101") (pin "54") (pinfunction "SYS_5V_8_54") (pintype "passive"))
      (node (ref "U501") (pin "1") (pinfunction "IN_1") (pintype "bidirectional"))
      (node (ref "U503") (pin "1") (pinfunction "IN_1") (pintype "bidirectional"))
      (node (ref "U802") (pin "1") (pinfunction "VIN_1") (pintype "bidirectional"))
      (node (ref "VDD_5V_IN") (pin "P$1") (pinfunction "P$1_P$1") (pintype "passive"))
    )
    (net (code "143") (name "TTYO0_RX") (class "Default")
      (node (ref "R212") (pin "P$2") (pinfunction "2_P$2") (pintype "passive"))
      (node (ref "U$4") (pin "3") (pinfunction "3_3") (pintype "passive"))
    )
    (net (code "144") (name "TTYO0_TX") (class "Default")
      (node (ref "R205") (pin "P$2") (pinfunction "2_P$2") (pintype "passive"))
      (node (ref "U$4") (pin "2") (pinfunction "2_2") (pintype "passive"))
    )
    (net (code "145") (name "TTYO4_CTS") (class "Default")
      (node (ref "R211") (pin "P$2") (pinfunction "2_P$2") (pintype "passive"))
      (node (ref "U$201") (pin "4") (pinfunction "4_4") (pintype "passive"))
    )
    (net (code "146") (name "TTYO4_RTS") (class "Default")
      (node (ref "R204") (pin "P$2") (pinfunction "2_P$2") (pintype "passive"))
      (node (ref "U$201") (pin "5") (pinfunction "5_5") (pintype "passive"))
    )
    (net (code "147") (name "TTYO4_RX") (class "Default")
      (node (ref "R203") (pin "P$2") (pinfunction "2_P$2") (pintype "passive"))
      (node (ref "S1RX") (pin "P$1") (pinfunction "P$1_P$1") (pintype "passive"))
      (node (ref "U$201") (pin "3") (pinfunction "3_3") (pintype "passive"))
    )
    (net (code "148") (name "TTYO4_TX") (class "Default")
      (node (ref "R210") (pin "P$2") (pinfunction "2_P$2") (pintype "passive"))
      (node (ref "S1TX") (pin "P$1") (pinfunction "P$1_P$1") (pintype "passive"))
      (node (ref "U$201") (pin "2") (pinfunction "2_2") (pintype "passive"))
    )
    (net (code "149") (name "TTYO5_CTS") (class "Default")
      (node (ref "R208") (pin "P$2") (pinfunction "2_P$2") (pintype "passive"))
      (node (ref "U$2") (pin "4") (pinfunction "4_4") (pintype "passive"))
    )
    (net (code "150") (name "TTYO5_RTS") (class "Default")
      (node (ref "R201") (pin "P$2") (pinfunction "2_P$2") (pintype "passive"))
      (node (ref "U$2") (pin "5") (pinfunction "5_5") (pintype "passive"))
    )
    (net (code "151") (name "TTYO5_RX") (class "Default")
      (node (ref "R202") (pin "P$2") (pinfunction "2_P$2") (pintype "passive"))
      (node (ref "S2RX") (pin "P$1") (pinfunction "P$1_P$1") (pintype "passive"))
      (node (ref "U$2") (pin "3") (pinfunction "3_3") (pintype "passive"))
    )
    (net (code "152") (name "TTYO5_TX") (class "Default")
      (node (ref "R209") (pin "P$2") (pinfunction "2_P$2") (pintype "passive"))
      (node (ref "S2TX") (pin "P$1") (pinfunction "P$1_P$1") (pintype "passive"))
      (node (ref "U$2") (pin "2") (pinfunction "2_2") (pintype "passive"))
    )
    (net (code "153") (name "UART0_RX") (class "Default")
      (node (ref "R212") (pin "P$1") (pinfunction "1_P$1") (pintype "passive"))
      (node (ref "U$101") (pin "97") (pinfunction "UART0_RXD_97") (pintype "bidirectional"))
    )
    (net (code "154") (name "UART0_TX") (class "Default")
      (node (ref "R205") (pin "P$1") (pinfunction "1_P$1") (pintype "passive"))
      (node (ref "U$101") (pin "96") (pinfunction "UART0_TXD_96") (pintype "bidirectional"))
    )
    (net (code "155") (name "UBLED-SCL") (class "Default")
      (node (ref "U$101") (pin "60") (pinfunction "GPIO1[18]_14_60") (pintype "passive"))
      (node (ref "U302") (pin "3") (pinfunction "A2_3") (pintype "bidirectional"))
    )
    (net (code "156") (name "UBLED-SDA") (class "Default")
      (node (ref "U$101") (pin "62") (pinfunction "GPIO1[19]_16_62") (pintype "passive"))
      (node (ref "U302") (pin "1") (pinfunction "A1_1") (pintype "bidirectional"))
    )
    (net (code "157") (name "USART4_CTS") (class "Default")
      (node (ref "U$101") (pin "35") (pinfunction "35_UART4_CTSN_35") (pintype "passive"))
      (node (ref "U201") (pin "9") (pinfunction "A8_9") (pintype "bidirectional"))
    )
    (net (code "158") (name "USART4_RTS") (class "Default")
      (node (ref "U$101") (pin "33") (pinfunction "33_UART4_RTSN_33") (pintype "passive"))
      (node (ref "U201") (pin "8") (pinfunction "A7_8") (pintype "bidirectional"))
    )
    (net (code "159") (name "USART4_RX") (class "Default")
      (node (ref "U$101") (pin "57") (pinfunction "11_UART4_RXD_57") (pintype "passive"))
      (node (ref "U201") (pin "6") (pinfunction "A5_6") (pintype "bidirectional"))
    )
    (net (code "160") (name "USART4_TX") (class "Default")
      (node (ref "U$101") (pin "59") (pinfunction "13_UART4_TXD_59") (pintype "passive"))
      (node (ref "U201") (pin "7") (pinfunction "A6_7") (pintype "bidirectional"))
    )
    (net (code "161") (name "USART5_CTS") (class "Default")
      (node (ref "U$101") (pin "31") (pinfunction "31_UART5_CTSN_31") (pintype "passive"))
      (node (ref "U201") (pin "3") (pinfunction "A2_3") (pintype "bidirectional"))
    )
    (net (code "162") (name "USART5_RTS") (class "Default")
      (node (ref "U$101") (pin "32") (pinfunction "UART5_RTSN_32_32") (pintype "passive"))
      (node (ref "U201") (pin "1") (pinfunction "A1_1") (pintype "bidirectional"))
    )
    (net (code "163") (name "USART5_RX") (class "Default")
      (node (ref "U$101") (pin "38") (pinfunction "UART5_RXD_38_38") (pintype "passive"))
      (node (ref "U201") (pin "4") (pinfunction "A3_4") (pintype "bidirectional"))
    )
    (net (code "164") (name "USART5_TX") (class "Default")
      (node (ref "U$101") (pin "37") (pinfunction "37_UART5_TXD_37") (pintype "passive"))
      (node (ref "U201") (pin "5") (pinfunction "A4_5") (pintype "bidirectional"))
    )
    (net (code "165") (name "VDD_3V3_4") (class "Default")
      (node (ref "U$101") (pin "50") (pinfunction "VDD_3V3_4_50") (pintype "power_in"))
    )
    (net (code "166") (name "VDD_3V3_SENSORS") (class "Default")
      (node (ref "C101") (pin "P$1") (pinfunction "1_P$1") (pintype "passive"))
      (node (ref "C305") (pin "P$1") (pinfunction "1_P$1") (pintype "passive"))
      (node (ref "C401") (pin "P$1") (pinfunction "1_P$1") (pintype "passive"))
      (node (ref "C405") (pin "P$2") (pinfunction "2_P$2") (pintype "passive"))
      (node (ref "C406") (pin "P$2") (pinfunction "2_P$2") (pintype "passive"))
      (node (ref "C407") (pin "P$1") (pinfunction "1_P$1") (pintype "passive"))
      (node (ref "C408") (pin "P$1") (pinfunction "1_P$1") (pintype "passive"))
      (node (ref "C410") (pin "P$1") (pinfunction "1_P$1") (pintype "passive"))
      (node (ref "C412") (pin "P$1") (pinfunction "1_P$1") (pintype "passive"))
      (node (ref "C413") (pin "P$1") (pinfunction "1_P$1") (pintype "passive"))
      (node (ref "C414") (pin "P$1") (pinfunction "1_P$1") (pintype "passive"))
      (node (ref "C415") (pin "P$1") (pinfunction "1_P$1") (pintype "passive"))
      (node (ref "C508") (pin "P$1") (pinfunction "1_P$1") (pintype "passive"))
      (node (ref "C509") (pin "P$1") (pinfunction "1_P$1") (pintype "passive"))
      (node (ref "Q501") (pin "E") (pinfunction "E_E") (pintype "passive"))
      (node (ref "R103") (pin "P$2") (pinfunction "2_P$2") (pintype "passive"))
      (node (ref "U1") (pin "8") (pinfunction "VCC_8") (pintype "power_in"))
      (node (ref "U102") (pin "3") (pinfunction "~{W}_3") (pintype "bidirectional"))
      (node (ref "U102") (pin "7") (pinfunction "~{HOLD}_7") (pintype "bidirectional"))
      (node (ref "U102") (pin "8") (pinfunction "VDD_8") (pintype "bidirectional"))
      (node (ref "U2") (pin "8") (pinfunction "VCC_8") (pintype "power_in"))
      (node (ref "U401") (pin "1") (pinfunction "VDD_1") (pintype "bidirectional"))
      (node (ref "U403") (pin "13") (pinfunction "VDD_13") (pintype "bidirectional"))
      (node (ref "U405") (pin "1") (pinfunction "NC_1") (pintype "bidirectional"))
      (node (ref "U405") (pin "13") (pinfunction "VDD_13") (pintype "bidirectional"))
      (node (ref "U405") (pin "8") (pinfunction "VDDIO_8") (pintype "bidirectional"))
      (node (ref "U406") (pin "15") (pinfunction "VDD_15") (pintype "bidirectional"))
      (node (ref "U406") (pin "16") (pinfunction "VDD_16") (pintype "bidirectional"))
      (node (ref "U406") (pin "17") (pinfunction "VDD_17") (pintype "bidirectional"))
      (node (ref "U406") (pin "18") (pinfunction "VDD_IO_18") (pintype "bidirectional"))
      (node (ref "U502") (pin "8") (pinfunction "VOUT1_8") (pintype "bidirectional"))
      (node (ref "VDDA_3V901") (pin "P$1") (pinfunction "P$1_P$1") (pintype "passive"))
    )
    (net (code "167") (name "VDD_3V3_SPEKTRUM") (class "Default")
      (node (ref "C805") (pin "P$1") (pinfunction "1_P$1") (pintype "passive"))
      (node (ref "D703") (pin "C") (pinfunction "C_C") (pintype "passive"))
      (node (ref "J701") (pin "P$1") (pinfunction "P$1_P$1") (pintype "bidirectional"))
      (node (ref "U802") (pin "8") (pinfunction "VOUT1_8") (pintype "bidirectional"))
    )
    (net (code "168") (name "VDD_5V") (class "Default")
      (node (ref "C801") (pin "P$1") (pinfunction "1_P$1") (pintype "passive"))
      (node (ref "J801") (pin "1") (pinfunction "1_1") (pintype "passive"))
      (node (ref "J801") (pin "2") (pinfunction "2_2") (pintype "passive"))
      (node (ref "U$101") (pin "51") (pinfunction "5_VDD_5V_51") (pintype "power_in"))
      (node (ref "U$101") (pin "52") (pinfunction "VDD_5V_6_52") (pintype "power_in"))
      (node (ref "VDD_5V_BRICK") (pin "P$1") (pinfunction "P$1_P$1") (pintype "passive"))
    )
    (net (code "169") (name "VDD_5V_HIPOWER") (class "Default")
      (node (ref "C504") (pin "P$1") (pinfunction "1_P$1") (pintype "passive"))
      (node (ref "L201") (pin "P$1") (pinfunction "P$1_P$1") (pintype "bidirectional"))
      (node (ref "U501") (pin "8") (pinfunction "OUT_8") (pintype "bidirectional"))
    )
    (net (code "170") (name "VDD_5V_PERIPH") (class "Default")
      (node (ref "C510") (pin "P$1") (pinfunction "1_P$1") (pintype "passive"))
      (node (ref "C602") (pin "P$1") (pinfunction "1_P$1") (pintype "passive"))
      (node (ref "L202") (pin "P$1") (pinfunction "P$1_P$1") (pintype "bidirectional"))
      (node (ref "L203") (pin "P$1") (pinfunction "P$1_P$1") (pintype "bidirectional"))
      (node (ref "L301") (pin "P$1") (pinfunction "P$1_P$1") (pintype "bidirectional"))
      (node (ref "L302") (pin "P$1") (pinfunction "P$1_P$1") (pintype "bidirectional"))
      (node (ref "L303") (pin "P$1") (pinfunction "P$1_P$1") (pintype "bidirectional"))
      (node (ref "L601") (pin "P$1") (pinfunction "1_P$1") (pintype "passive"))
      (node (ref "LED601") (pin "A") (pinfunction "A_A") (pintype "passive"))
      (node (ref "LED602") (pin "A") (pinfunction "A_A") (pintype "passive"))
      (node (ref "LED603") (pin "A") (pinfunction "A_A") (pintype "passive"))
      (node (ref "U503") (pin "8") (pinfunction "OUT_8") (pintype "bidirectional"))
      (node (ref "U602") (pin "3") (pinfunction "VIN_3") (pintype "power_in"))
    )
    (net (code "171") (name "VDD_5V_SENS") (class "Default")
      (node (ref "R4") (pin "P$1") (pinfunction "1_P$1") (pintype "passive"))
      (node (ref "R509") (pin "P$1") (pinfunction "1_P$1") (pintype "passive"))
      (node (ref "U$101") (pin "79") (pinfunction "33_AIN4_79") (pintype "passive"))
    )
    (net (code "172") (name "VDD_SERVO_IN") (class "Default")
      (node (ref "L701") (pin "P$2") (pinfunction "P$2_P$2") (pintype "bidirectional"))
    )
    (net (code "173") (name "VDD_SERVO_SENS") (class "Default")
      (node (ref "R3") (pin "P$1") (pinfunction "1_P$1") (pintype "passive"))
      (node (ref "R716") (pin "P$2") (pinfunction "2_P$2") (pintype "passive"))
      (node (ref "U$101") (pin "85") (pinfunction "39_AIN0_85") (pintype "power_in"))
    )
    (net (code "174") (name "unconnected-(U$4-Pad4)") (class "Default")
      (node (ref "U$4") (pin "4") (pinfunction "4_4") (pintype "passive"))
    )
    (net (code "175") (name "unconnected-(U$4-Pad5)") (class "Default")
      (node (ref "U$4") (pin "5") (pinfunction "5_5") (pintype "passive"))
    )
    (net (code "176") (name "unconnected-(U$101-3_MMC1-Pad3)") (class "Default")
      (node (ref "U$101") (pin "3") (pinfunction "3_MMC1_3") (pintype "passive"))
    )
    (net (code "177") (name "unconnected-(U$101-5_MMC1-Pad5)") (class "Default")
      (node (ref "U$101") (pin "5") (pinfunction "5_MMC1_5") (pintype "passive"))
    )
    (net (code "178") (name "unconnected-(U$101-9_PWR_BUT-Pad55)") (class "Default")
      (node (ref "U$101") (pin "55") (pinfunction "9_PWR_BUT_55") (pintype "passive"))
    )
    (net (code "179") (name "unconnected-(U$101-21_MMC1-Pad21)") (class "Default")
      (node (ref "U$101") (pin "21") (pinfunction "21_MMC1_21") (pintype "passive"))
    )
    (net (code "180") (name "unconnected-(U$101-23_MMC1-Pad23)") (class "Default")
      (node (ref "U$101") (pin "23") (pinfunction "23_MMC1_23") (pintype "passive"))
    )
    (net (code "181") (name "unconnected-(U$101-25_MMC1-Pad25)") (class "Default")
      (node (ref "U$101") (pin "25") (pinfunction "25_MMC1_25") (pintype "passive"))
    )
    (net (code "182") (name "unconnected-(U$101-MMC1_3-Pad6)") (class "Default")
      (node (ref "U$101") (pin "6") (pinfunction "MMC1_3_6") (pintype "passive"))
    )
    (net (code "183") (name "unconnected-(U$101-MMC1_4-Pad4)") (class "Default")
      (node (ref "U$101") (pin "4") (pinfunction "MMC1_4_4") (pintype "passive"))
    )
    (net (code "184") (name "unconnected-(U$101-MMC1_20-Pad20)") (class "Default")
      (node (ref "U$101") (pin "20") (pinfunction "MMC1_20_20") (pintype "passive"))
    )
    (net (code "185") (name "unconnected-(U$101-MMC1_22-Pad22)") (class "Default")
      (node (ref "U$101") (pin "22") (pinfunction "MMC1_22_22") (pintype "passive"))
    )
    (net (code "186") (name "unconnected-(U$101-MMC1_24-Pad24)") (class "Default")
      (node (ref "U$101") (pin "24") (pinfunction "MMC1_24_24") (pintype "passive"))
    )
    (net (code "187") (name "unconnected-(U$101-NC-Pad94)") (class "Default")
      (node (ref "U$101") (pin "94") (pinfunction "NC_94") (pintype "bidirectional"))
    )
    (net (code "188") (name "unconnected-(U$101-NC-Pad95)") (class "Default")
      (node (ref "U$101") (pin "95") (pinfunction "NC_95") (pintype "bidirectional"))
    )
    (net (code "189") (name "unconnected-(U$101-NC-Pad98)") (class "Default")
      (node (ref "U$101") (pin "98") (pinfunction "NC_98") (pintype "bidirectional"))
    )
    (net (code "190") (name "unconnected-(U$101-VDD_ADC_32-Pad78)") (class "Default")
      (node (ref "U$101") (pin "78") (pinfunction "VDD_ADC_32_78") (pintype "passive"))
    )
    (net (code "191") (name "unconnected-(U1-WP-Pad7)") (class "Default")
      (node (ref "U1") (pin "7") (pinfunction "WP_7") (pintype "bidirectional"))
    )
    (net (code "192") (name "unconnected-(U2-A0-Pad1)") (class "Default")
      (node (ref "U2") (pin "1") (pinfunction "A0_1") (pintype "bidirectional"))
    )
    (net (code "193") (name "unconnected-(U2-A1-Pad2)") (class "Default")
      (node (ref "U2") (pin "2") (pinfunction "A1_2") (pintype "bidirectional"))
    )
    (net (code "194") (name "unconnected-(U2-A2-Pad3)") (class "Default")
      (node (ref "U2") (pin "3") (pinfunction "A2_3") (pintype "bidirectional"))
    )
    (net (code "195") (name "unconnected-(U2-WP-Pad7)") (class "Default")
      (node (ref "U2") (pin "7") (pinfunction "WP_7") (pintype "bidirectional"))
    )
    (net (code "196") (name "unconnected-(U302-A3-Pad4)") (class "Default")
      (node (ref "U302") (pin "4") (pinfunction "A3_4") (pintype "bidirectional"))
    )
    (net (code "197") (name "unconnected-(U302-A4-Pad5)") (class "Default")
      (node (ref "U302") (pin "5") (pinfunction "A4_5") (pintype "bidirectional"))
    )
    (net (code "198") (name "unconnected-(U302-A5-Pad6)") (class "Default")
      (node (ref "U302") (pin "6") (pinfunction "A5_6") (pintype "bidirectional"))
    )
    (net (code "199") (name "unconnected-(U302-A6-Pad7)") (class "Default")
      (node (ref "U302") (pin "7") (pinfunction "A6_7") (pintype "bidirectional"))
    )
    (net (code "200") (name "unconnected-(U302-A7-Pad8)") (class "Default")
      (node (ref "U302") (pin "8") (pinfunction "A7_8") (pintype "bidirectional"))
    )
    (net (code "201") (name "unconnected-(U302-A8-Pad9)") (class "Default")
      (node (ref "U302") (pin "9") (pinfunction "A8_9") (pintype "bidirectional"))
    )
    (net (code "202") (name "unconnected-(U302-B3-Pad17)") (class "Default")
      (node (ref "U302") (pin "17") (pinfunction "B3_17") (pintype "bidirectional"))
    )
    (net (code "203") (name "unconnected-(U302-B4-Pad16)") (class "Default")
      (node (ref "U302") (pin "16") (pinfunction "B4_16") (pintype "bidirectional"))
    )
    (net (code "204") (name "unconnected-(U302-B5-Pad15)") (class "Default")
      (node (ref "U302") (pin "15") (pinfunction "B5_15") (pintype "bidirectional"))
    )
    (net (code "205") (name "unconnected-(U302-B6-Pad14)") (class "Default")
      (node (ref "U302") (pin "14") (pinfunction "B6_14") (pintype "bidirectional"))
    )
    (net (code "206") (name "unconnected-(U302-B7-Pad13)") (class "Default")
      (node (ref "U302") (pin "13") (pinfunction "B7_13") (pintype "bidirectional"))
    )
    (net (code "207") (name "unconnected-(U302-B8-Pad12)") (class "Default")
      (node (ref "U302") (pin "12") (pinfunction "B8_12") (pintype "bidirectional"))
    )
    (net (code "208") (name "unconnected-(U401-CSB1-Pad4)") (class "Default")
      (node (ref "U401") (pin "4") (pinfunction "CSB1_4") (pintype "bidirectional"))
    )
    (net (code "209") (name "unconnected-(U403-AUX_CL-Pad7)") (class "Default")
      (node (ref "U403") (pin "7") (pinfunction "AUX_CL_7") (pintype "bidirectional"))
    )
    (net (code "210") (name "unconnected-(U403-AUX_DA-Pad6)") (class "Default")
      (node (ref "U403") (pin "6") (pinfunction "AUX_DA_6") (pintype "bidirectional"))
    )
    (net (code "211") (name "unconnected-(U403-CLKOUT-Pad22)") (class "Default")
      (node (ref "U403") (pin "22") (pinfunction "CLKOUT_22") (pintype "bidirectional"))
    )
    (net (code "212") (name "unconnected-(U403-NC1-Pad2)") (class "Default")
      (node (ref "U403") (pin "2") (pinfunction "NC1_2") (pintype "bidirectional"))
    )
    (net (code "213") (name "unconnected-(U403-NC2-Pad3)") (class "Default")
      (node (ref "U403") (pin "3") (pinfunction "NC2_3") (pintype "bidirectional"))
    )
    (net (code "214") (name "unconnected-(U403-NC3-Pad4)") (class "Default")
      (node (ref "U403") (pin "4") (pinfunction "NC3_4") (pintype "bidirectional"))
    )
    (net (code "215") (name "unconnected-(U403-NC4-Pad5)") (class "Default")
      (node (ref "U403") (pin "5") (pinfunction "NC4_5") (pintype "bidirectional"))
    )
    (net (code "216") (name "unconnected-(U403-NC5-Pad14)") (class "Default")
      (node (ref "U403") (pin "14") (pinfunction "NC5_14") (pintype "bidirectional"))
    )
    (net (code "217") (name "unconnected-(U403-NC6-Pad15)") (class "Default")
      (node (ref "U403") (pin "15") (pinfunction "NC6_15") (pintype "bidirectional"))
    )
    (net (code "218") (name "unconnected-(U403-NC7-Pad16)") (class "Default")
      (node (ref "U403") (pin "16") (pinfunction "NC7_16") (pintype "bidirectional"))
    )
    (net (code "219") (name "unconnected-(U403-NC8-Pad17)") (class "Default")
      (node (ref "U403") (pin "17") (pinfunction "NC8_17") (pintype "bidirectional"))
    )
    (net (code "220") (name "unconnected-(U403-RESV1-Pad19)") (class "Default")
      (node (ref "U403") (pin "19") (pinfunction "RESV1_19") (pintype "bidirectional"))
    )
    (net (code "221") (name "unconnected-(U403-RESV2-Pad21)") (class "Default")
      (node (ref "U403") (pin "21") (pinfunction "RESV2_21") (pintype "bidirectional"))
    )
    (net (code "222") (name "unconnected-(U405-AUX_CL-Pad7)") (class "Default")
      (node (ref "U405") (pin "7") (pinfunction "AUX_CL_7") (pintype "bidirectional"))
    )
    (net (code "223") (name "unconnected-(U405-AUX_DA-Pad21)") (class "Default")
      (node (ref "U405") (pin "21") (pinfunction "AUX_DA_21") (pintype "bidirectional"))
    )
    (net (code "224") (name "unconnected-(U405-NC-Pad2)") (class "Default")
      (node (ref "U405") (pin "2") (pinfunction "NC_2") (pintype "bidirectional"))
    )
    (net (code "225") (name "unconnected-(U405-NC-Pad3)") (class "Default")
      (node (ref "U405") (pin "3") (pinfunction "NC_3") (pintype "bidirectional"))
    )
    (net (code "226") (name "unconnected-(U405-NC-Pad4)") (class "Default")
      (node (ref "U405") (pin "4") (pinfunction "NC_4") (pintype "bidirectional"))
    )
    (net (code "227") (name "unconnected-(U405-NC-Pad5)") (class "Default")
      (node (ref "U405") (pin "5") (pinfunction "NC_5") (pintype "bidirectional"))
    )
    (net (code "228") (name "unconnected-(U405-NC-Pad6)") (class "Default")
      (node (ref "U405") (pin "6") (pinfunction "NC_6") (pintype "bidirectional"))
    )
    (net (code "229") (name "unconnected-(U405-NC-Pad14)") (class "Default")
      (node (ref "U405") (pin "14") (pinfunction "NC_14") (pintype "bidirectional"))
    )
    (net (code "230") (name "unconnected-(U405-NC-Pad15)") (class "Default")
      (node (ref "U405") (pin "15") (pinfunction "NC_15") (pintype "bidirectional"))
    )
    (net (code "231") (name "unconnected-(U405-NC-Pad16)") (class "Default")
      (node (ref "U405") (pin "16") (pinfunction "NC_16") (pintype "bidirectional"))
    )
    (net (code "232") (name "unconnected-(U405-NC-Pad17)") (class "Default")
      (node (ref "U405") (pin "17") (pinfunction "NC_17") (pintype "bidirectional"))
    )
    (net (code "233") (name "unconnected-(U405-RESV-Pad19)") (class "Default")
      (node (ref "U405") (pin "19") (pinfunction "RESV_19") (pintype "bidirectional"))
    )
    (net (code "234") (name "unconnected-(U406-DEN_G-Pad10)") (class "Default")
      (node (ref "U406") (pin "10") (pinfunction "DEN_G_10") (pintype "bidirectional"))
    )
    (net (code "235") (name "unconnected-(U406-INT_G-Pad11)") (class "Default")
      (node (ref "U406") (pin "11") (pinfunction "INT_G_11") (pintype "bidirectional"))
    )
    (net (code "236") (name "unconnected-(U406-NC-Pad1)") (class "Default")
      (node (ref "U406") (pin "1") (pinfunction "NC_1") (pintype "bidirectional"))
    )
    (net (code "237") (name "unconnected-(U701-A5-Pad6)") (class "Default")
      (node (ref "U701") (pin "6") (pinfunction "A5_6") (pintype "bidirectional"))
    )
    (net (code "238") (name "unconnected-(U701-A6-Pad7)") (class "Default")
      (node (ref "U701") (pin "7") (pinfunction "A6_7") (pintype "bidirectional"))
    )
    (net (code "239") (name "unconnected-(U701-A7-Pad8)") (class "Default")
      (node (ref "U701") (pin "8") (pinfunction "A7_8") (pintype "bidirectional"))
    )
    (net (code "240") (name "unconnected-(U701-A8-Pad9)") (class "Default")
      (node (ref "U701") (pin "9") (pinfunction "A8_9") (pintype "bidirectional"))
    )
    (net (code "241") (name "unconnected-(U701-B5-Pad15)") (class "Default")
      (node (ref "U701") (pin "15") (pinfunction "B5_15") (pintype "bidirectional"))
    )
    (net (code "242") (name "unconnected-(U701-B6-Pad14)") (class "Default")
      (node (ref "U701") (pin "14") (pinfunction "B6_14") (pintype "bidirectional"))
    )
    (net (code "243") (name "unconnected-(U701-B7-Pad13)") (class "Default")
      (node (ref "U701") (pin "13") (pinfunction "B7_13") (pintype "bidirectional"))
    )
    (net (code "244") (name "unconnected-(U701-B8-Pad12)") (class "Default")
      (node (ref "U701") (pin "12") (pinfunction "B8_12") (pintype "bidirectional"))
    )
    (net (code "245") (name "unconnected-(U802-CSET-Pad6)") (class "Default")
      (node (ref "U802") (pin "6") (pinfunction "CSET_6") (pintype "bidirectional"))
    )
    (net (code "246") (name "unconnected-(U802-POR2-Pad3)") (class "Default")
      (node (ref "U802") (pin "3") (pinfunction "POR2_3") (pintype "bidirectional"))
    )
    (net (code "247") (name "unconnected-(U802-VOUT2-Pad7)") (class "Default")
      (node (ref "U802") (pin "7") (pinfunction "VOUT2_7") (pintype "bidirectional"))
    )
    (net (code "248") (name "~{ACCEL_MAG_CS}") (class "Default")
      (node (ref "U$101") (pin "63") (pinfunction "17_SPI_0_CS0_63") (pintype "passive"))
      (node (ref "U406") (pin "20") (pinfunction "CS_XM_20") (pintype "bidirectional"))
    )
    (net (code "249") (name "~{FRAM_CS}") (class "Default")
      (node (ref "U$101") (pin "12") (pinfunction "PRU0_R30[14]_12_12") (pintype "passive"))
      (node (ref "U102") (pin "1") (pinfunction "~{S}_1") (pintype "bidirectional"))
    )
    (net (code "250") (name "~{GYRO_CS}") (class "Default")
      (node (ref "U$101") (pin "9") (pinfunction "9_GPIO2[5]_9") (pintype "passive"))
      (node (ref "U406") (pin "19") (pinfunction "CS_G_19") (pintype "bidirectional"))
    )
    (net (code "251") (name "~{LED_AMBER}") (class "Default")
      (node (ref "R610") (pin "P$1") (pinfunction "1_P$1") (pintype "passive"))
      (node (ref "U$101") (pin "71") (pinfunction "25_PRU0_R30/31[7]_71") (pintype "passive"))
    )
    (net (code "252") (name "~{LED_BLUE}") (class "Default")
      (node (ref "R612") (pin "P$1") (pinfunction "1_P$1") (pintype "passive"))
      (node (ref "U$101") (pin "61") (pinfunction "15_GPIO1[16]_61") (pintype "passive"))
    )
    (net (code "253") (name "~{LED_SAFETY}") (class "Default")
      (node (ref "R611") (pin "P$2") (pinfunction "2_P$2") (pintype "passive"))
      (node (ref "U$101") (pin "26") (pinfunction "GPIO1[29]_26_26") (pintype "passive"))
    )
    (net (code "254") (name "~{VDD_5V_HIPOWER_OC}") (class "Default")
      (node (ref "R502") (pin "P$1") (pinfunction "1_P$1") (pintype "passive"))
      (node (ref "U$101") (pin "19") (pinfunction "19_GPIO0[22]_19") (pintype "passive"))
      (node (ref "U501") (pin "4") (pinfunction "~{FAULT}_4") (pintype "bidirectional"))
    )
    (net (code "255") (name "~{VDD_5V_PERIPH_EN}") (class "Default")
      (node (ref "R506") (pin "P$1") (pinfunction "1_P$1") (pintype "passive"))
      (node (ref "U$101") (pin "58") (pinfunction "GPIO1[28]_12_58") (pintype "passive"))
      (node (ref "U501") (pin "5") (pinfunction "~{CE}_5") (pintype "bidirectional"))
      (node (ref "U503") (pin "5") (pinfunction "~{CE}_5") (pintype "bidirectional"))
    )
    (net (code "256") (name "~{VDD_5V_PERIPH_OC}") (class "Default")
      (node (ref "R507") (pin "P$1") (pinfunction "1_P$1") (pintype "passive"))
      (node (ref "U$101") (pin "13") (pinfunction "13_GPIO0[23]_13") (pintype "passive"))
      (node (ref "U503") (pin "4") (pinfunction "~{FAULT}_4") (pintype "bidirectional"))
    )
    (net (code "257") (name "~{VDD_SERVO_IN_FAULT}") (class "Default")
      (node (ref "U$101") (pin "18") (pinfunction "GPIO2[1]_18_18") (pintype "passive"))
    )
  )
)
